# Main_Board.net
KiCad netlist of a schematic drawn in Altium Designer
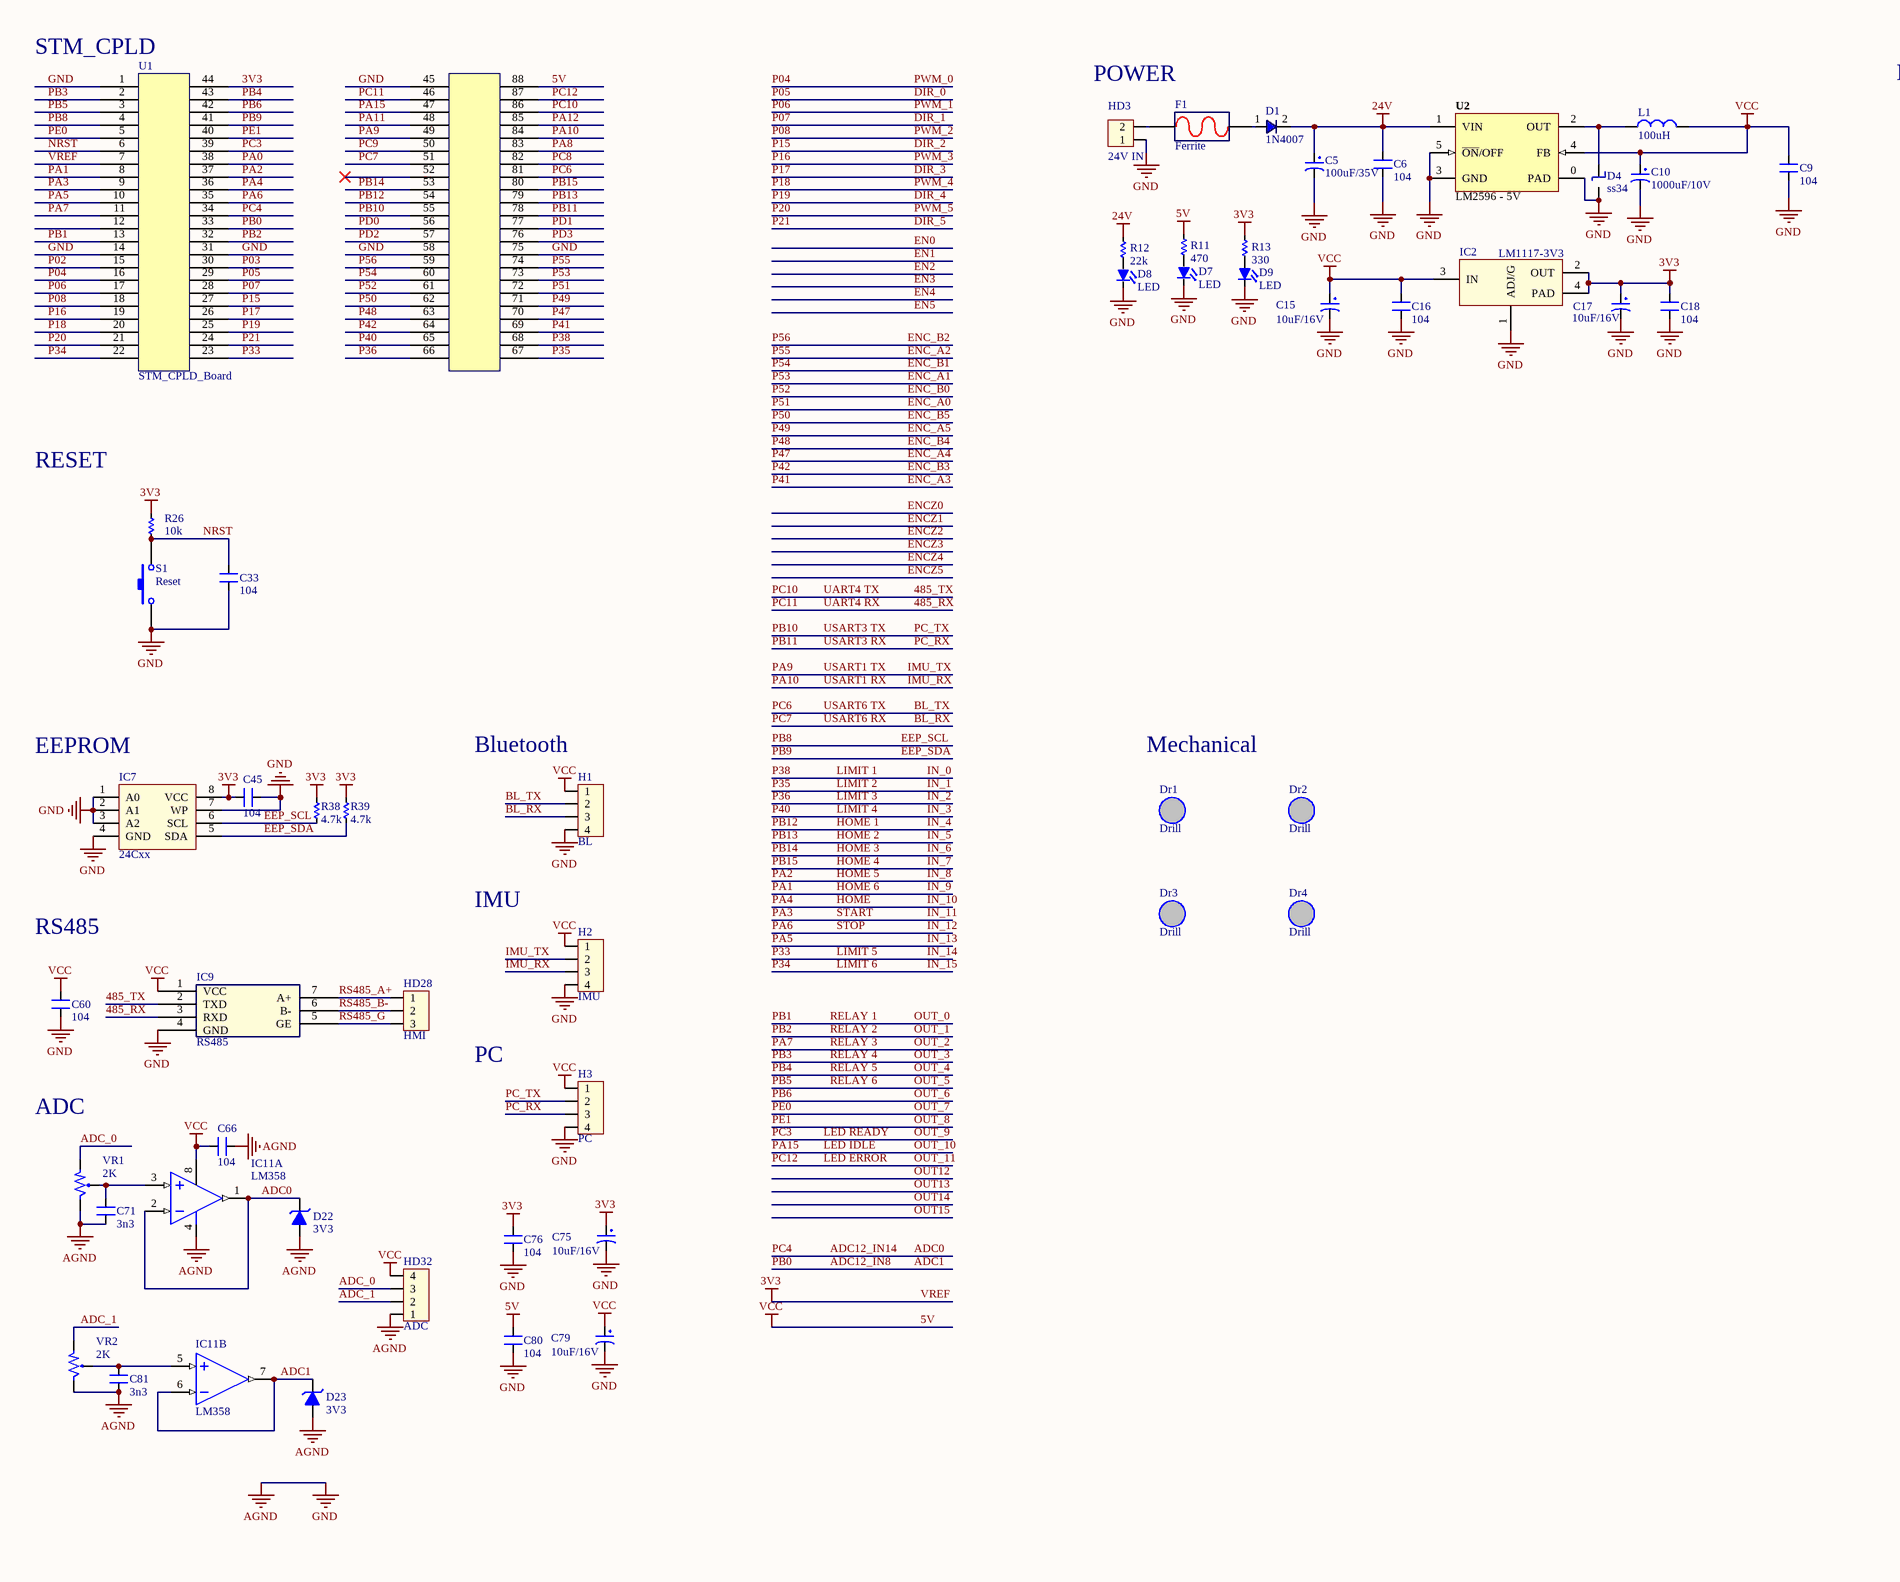
[diagram p0: Main_Board.SchDoc, top left]
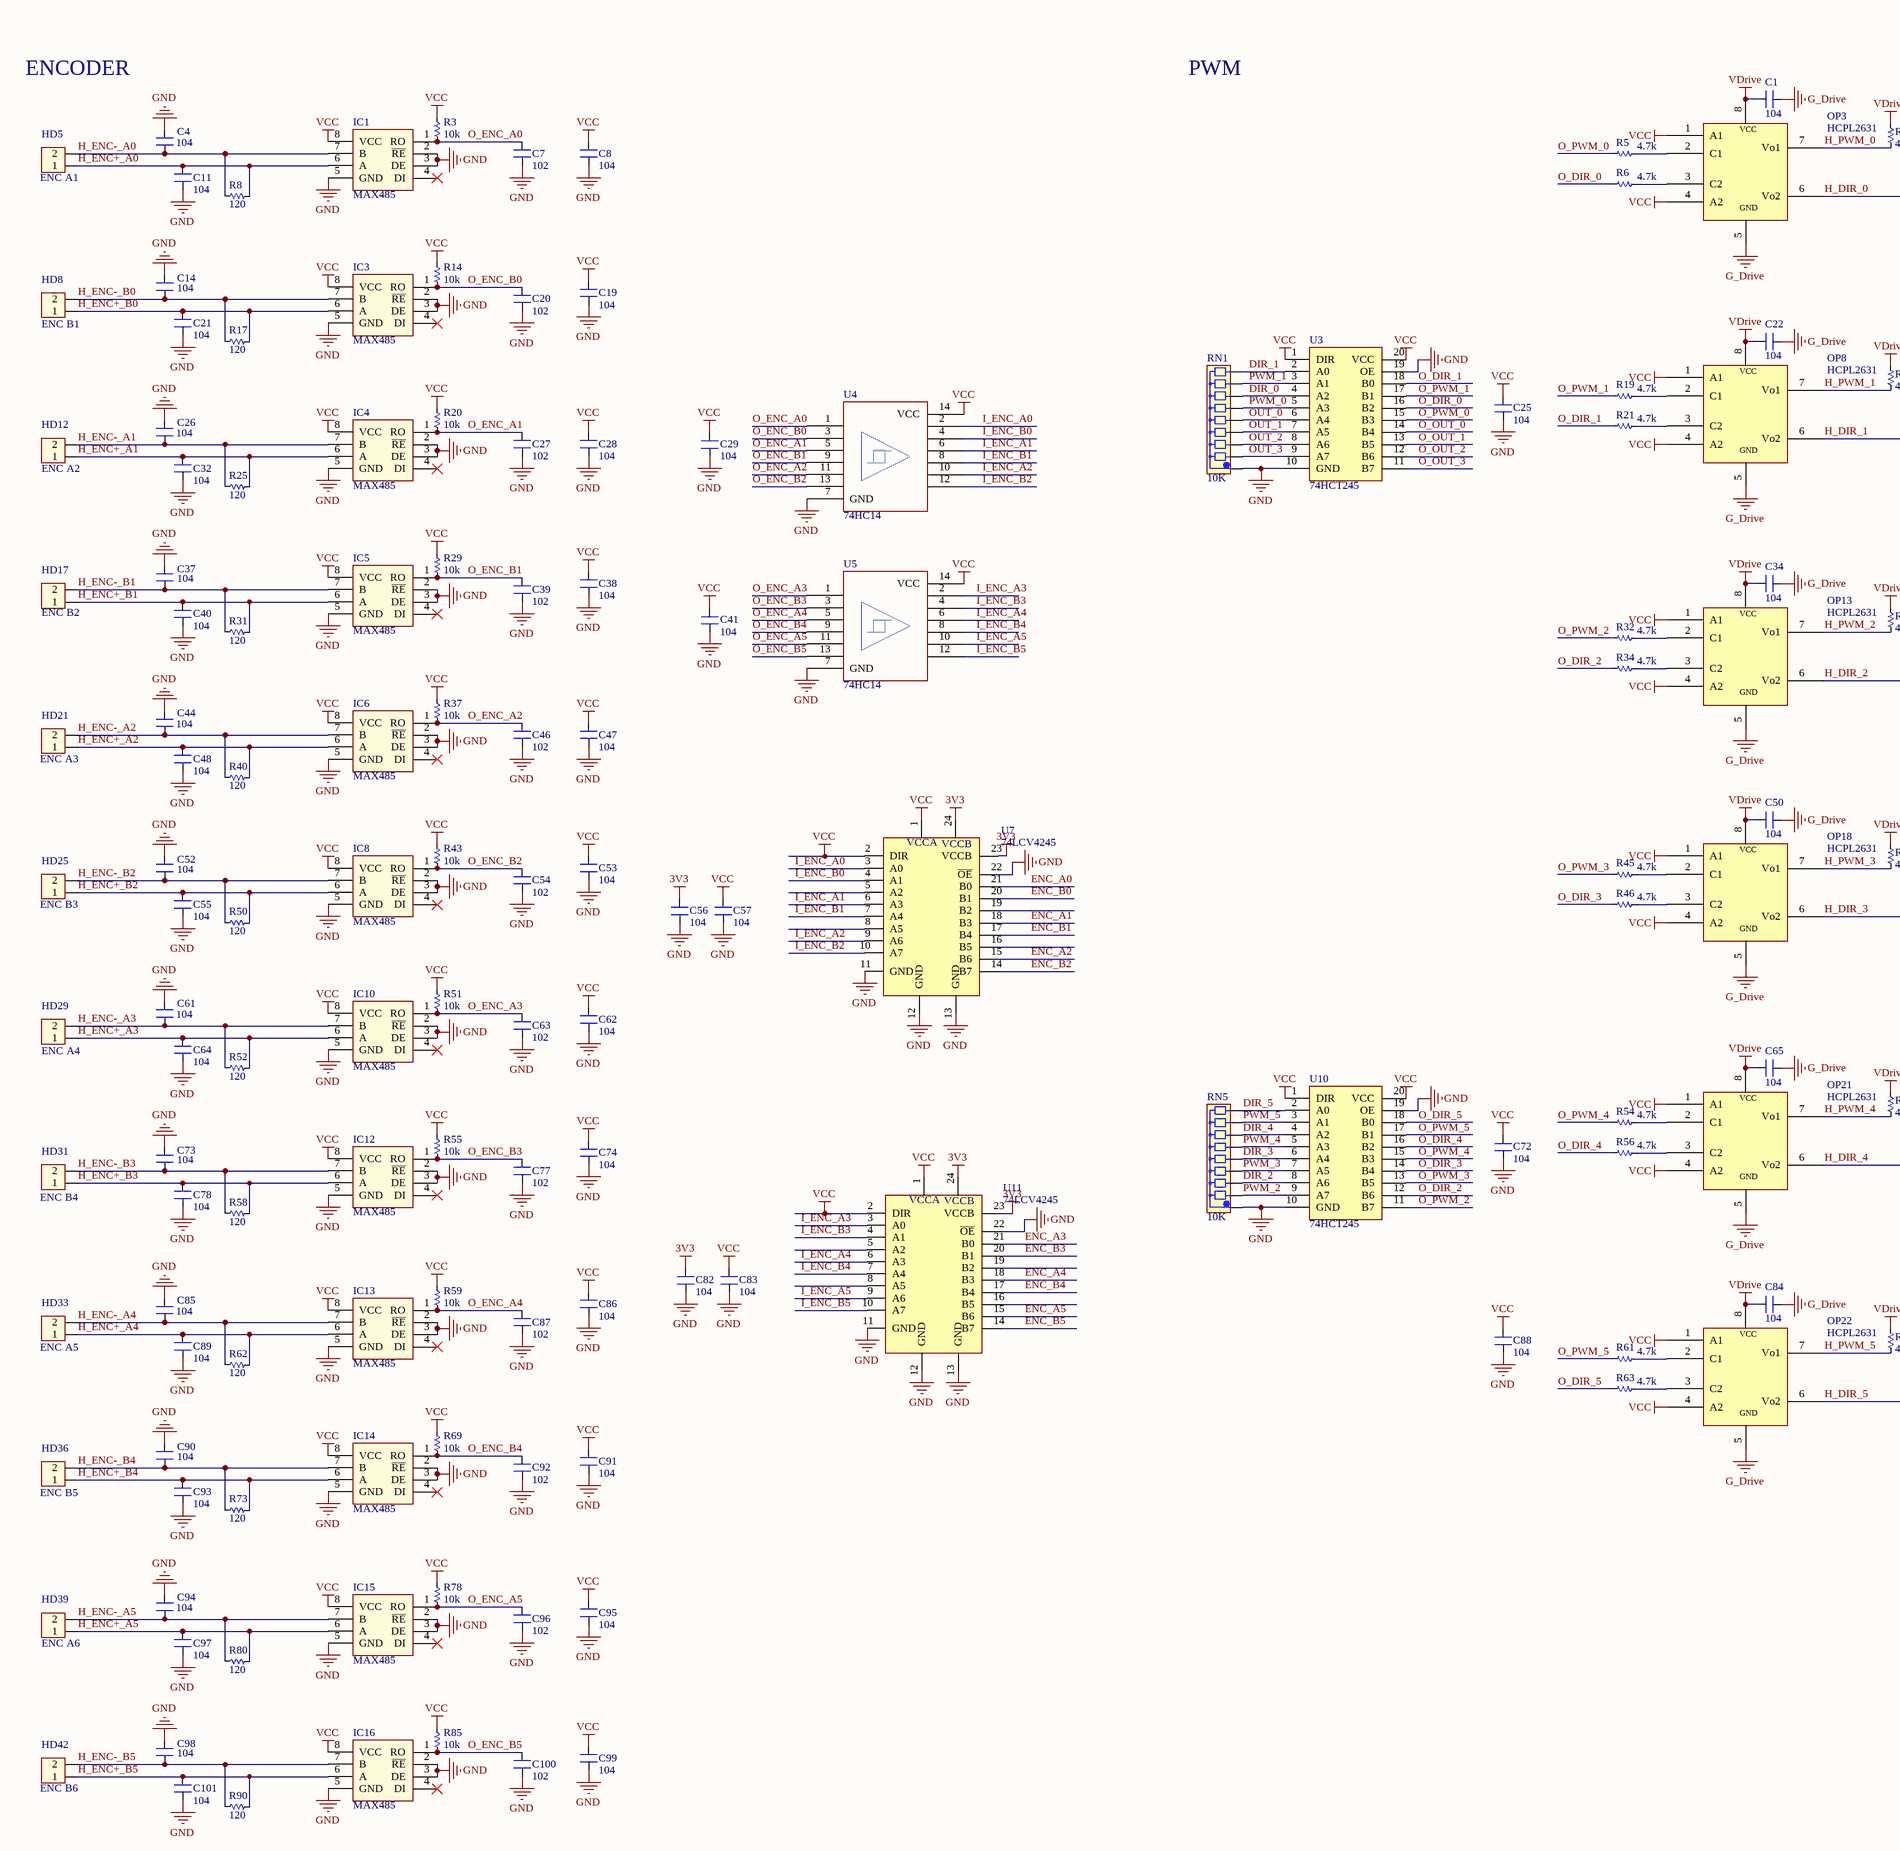
[diagram p1: Main_Board.SchDoc, top middle]
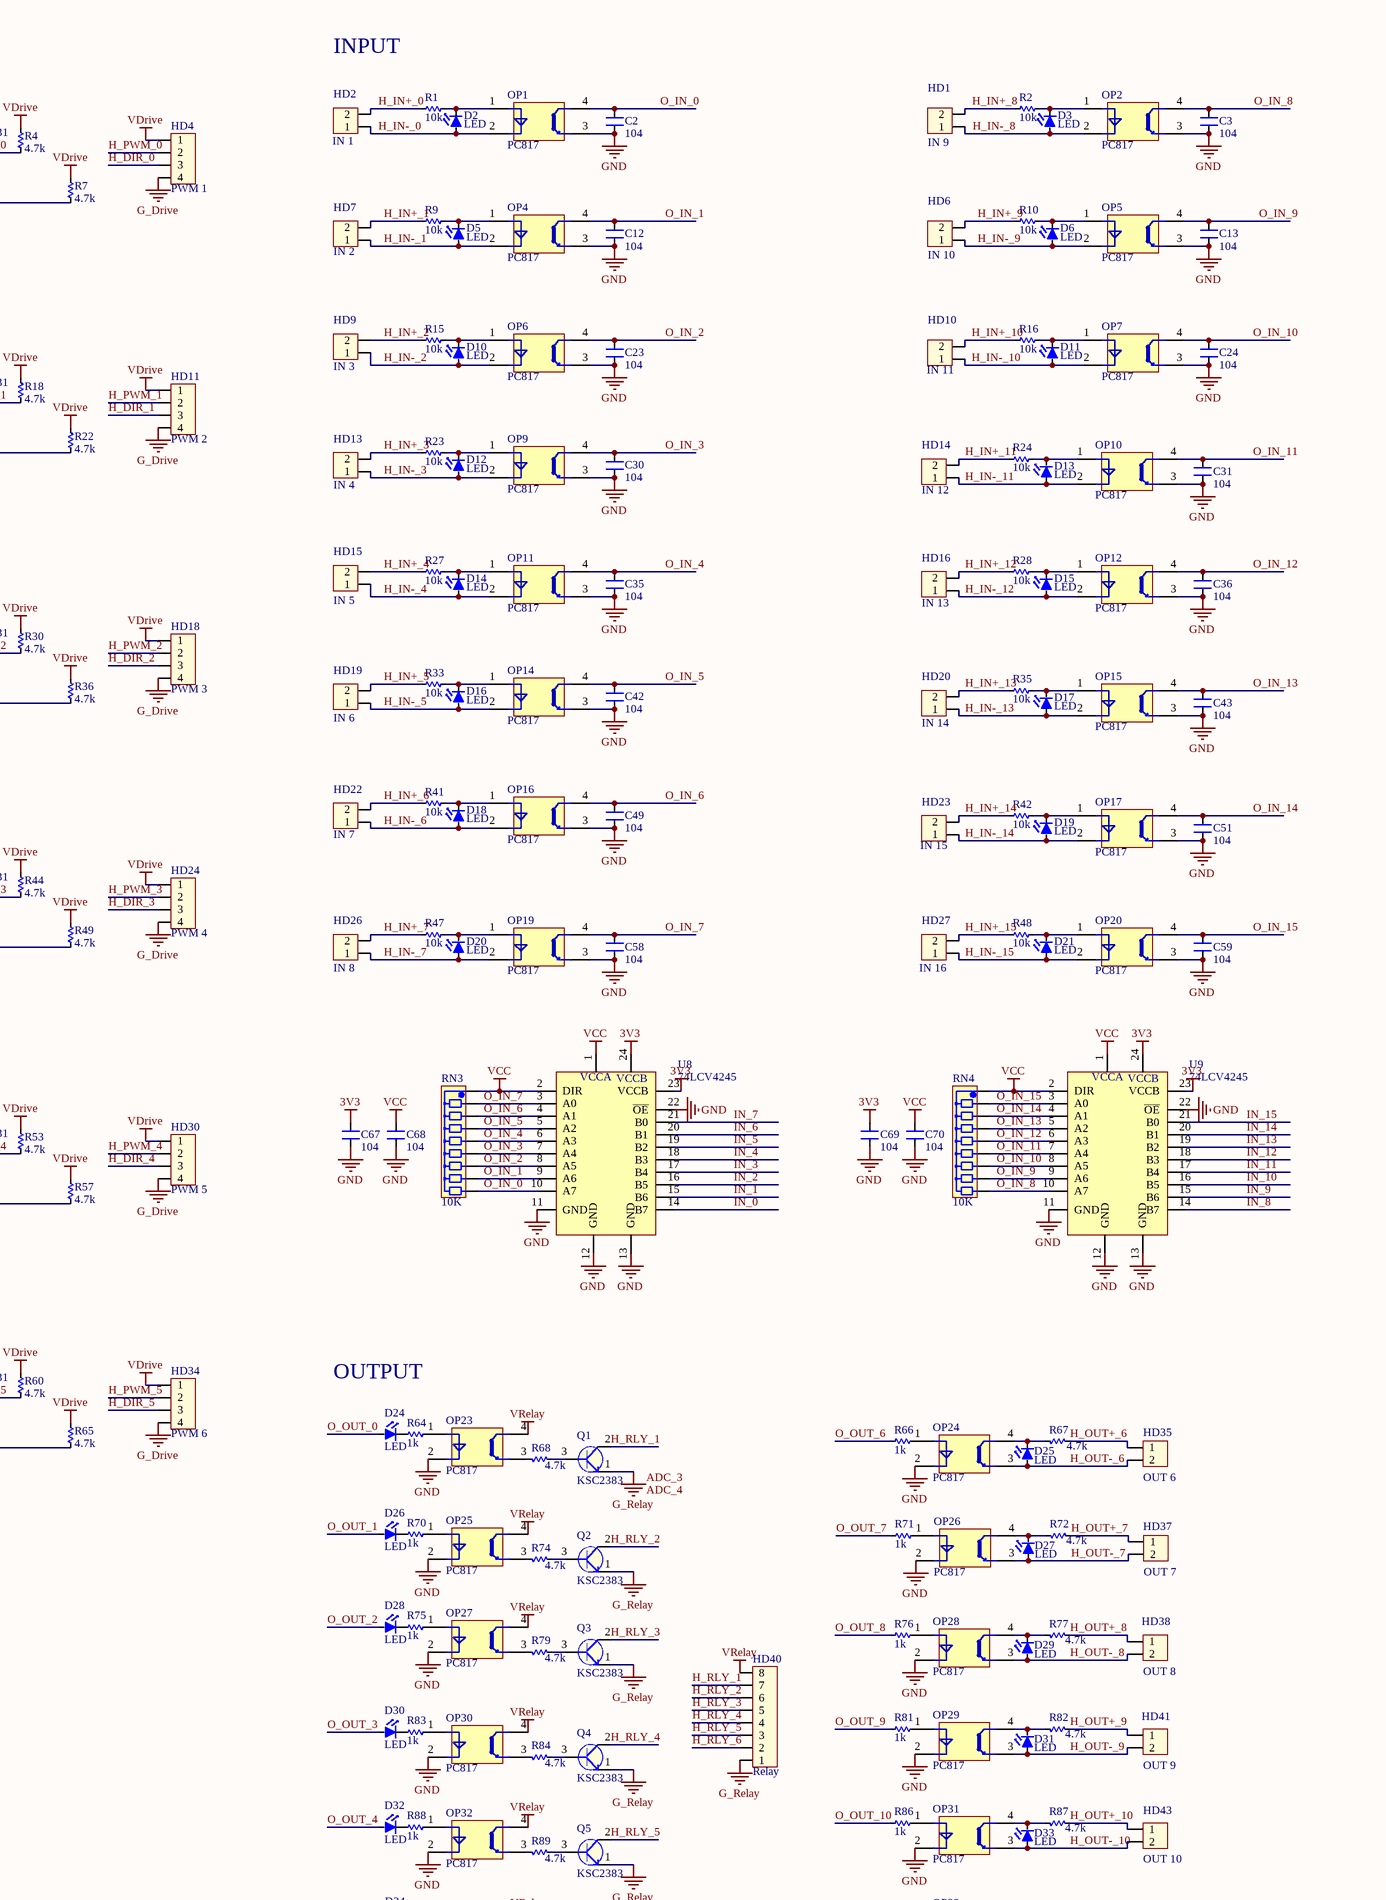
[diagram p2: Main_Board.SchDoc, top right]
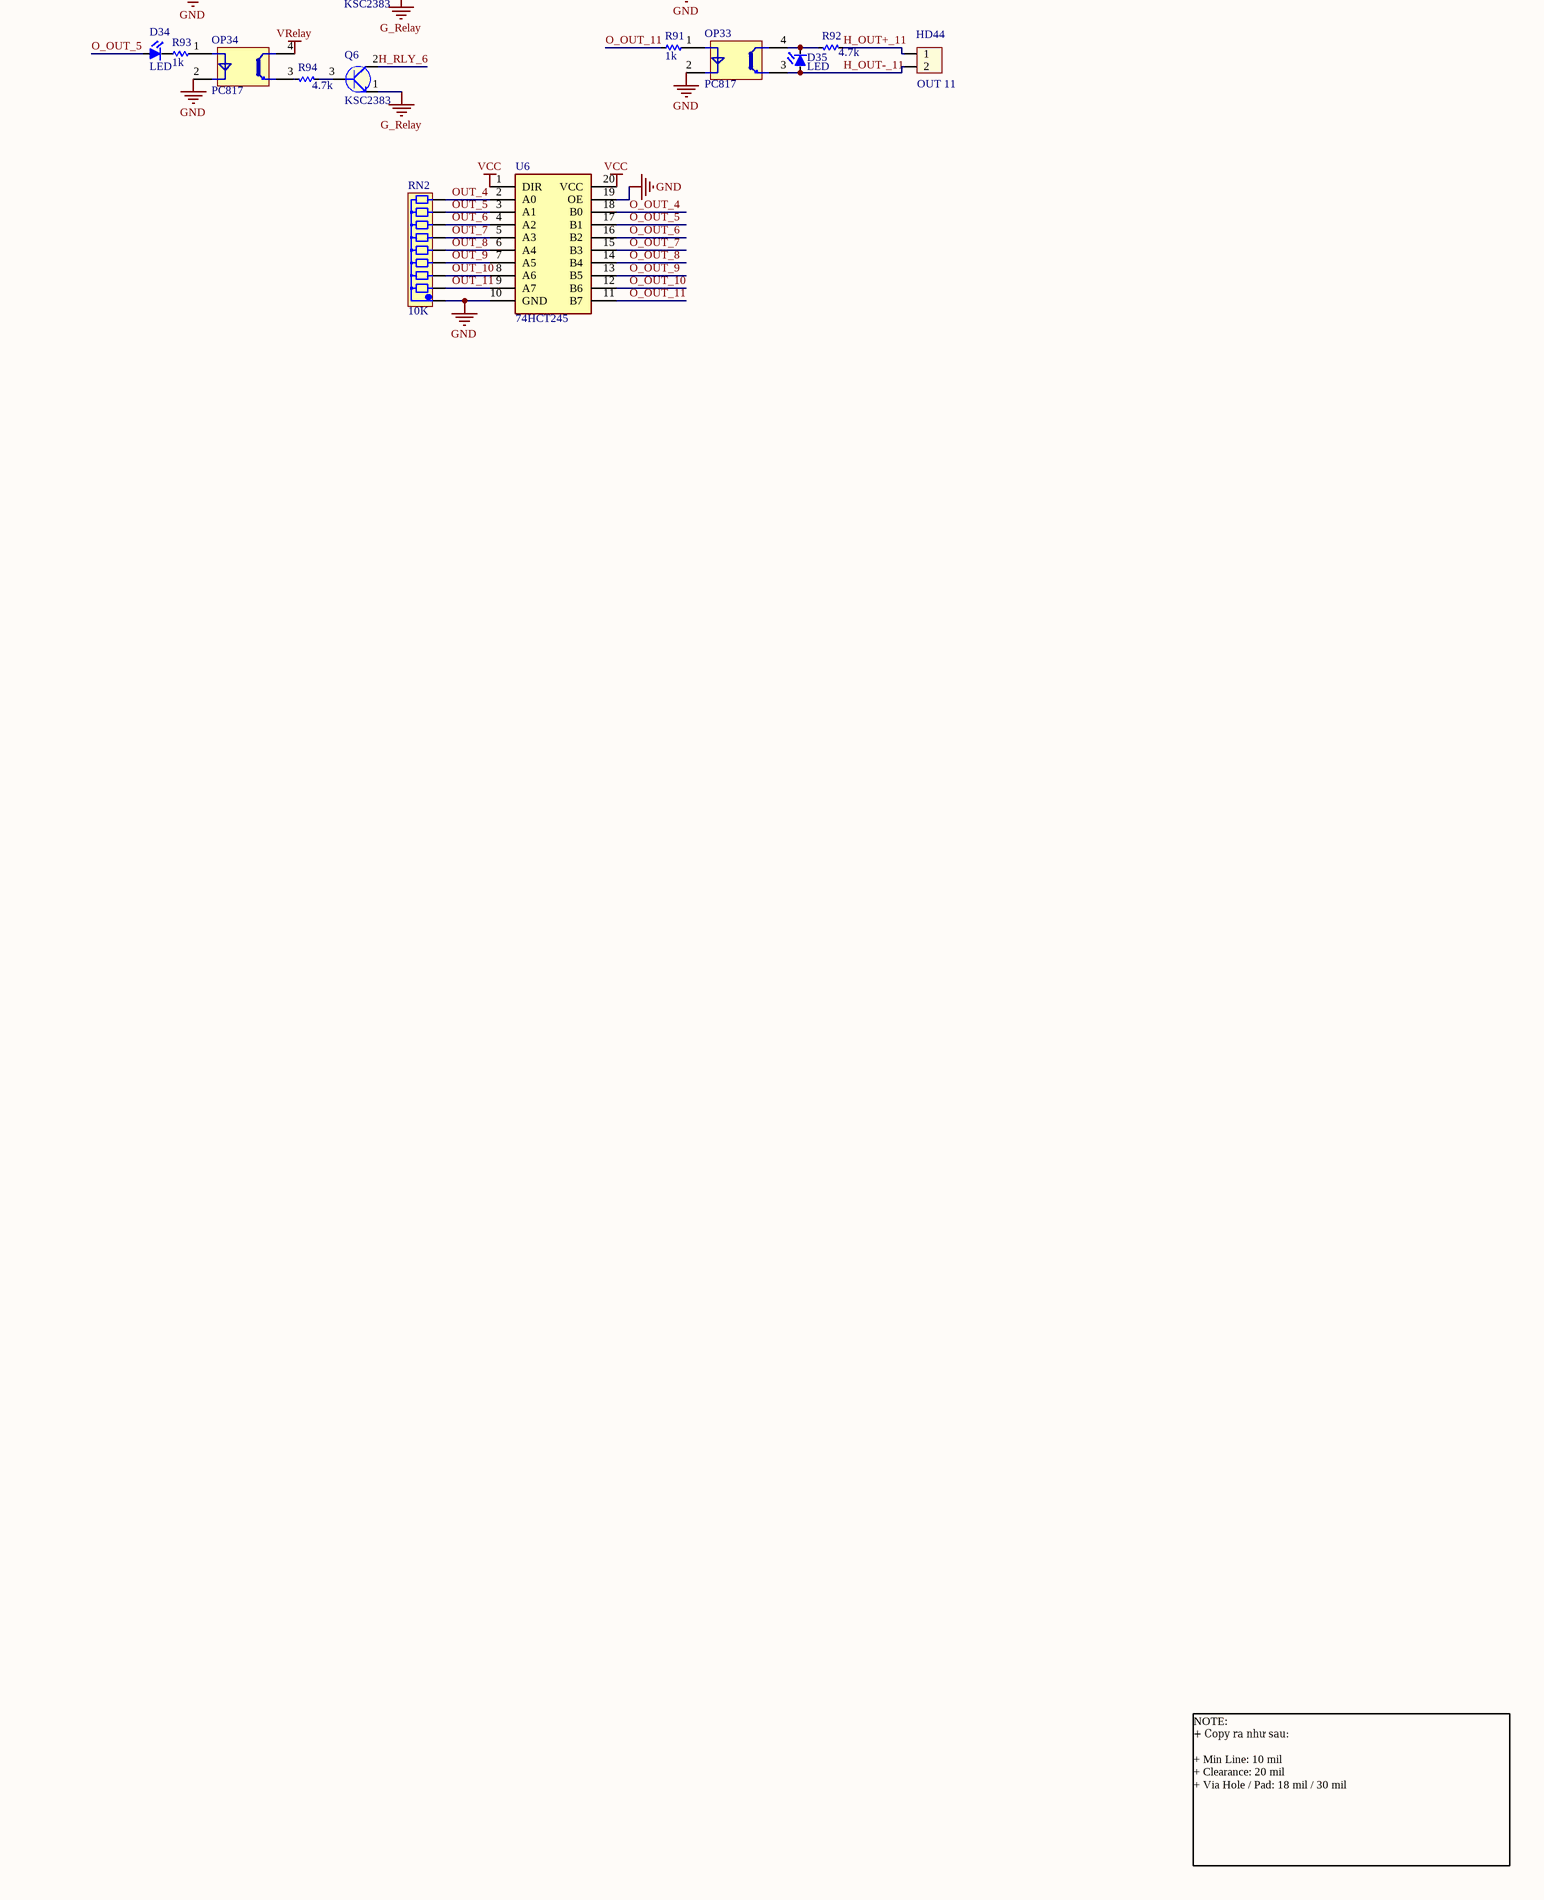
[diagram p3: Main_Board.SchDoc, bottom right]

(export (version "E")
  (design (tool "Eeschema 10.0.6"))
  (components
    (comp (ref "C1")
      (value "104")
      (footprint "CAP-SM-0805")
      (description "Ceramic Capacitor SMD")
      (libsource (lib "Main_Board") (part "CAP_SM_0805"))
    )
    (comp (ref "C2")
      (value "104")
      (footprint "CAP-SM-0805")
      (description "Ceramic Capacitor SMD")
      (libsource (lib "Main_Board") (part "CAP_SM_0805"))
    )
    (comp (ref "C3")
      (value "104")
      (footprint "CAP-SM-0805")
      (description "Ceramic Capacitor SMD")
      (libsource (lib "Main_Board") (part "CAP_SM_0805"))
    )
    (comp (ref "C4")
      (value "104")
      (footprint "CAP-SM-0805")
      (description "Ceramic Capacitor SMD")
      (libsource (lib "Main_Board") (part "CAP_SM_0805"))
    )
    (comp (ref "C5")
      (value "100uF/35V")
      (footprint "Cap_Alu_D8")
      (description "SMD Aluminum Electrolytic Capacitor")
      (libsource (lib "Main_Board") (part "Cap_SM_Alu"))
    )
    (comp (ref "C6")
      (value "104")
      (footprint "CAP-SM-0805")
      (description "Ceramic Capacitor SMD")
      (libsource (lib "Main_Board") (part "CAP_SM_0805"))
    )
    (comp (ref "C7")
      (value "102")
      (footprint "CAP-SM-0805")
      (description "Ceramic Capacitor SMD")
      (libsource (lib "Main_Board") (part "CAP_SM_0805"))
    )
    (comp (ref "C8")
      (value "104")
      (footprint "CAP-SM-0805")
      (description "Ceramic Capacitor SMD")
      (libsource (lib "Main_Board") (part "CAP_SM_0805"))
    )
    (comp (ref "C9")
      (value "104")
      (footprint "CAP-SM-0805")
      (description "Ceramic Capacitor SMD")
      (libsource (lib "Main_Board") (part "CAP_SM_0805"))
    )
    (comp (ref "C10")
      (value "1000uF/10V")
      (footprint "Cap_Alu_G")
      (description "SMD Aluminum Electrolytic Capacitor")
      (libsource (lib "Main_Board") (part "Cap_SM_Alu"))
    )
    (comp (ref "C11")
      (value "104")
      (footprint "CAP-SM-0805")
      (description "Ceramic Capacitor SMD")
      (libsource (lib "Main_Board") (part "CAP_SM_0805"))
    )
    (comp (ref "C12")
      (value "104")
      (footprint "CAP-SM-0805")
      (description "Ceramic Capacitor SMD")
      (libsource (lib "Main_Board") (part "CAP_SM_0805"))
    )
    (comp (ref "C13")
      (value "104")
      (footprint "CAP-SM-0805")
      (description "Ceramic Capacitor SMD")
      (libsource (lib "Main_Board") (part "CAP_SM_0805"))
    )
    (comp (ref "C14")
      (value "104")
      (footprint "CAP-SM-0805")
      (description "Ceramic Capacitor SMD")
      (libsource (lib "Main_Board") (part "CAP_SM_0805"))
    )
    (comp (ref "C15")
      (value "10uF/16V")
      (footprint "CAP_ALU_B")
      (description "C 47uF/50V , 220uF/16V")
      (libsource (lib "Main_Board") (part "CP2"))
    )
    (comp (ref "C16")
      (value "104")
      (footprint "CAP-SM-0805")
      (description "Ceramic Capacitor SMD")
      (libsource (lib "Main_Board") (part "CAP_SM_0805"))
    )
    (comp (ref "C17")
      (value "10uF/16V")
      (footprint "CAP_ALU_B")
      (description "C 47uF/50V , 220uF/16V")
      (libsource (lib "Main_Board") (part "CP2"))
    )
    (comp (ref "C18")
      (value "104")
      (footprint "CAP-SM-0805")
      (description "Ceramic Capacitor SMD")
      (libsource (lib "Main_Board") (part "CAP_SM_0805"))
    )
    (comp (ref "C19")
      (value "104")
      (footprint "CAP-SM-0805")
      (description "Ceramic Capacitor SMD")
      (libsource (lib "Main_Board") (part "CAP_SM_0805"))
    )
    (comp (ref "C20")
      (value "102")
      (footprint "CAP-SM-0805")
      (description "Ceramic Capacitor SMD")
      (libsource (lib "Main_Board") (part "CAP_SM_0805"))
    )
    (comp (ref "C21")
      (value "104")
      (footprint "CAP-SM-0805")
      (description "Ceramic Capacitor SMD")
      (libsource (lib "Main_Board") (part "CAP_SM_0805"))
    )
    (comp (ref "C22")
      (value "104")
      (footprint "CAP-SM-0805")
      (description "Ceramic Capacitor SMD")
      (libsource (lib "Main_Board") (part "CAP_SM_0805"))
    )
    (comp (ref "C23")
      (value "104")
      (footprint "CAP-SM-0805")
      (description "Ceramic Capacitor SMD")
      (libsource (lib "Main_Board") (part "CAP_SM_0805"))
    )
    (comp (ref "C24")
      (value "104")
      (footprint "CAP-SM-0805")
      (description "Ceramic Capacitor SMD")
      (libsource (lib "Main_Board") (part "CAP_SM_0805"))
    )
    (comp (ref "C25")
      (value "104")
      (footprint "CAP-SM-0805")
      (description "Ceramic Capacitor SMD")
      (libsource (lib "Main_Board") (part "CAP_SM_0805"))
    )
    (comp (ref "C26")
      (value "104")
      (footprint "CAP-SM-0805")
      (description "Ceramic Capacitor SMD")
      (libsource (lib "Main_Board") (part "CAP_SM_0805"))
    )
    (comp (ref "C27")
      (value "102")
      (footprint "CAP-SM-0805")
      (description "Ceramic Capacitor SMD")
      (libsource (lib "Main_Board") (part "CAP_SM_0805"))
    )
    (comp (ref "C28")
      (value "104")
      (footprint "CAP-SM-0805")
      (description "Ceramic Capacitor SMD")
      (libsource (lib "Main_Board") (part "CAP_SM_0805"))
    )
    (comp (ref "C29")
      (value "104")
      (footprint "CAP-SM-0805")
      (description "Ceramic Capacitor SMD")
      (libsource (lib "Main_Board") (part "CAP_SM_0805"))
    )
    (comp (ref "C30")
      (value "104")
      (footprint "CAP-SM-0805")
      (description "Ceramic Capacitor SMD")
      (libsource (lib "Main_Board") (part "CAP_SM_0805"))
    )
    (comp (ref "C31")
      (value "104")
      (footprint "CAP-SM-0805")
      (description "Ceramic Capacitor SMD")
      (libsource (lib "Main_Board") (part "CAP_SM_0805"))
    )
    (comp (ref "C32")
      (value "104")
      (footprint "CAP-SM-0805")
      (description "Ceramic Capacitor SMD")
      (libsource (lib "Main_Board") (part "CAP_SM_0805"))
    )
    (comp (ref "C33")
      (value "104")
      (footprint "CAP-SM-0805")
      (description "Ceramic Capacitor SMD")
      (libsource (lib "Main_Board") (part "CAP_SM_0805"))
    )
    (comp (ref "C34")
      (value "104")
      (footprint "CAP-SM-0805")
      (description "Ceramic Capacitor SMD")
      (libsource (lib "Main_Board") (part "CAP_SM_0805"))
    )
    (comp (ref "C35")
      (value "104")
      (footprint "CAP-SM-0805")
      (description "Ceramic Capacitor SMD")
      (libsource (lib "Main_Board") (part "CAP_SM_0805"))
    )
    (comp (ref "C36")
      (value "104")
      (footprint "CAP-SM-0805")
      (description "Ceramic Capacitor SMD")
      (libsource (lib "Main_Board") (part "CAP_SM_0805"))
    )
    (comp (ref "C37")
      (value "104")
      (footprint "CAP-SM-0805")
      (description "Ceramic Capacitor SMD")
      (libsource (lib "Main_Board") (part "CAP_SM_0805"))
    )
    (comp (ref "C38")
      (value "104")
      (footprint "CAP-SM-0805")
      (description "Ceramic Capacitor SMD")
      (libsource (lib "Main_Board") (part "CAP_SM_0805"))
    )
    (comp (ref "C39")
      (value "102")
      (footprint "CAP-SM-0805")
      (description "Ceramic Capacitor SMD")
      (libsource (lib "Main_Board") (part "CAP_SM_0805"))
    )
    (comp (ref "C40")
      (value "104")
      (footprint "CAP-SM-0805")
      (description "Ceramic Capacitor SMD")
      (libsource (lib "Main_Board") (part "CAP_SM_0805"))
    )
    (comp (ref "C41")
      (value "104")
      (footprint "CAP-SM-0805")
      (description "Ceramic Capacitor SMD")
      (libsource (lib "Main_Board") (part "CAP_SM_0805"))
    )
    (comp (ref "C42")
      (value "104")
      (footprint "CAP-SM-0805")
      (description "Ceramic Capacitor SMD")
      (libsource (lib "Main_Board") (part "CAP_SM_0805"))
    )
    (comp (ref "C43")
      (value "104")
      (footprint "CAP-SM-0805")
      (description "Ceramic Capacitor SMD")
      (libsource (lib "Main_Board") (part "CAP_SM_0805"))
    )
    (comp (ref "C44")
      (value "104")
      (footprint "CAP-SM-0805")
      (description "Ceramic Capacitor SMD")
      (libsource (lib "Main_Board") (part "CAP_SM_0805"))
    )
    (comp (ref "C45")
      (value "104")
      (footprint "CAP-SM-0805")
      (description "Ceramic Capacitor SMD")
      (libsource (lib "Main_Board") (part "CAP_SM_0805"))
    )
    (comp (ref "C46")
      (value "102")
      (footprint "CAP-SM-0805")
      (description "Ceramic Capacitor SMD")
      (libsource (lib "Main_Board") (part "CAP_SM_0805"))
    )
    (comp (ref "C47")
      (value "104")
      (footprint "CAP-SM-0805")
      (description "Ceramic Capacitor SMD")
      (libsource (lib "Main_Board") (part "CAP_SM_0805"))
    )
    (comp (ref "C48")
      (value "104")
      (footprint "CAP-SM-0805")
      (description "Ceramic Capacitor SMD")
      (libsource (lib "Main_Board") (part "CAP_SM_0805"))
    )
    (comp (ref "C49")
      (value "104")
      (footprint "CAP-SM-0805")
      (description "Ceramic Capacitor SMD")
      (libsource (lib "Main_Board") (part "CAP_SM_0805"))
    )
    (comp (ref "C50")
      (value "104")
      (footprint "CAP-SM-0805")
      (description "Ceramic Capacitor SMD")
      (libsource (lib "Main_Board") (part "CAP_SM_0805"))
    )
    (comp (ref "C51")
      (value "104")
      (footprint "CAP-SM-0805")
      (description "Ceramic Capacitor SMD")
      (libsource (lib "Main_Board") (part "CAP_SM_0805"))
    )
    (comp (ref "C52")
      (value "104")
      (footprint "CAP-SM-0805")
      (description "Ceramic Capacitor SMD")
      (libsource (lib "Main_Board") (part "CAP_SM_0805"))
    )
    (comp (ref "C53")
      (value "104")
      (footprint "CAP-SM-0805")
      (description "Ceramic Capacitor SMD")
      (libsource (lib "Main_Board") (part "CAP_SM_0805"))
    )
    (comp (ref "C54")
      (value "102")
      (footprint "CAP-SM-0805")
      (description "Ceramic Capacitor SMD")
      (libsource (lib "Main_Board") (part "CAP_SM_0805"))
    )
    (comp (ref "C55")
      (value "104")
      (footprint "CAP-SM-0805")
      (description "Ceramic Capacitor SMD")
      (libsource (lib "Main_Board") (part "CAP_SM_0805"))
    )
    (comp (ref "C56")
      (value "104")
      (footprint "CAP-SM-0805")
      (description "Ceramic Capacitor SMD")
      (libsource (lib "Main_Board") (part "CAP_SM_0805"))
    )
    (comp (ref "C57")
      (value "104")
      (footprint "CAP-SM-0805")
      (description "Ceramic Capacitor SMD")
      (libsource (lib "Main_Board") (part "CAP_SM_0805"))
    )
    (comp (ref "C58")
      (value "104")
      (footprint "CAP-SM-0805")
      (description "Ceramic Capacitor SMD")
      (libsource (lib "Main_Board") (part "CAP_SM_0805"))
    )
    (comp (ref "C59")
      (value "104")
      (footprint "CAP-SM-0805")
      (description "Ceramic Capacitor SMD")
      (libsource (lib "Main_Board") (part "CAP_SM_0805"))
    )
    (comp (ref "C60")
      (value "104")
      (footprint "CAP-SM-0805")
      (description "Ceramic Capacitor SMD")
      (libsource (lib "Main_Board") (part "CAP_SM_0805"))
    )
    (comp (ref "C61")
      (value "104")
      (footprint "CAP-SM-0805")
      (description "Ceramic Capacitor SMD")
      (libsource (lib "Main_Board") (part "CAP_SM_0805"))
    )
    (comp (ref "C62")
      (value "104")
      (footprint "CAP-SM-0805")
      (description "Ceramic Capacitor SMD")
      (libsource (lib "Main_Board") (part "CAP_SM_0805"))
    )
    (comp (ref "C63")
      (value "102")
      (footprint "CAP-SM-0805")
      (description "Ceramic Capacitor SMD")
      (libsource (lib "Main_Board") (part "CAP_SM_0805"))
    )
    (comp (ref "C64")
      (value "104")
      (footprint "CAP-SM-0805")
      (description "Ceramic Capacitor SMD")
      (libsource (lib "Main_Board") (part "CAP_SM_0805"))
    )
    (comp (ref "C65")
      (value "104")
      (footprint "CAP-SM-0805")
      (description "Ceramic Capacitor SMD")
      (libsource (lib "Main_Board") (part "CAP_SM_0805"))
    )
    (comp (ref "C66")
      (value "104")
      (footprint "CAP-SM-0805")
      (fields (field (name "DESIGNED BY") "VanDungEvn"))
      (libsource (lib "Main_Board") (part "CN"))
    )
    (comp (ref "C67")
      (value "104")
      (footprint "CAP-SM-0805")
      (description "Ceramic Capacitor SMD")
      (libsource (lib "Main_Board") (part "CAP_SM_0805"))
    )
    (comp (ref "C68")
      (value "104")
      (footprint "CAP-SM-0805")
      (description "Ceramic Capacitor SMD")
      (libsource (lib "Main_Board") (part "CAP_SM_0805"))
    )
    (comp (ref "C69")
      (value "104")
      (footprint "CAP-SM-0805")
      (description "Ceramic Capacitor SMD")
      (libsource (lib "Main_Board") (part "CAP_SM_0805"))
    )
    (comp (ref "C70")
      (value "104")
      (footprint "CAP-SM-0805")
      (description "Ceramic Capacitor SMD")
      (libsource (lib "Main_Board") (part "CAP_SM_0805"))
    )
    (comp (ref "C71")
      (value "3n3")
      (footprint "CAP-SM-0805")
      (fields (field (name "DESIGNED BY") "VanDungEvn"))
      (libsource (lib "Main_Board") (part "CN"))
    )
    (comp (ref "C72")
      (value "104")
      (footprint "CAP-SM-0805")
      (description "Ceramic Capacitor SMD")
      (libsource (lib "Main_Board") (part "CAP_SM_0805"))
    )
    (comp (ref "C73")
      (value "104")
      (footprint "CAP-SM-0805")
      (description "Ceramic Capacitor SMD")
      (libsource (lib "Main_Board") (part "CAP_SM_0805"))
    )
    (comp (ref "C74")
      (value "104")
      (footprint "CAP-SM-0805")
      (description "Ceramic Capacitor SMD")
      (libsource (lib "Main_Board") (part "CAP_SM_0805"))
    )
    (comp (ref "C75")
      (value "10uF/16V")
      (footprint "CAP_ALU_B")
      (description "C 47uF/50V , 220uF/16V")
      (libsource (lib "Main_Board") (part "CP2"))
    )
    (comp (ref "C76")
      (value "104")
      (footprint "CAP-SM-0805")
      (description "Ceramic Capacitor SMD")
      (libsource (lib "Main_Board") (part "CAP_SM_0805"))
    )
    (comp (ref "C77")
      (value "102")
      (footprint "CAP-SM-0805")
      (description "Ceramic Capacitor SMD")
      (libsource (lib "Main_Board") (part "CAP_SM_0805"))
    )
    (comp (ref "C78")
      (value "104")
      (footprint "CAP-SM-0805")
      (description "Ceramic Capacitor SMD")
      (libsource (lib "Main_Board") (part "CAP_SM_0805"))
    )
    (comp (ref "C79")
      (value "10uF/16V")
      (footprint "CAP_ALU_B")
      (description "C 47uF/50V , 220uF/16V")
      (libsource (lib "Main_Board") (part "CP2"))
    )
    (comp (ref "C80")
      (value "104")
      (footprint "CAP-SM-0805")
      (description "Ceramic Capacitor SMD")
      (libsource (lib "Main_Board") (part "CAP_SM_0805"))
    )
    (comp (ref "C81")
      (value "3n3")
      (footprint "CAP-SM-0805")
      (description "Ceramic Capacitor SMD")
      (fields (field (name "DESIGNED BY") "VanDungEvn"))
      (libsource (lib "Main_Board") (part "CN"))
    )
    (comp (ref "C82")
      (value "104")
      (footprint "CAP-SM-0805")
      (description "Ceramic Capacitor SMD")
      (libsource (lib "Main_Board") (part "CAP_SM_0805"))
    )
    (comp (ref "C83")
      (value "104")
      (footprint "CAP-SM-0805")
      (description "Ceramic Capacitor SMD")
      (libsource (lib "Main_Board") (part "CAP_SM_0805"))
    )
    (comp (ref "C84")
      (value "104")
      (footprint "CAP-SM-0805")
      (description "Ceramic Capacitor SMD")
      (libsource (lib "Main_Board") (part "CAP_SM_0805"))
    )
    (comp (ref "C85")
      (value "104")
      (footprint "CAP-SM-0805")
      (description "Ceramic Capacitor SMD")
      (libsource (lib "Main_Board") (part "CAP_SM_0805"))
    )
    (comp (ref "C86")
      (value "104")
      (footprint "CAP-SM-0805")
      (description "Ceramic Capacitor SMD")
      (libsource (lib "Main_Board") (part "CAP_SM_0805"))
    )
    (comp (ref "C87")
      (value "102")
      (footprint "CAP-SM-0805")
      (description "Ceramic Capacitor SMD")
      (libsource (lib "Main_Board") (part "CAP_SM_0805"))
    )
    (comp (ref "C88")
      (value "104")
      (footprint "CAP-SM-0805")
      (description "Ceramic Capacitor SMD")
      (libsource (lib "Main_Board") (part "CAP_SM_0805"))
    )
    (comp (ref "C89")
      (value "104")
      (footprint "CAP-SM-0805")
      (description "Ceramic Capacitor SMD")
      (libsource (lib "Main_Board") (part "CAP_SM_0805"))
    )
    (comp (ref "C90")
      (value "104")
      (footprint "CAP-SM-0805")
      (description "Ceramic Capacitor SMD")
      (libsource (lib "Main_Board") (part "CAP_SM_0805"))
    )
    (comp (ref "C91")
      (value "104")
      (footprint "CAP-SM-0805")
      (description "Ceramic Capacitor SMD")
      (libsource (lib "Main_Board") (part "CAP_SM_0805"))
    )
    (comp (ref "C92")
      (value "102")
      (footprint "CAP-SM-0805")
      (description "Ceramic Capacitor SMD")
      (libsource (lib "Main_Board") (part "CAP_SM_0805"))
    )
    (comp (ref "C93")
      (value "104")
      (footprint "CAP-SM-0805")
      (description "Ceramic Capacitor SMD")
      (libsource (lib "Main_Board") (part "CAP_SM_0805"))
    )
    (comp (ref "C94")
      (value "104")
      (footprint "CAP-SM-0805")
      (description "Ceramic Capacitor SMD")
      (libsource (lib "Main_Board") (part "CAP_SM_0805"))
    )
    (comp (ref "C95")
      (value "104")
      (footprint "CAP-SM-0805")
      (description "Ceramic Capacitor SMD")
      (libsource (lib "Main_Board") (part "CAP_SM_0805"))
    )
    (comp (ref "C96")
      (value "102")
      (footprint "CAP-SM-0805")
      (description "Ceramic Capacitor SMD")
      (libsource (lib "Main_Board") (part "CAP_SM_0805"))
    )
    (comp (ref "C97")
      (value "104")
      (footprint "CAP-SM-0805")
      (description "Ceramic Capacitor SMD")
      (libsource (lib "Main_Board") (part "CAP_SM_0805"))
    )
    (comp (ref "C98")
      (value "104")
      (footprint "CAP-SM-0805")
      (description "Ceramic Capacitor SMD")
      (libsource (lib "Main_Board") (part "CAP_SM_0805"))
    )
    (comp (ref "C99")
      (value "104")
      (footprint "CAP-SM-0805")
      (description "Ceramic Capacitor SMD")
      (libsource (lib "Main_Board") (part "CAP_SM_0805"))
    )
    (comp (ref "C100")
      (value "102")
      (footprint "CAP-SM-0805")
      (description "Ceramic Capacitor SMD")
      (libsource (lib "Main_Board") (part "CAP_SM_0805"))
    )
    (comp (ref "C101")
      (value "104")
      (footprint "CAP-SM-0805")
      (description "Ceramic Capacitor SMD")
      (libsource (lib "Main_Board") (part "CAP_SM_0805"))
    )
    (comp (ref "D1")
      (value "1N4007")
      (footprint "DO-214AB")
      (description "General Rectifier")
      (libsource (lib "Main_Board") (part "Diode"))
    )
    (comp (ref "D2")
      (value "LED")
      (footprint "LED_0805_Blue")
      (description "LED SMD")
      (libsource (lib "Main_Board") (part "LED_SMD"))
    )
    (comp (ref "D3")
      (value "LED")
      (footprint "LED_0805_Blue")
      (description "LED SMD")
      (libsource (lib "Main_Board") (part "LED_SMD"))
    )
    (comp (ref "D4")
      (value "ss34")
      (footprint "DO-214AB")
      (description "Surface Mount Schottky Barrier Rectifier")
      (libsource (lib "Main_Board") (part "ss34"))
    )
    (comp (ref "D5")
      (value "LED")
      (footprint "LED_0805_Blue")
      (description "LED SMD")
      (libsource (lib "Main_Board") (part "LED_SMD"))
    )
    (comp (ref "D6")
      (value "LED")
      (footprint "LED_0805_Blue")
      (description "LED SMD")
      (libsource (lib "Main_Board") (part "LED_SMD"))
    )
    (comp (ref "D7")
      (value "LED")
      (footprint "LED_0805_Blue")
      (description "LED SMD")
      (libsource (lib "Main_Board") (part "LED_SMD"))
    )
    (comp (ref "D8")
      (value "LED")
      (footprint "LED_0805_Blue")
      (description "LED SMD")
      (libsource (lib "Main_Board") (part "LED_SMD"))
    )
    (comp (ref "D9")
      (value "LED")
      (footprint "LED_0805_Blue")
      (description "LED SMD")
      (libsource (lib "Main_Board") (part "LED_SMD"))
    )
    (comp (ref "D10")
      (value "LED")
      (footprint "LED_0805_Blue")
      (description "LED SMD")
      (libsource (lib "Main_Board") (part "LED_SMD"))
    )
    (comp (ref "D11")
      (value "LED")
      (footprint "LED_0805_Blue")
      (description "LED SMD")
      (libsource (lib "Main_Board") (part "LED_SMD"))
    )
    (comp (ref "D12")
      (value "LED")
      (footprint "LED_0805_Blue")
      (description "LED SMD")
      (libsource (lib "Main_Board") (part "LED_SMD"))
    )
    (comp (ref "D13")
      (value "LED")
      (footprint "LED_0805_Blue")
      (description "LED SMD")
      (libsource (lib "Main_Board") (part "LED_SMD"))
    )
    (comp (ref "D14")
      (value "LED")
      (footprint "LED_0805_Blue")
      (description "LED SMD")
      (libsource (lib "Main_Board") (part "LED_SMD"))
    )
    (comp (ref "D15")
      (value "LED")
      (footprint "LED_0805_Blue")
      (description "LED SMD")
      (libsource (lib "Main_Board") (part "LED_SMD"))
    )
    (comp (ref "D16")
      (value "LED")
      (footprint "LED_0805_Blue")
      (description "LED SMD")
      (libsource (lib "Main_Board") (part "LED_SMD"))
    )
    (comp (ref "D17")
      (value "LED")
      (footprint "LED_0805_Blue")
      (description "LED SMD")
      (libsource (lib "Main_Board") (part "LED_SMD"))
    )
    (comp (ref "D18")
      (value "LED")
      (footprint "LED_0805_Blue")
      (description "LED SMD")
      (libsource (lib "Main_Board") (part "LED_SMD"))
    )
    (comp (ref "D19")
      (value "LED")
      (footprint "LED_0805_Blue")
      (description "LED SMD")
      (libsource (lib "Main_Board") (part "LED_SMD"))
    )
    (comp (ref "D20")
      (value "LED")
      (footprint "LED_0805_Blue")
      (description "LED SMD")
      (libsource (lib "Main_Board") (part "LED_SMD"))
    )
    (comp (ref "D21")
      (value "LED")
      (footprint "LED_0805_Blue")
      (description "LED SMD")
      (libsource (lib "Main_Board") (part "LED_SMD"))
    )
    (comp (ref "D22")
      (value "3V3")
      (footprint "Diode zener")
      (description "Silicon Planar Zener Diodes")
      (libsource (lib "Main_Board") (part "D Zener"))
    )
    (comp (ref "D23")
      (value "3V3")
      (footprint "Diode zener")
      (description "Silicon Planar Zener Diodes")
      (libsource (lib "Main_Board") (part "D Zener"))
    )
    (comp (ref "D24")
      (value "LED")
      (footprint "LED_0805_Blue")
      (description "LED SMD")
      (libsource (lib "Main_Board") (part "LED_SMD"))
    )
    (comp (ref "D25")
      (value "LED")
      (footprint "LED_0805_Blue")
      (description "LED SMD")
      (libsource (lib "Main_Board") (part "LED_SMD"))
    )
    (comp (ref "D26")
      (value "LED")
      (footprint "LED_0805_Blue")
      (description "LED SMD")
      (libsource (lib "Main_Board") (part "LED_SMD"))
    )
    (comp (ref "D27")
      (value "LED")
      (footprint "LED_0805_Blue")
      (description "LED SMD")
      (libsource (lib "Main_Board") (part "LED_SMD"))
    )
    (comp (ref "D28")
      (value "LED")
      (footprint "LED_0805_Blue")
      (description "LED SMD")
      (libsource (lib "Main_Board") (part "LED_SMD"))
    )
    (comp (ref "D29")
      (value "LED")
      (footprint "LED_0805_Blue")
      (description "LED SMD")
      (libsource (lib "Main_Board") (part "LED_SMD"))
    )
    (comp (ref "D30")
      (value "LED")
      (footprint "LED_0805_Blue")
      (description "LED SMD")
      (libsource (lib "Main_Board") (part "LED_SMD"))
    )
    (comp (ref "D31")
      (value "LED")
      (footprint "LED_0805_Blue")
      (description "LED SMD")
      (libsource (lib "Main_Board") (part "LED_SMD"))
    )
    (comp (ref "D32")
      (value "LED")
      (footprint "LED_0805_Blue")
      (description "LED SMD")
      (libsource (lib "Main_Board") (part "LED_SMD"))
    )
    (comp (ref "D33")
      (value "LED")
      (footprint "LED_0805_Blue")
      (description "LED SMD")
      (libsource (lib "Main_Board") (part "LED_SMD"))
    )
    (comp (ref "D34")
      (value "LED")
      (footprint "LED_0805_Blue")
      (description "LED SMD")
      (libsource (lib "Main_Board") (part "LED_SMD"))
    )
    (comp (ref "D35")
      (value "LED")
      (footprint "LED_0805_Blue")
      (description "LED SMD")
      (libsource (lib "Main_Board") (part "LED_SMD"))
    )
    (comp (ref "Dr1")
      (value "Drill")
      (footprint "Drill 3mm")
      (description "Drill 3mm")
      (libsource (lib "Main_Board") (part "Drill 3mm"))
    )
    (comp (ref "Dr2")
      (value "Drill")
      (footprint "Drill 3mm")
      (description "Drill 3mm")
      (libsource (lib "Main_Board") (part "Drill 3mm"))
    )
    (comp (ref "Dr3")
      (value "Drill")
      (footprint "Drill 3mm")
      (description "Drill 3mm")
      (libsource (lib "Main_Board") (part "Drill 3mm"))
    )
    (comp (ref "Dr4")
      (value "Drill")
      (footprint "Drill 3mm")
      (description "Drill 3mm")
      (libsource (lib "Main_Board") (part "Drill 3mm"))
    )
    (comp (ref "F1")
      (value "Ferrite")
      (footprint "Ferrite")
      (description "Ferrite bead")
      (libsource (lib "Main_Board") (part "Ferrite bead"))
    )
    (comp (ref "H1")
      (value "BL")
      (footprint "Header White 4")
      (description "Header white 4")
      (libsource (lib "Main_Board") (part "Header white 4"))
    )
    (comp (ref "H2")
      (value "IMU")
      (footprint "Header White 4")
      (description "Header white 4")
      (libsource (lib "Main_Board") (part "Header white 4"))
    )
    (comp (ref "H3")
      (value "PC")
      (footprint "Header White 4")
      (description "Header white 4")
      (libsource (lib "Main_Board") (part "Header white 4"))
    )
    (comp (ref "HD1")
      (value "IN 9")
      (footprint "Domino 2")
      (description "Domino 2 200mil")
      (libsource (lib "") (part "Domino 2_1"))
    )
    (comp (ref "HD2")
      (value "IN 1")
      (footprint "Domino 2")
      (description "Domino 2 200mil")
      (libsource (lib "") (part "Domino 2_1"))
    )
    (comp (ref "HD3")
      (value "24V IN")
      (footprint "Domino 2")
      (description "Domino 2 200mil")
      (libsource (lib "") (part "Domino 2_1"))
    )
    (comp (ref "HD4")
      (value "PWM 1")
      (footprint "Domino 4")
      (description "Domino 4 200mil")
      (libsource (lib "Main_Board") (part "Domino 4"))
    )
    (comp (ref "HD5")
      (value "ENC A1")
      (footprint "Domino 2")
      (description "Domino 2 200mil")
      (libsource (lib "") (part "Domino 2_1"))
    )
    (comp (ref "HD6")
      (value "IN 10")
      (footprint "Domino 2")
      (description "Domino 2 200mil")
      (libsource (lib "") (part "Domino 2_1"))
    )
    (comp (ref "HD7")
      (value "IN 2")
      (footprint "Domino 2")
      (description "Domino 2 200mil")
      (libsource (lib "") (part "Domino 2_1"))
    )
    (comp (ref "HD8")
      (value "ENC B1")
      (footprint "Domino 2")
      (description "Domino 2 200mil")
      (libsource (lib "") (part "Domino 2_1"))
    )
    (comp (ref "HD9")
      (value "IN 3")
      (footprint "Domino 2")
      (description "Domino 2 200mil")
      (libsource (lib "") (part "Domino 2_1"))
    )
    (comp (ref "HD10")
      (value "IN 11")
      (footprint "Domino 2")
      (description "Domino 2 200mil")
      (libsource (lib "") (part "Domino 2_1"))
    )
    (comp (ref "HD11")
      (value "PWM 2")
      (footprint "Domino 4")
      (description "Domino 4 200mil")
      (libsource (lib "Main_Board") (part "Domino 4"))
    )
    (comp (ref "HD12")
      (value "ENC A2")
      (footprint "Domino 2")
      (description "Domino 2 200mil")
      (libsource (lib "") (part "Domino 2_1"))
    )
    (comp (ref "HD13")
      (value "IN 4")
      (footprint "Domino 2")
      (description "Domino 2 200mil")
      (libsource (lib "") (part "Domino 2_1"))
    )
    (comp (ref "HD14")
      (value "IN 12")
      (footprint "Domino 2")
      (description "Domino 2 200mil")
      (libsource (lib "") (part "Domino 2_1"))
    )
    (comp (ref "HD15")
      (value "IN 5")
      (footprint "Domino 2")
      (description "Domino 2 200mil")
      (libsource (lib "") (part "Domino 2_1"))
    )
    (comp (ref "HD16")
      (value "IN 13")
      (footprint "Domino 2")
      (description "Domino 2 200mil")
      (libsource (lib "") (part "Domino 2_1"))
    )
    (comp (ref "HD17")
      (value "ENC B2")
      (footprint "Domino 2")
      (description "Domino 2 200mil")
      (libsource (lib "") (part "Domino 2_1"))
    )
    (comp (ref "HD18")
      (value "PWM 3")
      (footprint "Domino 4")
      (description "Domino 4 200mil")
      (libsource (lib "Main_Board") (part "Domino 4"))
    )
    (comp (ref "HD19")
      (value "IN 6")
      (footprint "Domino 2")
      (description "Domino 2 200mil")
      (libsource (lib "") (part "Domino 2_1"))
    )
    (comp (ref "HD20")
      (value "IN 14")
      (footprint "Domino 2")
      (description "Domino 2 200mil")
      (libsource (lib "") (part "Domino 2_1"))
    )
    (comp (ref "HD21")
      (value "ENC A3")
      (footprint "Domino 2")
      (description "Domino 2 200mil")
      (libsource (lib "") (part "Domino 2_1"))
    )
    (comp (ref "HD22")
      (value "IN 7")
      (footprint "Domino 2")
      (description "Domino 2 200mil")
      (libsource (lib "") (part "Domino 2_1"))
    )
    (comp (ref "HD23")
      (value "IN 15")
      (footprint "Domino 2")
      (description "Domino 2 200mil")
      (libsource (lib "") (part "Domino 2_1"))
    )
    (comp (ref "HD24")
      (value "PWM 4")
      (footprint "Domino 4")
      (description "Domino 4 200mil")
      (libsource (lib "Main_Board") (part "Domino 4"))
    )
    (comp (ref "HD25")
      (value "ENC B3")
      (footprint "Domino 2")
      (description "Domino 2 200mil")
      (libsource (lib "") (part "Domino 2_1"))
    )
    (comp (ref "HD26")
      (value "IN 8")
      (footprint "Domino 2")
      (description "Domino 2 200mil")
      (libsource (lib "") (part "Domino 2_1"))
    )
    (comp (ref "HD27")
      (value "IN 16")
      (footprint "Domino 2")
      (description "Domino 2 200mil")
      (libsource (lib "") (part "Domino 2_1"))
    )
    (comp (ref "HD28")
      (value "HMI")
      (footprint "Domino 3")
      (description "Domino 3 200mil")
      (libsource (lib "Main_Board") (part "Domino 3"))
    )
    (comp (ref "HD29")
      (value "ENC A4")
      (footprint "Domino 2")
      (description "Domino 2 200mil")
      (libsource (lib "") (part "Domino 2_1"))
    )
    (comp (ref "HD30")
      (value "PWM 5")
      (footprint "Domino 4")
      (description "Domino 4 200mil")
      (libsource (lib "Main_Board") (part "Domino 4"))
    )
    (comp (ref "HD31")
      (value "ENC B4")
      (footprint "Domino 2")
      (description "Domino 2 200mil")
      (libsource (lib "") (part "Domino 2_1"))
    )
    (comp (ref "HD32")
      (value "ADC")
      (footprint "Domino 4")
      (description "Domino 4 200mil")
      (libsource (lib "") (part "Domino 4_1"))
    )
    (comp (ref "HD33")
      (value "ENC A5")
      (footprint "Domino 2")
      (description "Domino 2 200mil")
      (libsource (lib "") (part "Domino 2_1"))
    )
    (comp (ref "HD34")
      (value "PWM 6")
      (footprint "Domino 4")
      (description "Domino 4 200mil")
      (libsource (lib "Main_Board") (part "Domino 4"))
    )
    (comp (ref "HD35")
      (value "OUT 6")
      (footprint "Domino 2")
      (description "Domino 2 200mil")
      (libsource (lib "Main_Board") (part "Domino 2"))
    )
    (comp (ref "HD36")
      (value "ENC B5")
      (footprint "Domino 2")
      (description "Domino 2 200mil")
      (libsource (lib "") (part "Domino 2_1"))
    )
    (comp (ref "HD37")
      (value "OUT 7")
      (footprint "Domino 2")
      (description "Domino 2 200mil")
      (libsource (lib "Main_Board") (part "Domino 2"))
    )
    (comp (ref "HD38")
      (value "OUT 8")
      (footprint "Domino 2")
      (description "Domino 2 200mil")
      (libsource (lib "Main_Board") (part "Domino 2"))
    )
    (comp (ref "HD39")
      (value "ENC A6")
      (footprint "Domino 2")
      (description "Domino 2 200mil")
      (libsource (lib "") (part "Domino 2_1"))
    )
    (comp (ref "HD40")
      (value "Relay")
      (footprint "Domino 8")
      (description "Domino 8 200mil")
      (libsource (lib "Main_Board") (part "Domino 8"))
    )
    (comp (ref "HD41")
      (value "OUT 9")
      (footprint "Domino 2")
      (description "Domino 2 200mil")
      (libsource (lib "Main_Board") (part "Domino 2"))
    )
    (comp (ref "HD42")
      (value "ENC B6")
      (footprint "Domino 2")
      (description "Domino 2 200mil")
      (libsource (lib "") (part "Domino 2_1"))
    )
    (comp (ref "HD43")
      (value "OUT 10")
      (footprint "Domino 2")
      (description "Domino 2 200mil")
      (libsource (lib "Main_Board") (part "Domino 2"))
    )
    (comp (ref "HD44")
      (value "OUT 11")
      (footprint "Domino 2")
      (description "Domino 2 200mil")
      (libsource (lib "Main_Board") (part "Domino 2"))
    )
    (comp (ref "IC1")
      (value "MAX485")
      (footprint "SOIC8")
      (description "RS232 - RS485 (Same sn75176)")
      (libsource (lib "Main_Board") (part "MAX485"))
    )
    (comp (ref "IC2")
      (value "LM1117-3V3")
      (footprint "SOT223-4N")
      (description "Available in 1.8V, 2.5V, 2.85V, 3.3V, 5V, and  Adjustable Versions")
      (libsource (lib "Main_Board") (part "LM1117"))
    )
    (comp (ref "IC3")
      (value "MAX485")
      (footprint "SOIC8")
      (description "RS232 - RS485 (Same sn75176)")
      (libsource (lib "Main_Board") (part "MAX485"))
    )
    (comp (ref "IC4")
      (value "MAX485")
      (footprint "SOIC8")
      (description "RS232 - RS485 (Same sn75176)")
      (libsource (lib "Main_Board") (part "MAX485"))
    )
    (comp (ref "IC5")
      (value "MAX485")
      (footprint "SOIC8")
      (description "RS232 - RS485 (Same sn75176)")
      (libsource (lib "Main_Board") (part "MAX485"))
    )
    (comp (ref "IC6")
      (value "MAX485")
      (footprint "SOIC8")
      (description "RS232 - RS485 (Same sn75176)")
      (libsource (lib "Main_Board") (part "MAX485"))
    )
    (comp (ref "IC7")
      (value "24Cxx")
      (footprint "SOIC8")
      (description "Standard 2-Wire Bus Interface Serial EEPROM")
      (fields (field (name "COPYRIGHT BY") "VanDungEvn"))
      (libsource (lib "Main_Board") (part "24Cxx"))
    )
    (comp (ref "IC8")
      (value "MAX485")
      (footprint "SOIC8")
      (description "RS232 - RS485 (Same sn75176)")
      (libsource (lib "Main_Board") (part "MAX485"))
    )
    (comp (ref "IC9")
      (value "RS485")
      (footprint "RS485_Module")
      (description "Module RS485")
      (libsource (lib "Main_Board") (part "RS485_Module"))
    )
    (comp (ref "IC10")
      (value "MAX485")
      (footprint "SOIC8")
      (description "RS232 - RS485 (Same sn75176)")
      (libsource (lib "Main_Board") (part "MAX485"))
    )
    (comp (ref "IC11")
      (value "LM358")
      (footprint "SO8-200mil")
      (description "Low-Power Dual Operational Amplifier")
      (libsource (lib "Main_Board") (part "LM358"))
    )
    (comp (ref "IC12")
      (value "MAX485")
      (footprint "SOIC8")
      (description "RS232 - RS485 (Same sn75176)")
      (libsource (lib "Main_Board") (part "MAX485"))
    )
    (comp (ref "IC13")
      (value "MAX485")
      (footprint "SOIC8")
      (description "RS232 - RS485 (Same sn75176)")
      (libsource (lib "Main_Board") (part "MAX485"))
    )
    (comp (ref "IC14")
      (value "MAX485")
      (footprint "SOIC8")
      (description "RS232 - RS485 (Same sn75176)")
      (libsource (lib "Main_Board") (part "MAX485"))
    )
    (comp (ref "IC15")
      (value "MAX485")
      (footprint "SOIC8")
      (description "RS232 - RS485 (Same sn75176)")
      (libsource (lib "Main_Board") (part "MAX485"))
    )
    (comp (ref "IC16")
      (value "MAX485")
      (footprint "SOIC8")
      (description "RS232 - RS485 (Same sn75176)")
      (libsource (lib "Main_Board") (part "MAX485"))
    )
    (comp (ref "L1")
      (value "100uH")
      (footprint "INDUCTOR_SMD")
      (description "Inductor")
      (libsource (lib "Main_Board") (part "L1"))
    )
    (comp (ref "OP1")
      (value "PC817")
      (footprint "SOP4 2.54")
      (description "OPTO")
      (libsource (lib "Main_Board") (part "PC817"))
    )
    (comp (ref "OP2")
      (value "PC817")
      (footprint "SOP4 2.54")
      (description "OPTO")
      (libsource (lib "Main_Board") (part "PC817"))
    )
    (comp (ref "OP3")
      (value "HCPL2631")
      (footprint "6N137SMD")
      (description "High CMR, High Speed TTL Compatible Optocouplers")
      (libsource (lib "Main_Board") (part "HCPL2631"))
    )
    (comp (ref "OP4")
      (value "PC817")
      (footprint "SOP4 2.54")
      (description "OPTO")
      (libsource (lib "Main_Board") (part "PC817"))
    )
    (comp (ref "OP5")
      (value "PC817")
      (footprint "SOP4 2.54")
      (description "OPTO")
      (libsource (lib "Main_Board") (part "PC817"))
    )
    (comp (ref "OP6")
      (value "PC817")
      (footprint "SOP4 2.54")
      (description "OPTO")
      (libsource (lib "Main_Board") (part "PC817"))
    )
    (comp (ref "OP7")
      (value "PC817")
      (footprint "SOP4 2.54")
      (description "OPTO")
      (libsource (lib "Main_Board") (part "PC817"))
    )
    (comp (ref "OP8")
      (value "HCPL2631")
      (footprint "6N137SMD")
      (description "High CMR, High Speed TTL Compatible Optocouplers")
      (libsource (lib "Main_Board") (part "HCPL2631"))
    )
    (comp (ref "OP9")
      (value "PC817")
      (footprint "SOP4 2.54")
      (description "OPTO")
      (libsource (lib "Main_Board") (part "PC817"))
    )
    (comp (ref "OP10")
      (value "PC817")
      (footprint "SOP4 2.54")
      (description "OPTO")
      (libsource (lib "Main_Board") (part "PC817"))
    )
    (comp (ref "OP11")
      (value "PC817")
      (footprint "SOP4 2.54")
      (description "OPTO")
      (libsource (lib "Main_Board") (part "PC817"))
    )
    (comp (ref "OP12")
      (value "PC817")
      (footprint "SOP4 2.54")
      (description "OPTO")
      (libsource (lib "Main_Board") (part "PC817"))
    )
    (comp (ref "OP13")
      (value "HCPL2631")
      (footprint "6N137SMD")
      (description "High CMR, High Speed TTL Compatible Optocouplers")
      (libsource (lib "Main_Board") (part "HCPL2631"))
    )
    (comp (ref "OP14")
      (value "PC817")
      (footprint "SOP4 2.54")
      (description "OPTO")
      (libsource (lib "Main_Board") (part "PC817"))
    )
    (comp (ref "OP15")
      (value "PC817")
      (footprint "SOP4 2.54")
      (description "OPTO")
      (libsource (lib "Main_Board") (part "PC817"))
    )
    (comp (ref "OP16")
      (value "PC817")
      (footprint "SOP4 2.54")
      (description "OPTO")
      (libsource (lib "Main_Board") (part "PC817"))
    )
    (comp (ref "OP17")
      (value "PC817")
      (footprint "SOP4 2.54")
      (description "OPTO")
      (libsource (lib "Main_Board") (part "PC817"))
    )
    (comp (ref "OP18")
      (value "HCPL2631")
      (footprint "6N137SMD")
      (description "High CMR, High Speed TTL Compatible Optocouplers")
      (libsource (lib "Main_Board") (part "HCPL2631"))
    )
    (comp (ref "OP19")
      (value "PC817")
      (footprint "SOP4 2.54")
      (description "OPTO")
      (libsource (lib "Main_Board") (part "PC817"))
    )
    (comp (ref "OP20")
      (value "PC817")
      (footprint "SOP4 2.54")
      (description "OPTO")
      (libsource (lib "Main_Board") (part "PC817"))
    )
    (comp (ref "OP21")
      (value "HCPL2631")
      (footprint "6N137SMD")
      (description "High CMR, High Speed TTL Compatible Optocouplers")
      (libsource (lib "Main_Board") (part "HCPL2631"))
    )
    (comp (ref "OP22")
      (value "HCPL2631")
      (footprint "6N137SMD")
      (description "High CMR, High Speed TTL Compatible Optocouplers")
      (libsource (lib "Main_Board") (part "HCPL2631"))
    )
    (comp (ref "OP23")
      (value "PC817")
      (footprint "SOP4 2.54")
      (description "OPTO")
      (libsource (lib "Main_Board") (part "PC817"))
    )
    (comp (ref "OP24")
      (value "PC817")
      (footprint "SOP4 2.54")
      (description "OPTO")
      (libsource (lib "Main_Board") (part "PC817"))
    )
    (comp (ref "OP25")
      (value "PC817")
      (footprint "SOP4 2.54")
      (description "OPTO")
      (libsource (lib "Main_Board") (part "PC817"))
    )
    (comp (ref "OP26")
      (value "PC817")
      (footprint "SOP4 2.54")
      (description "OPTO")
      (libsource (lib "Main_Board") (part "PC817"))
    )
    (comp (ref "OP27")
      (value "PC817")
      (footprint "SOP4 2.54")
      (description "OPTO")
      (libsource (lib "Main_Board") (part "PC817"))
    )
    (comp (ref "OP28")
      (value "PC817")
      (footprint "SOP4 2.54")
      (description "OPTO")
      (libsource (lib "Main_Board") (part "PC817"))
    )
    (comp (ref "OP29")
      (value "PC817")
      (footprint "SOP4 2.54")
      (description "OPTO")
      (libsource (lib "Main_Board") (part "PC817"))
    )
    (comp (ref "OP30")
      (value "PC817")
      (footprint "SOP4 2.54")
      (description "OPTO")
      (libsource (lib "Main_Board") (part "PC817"))
    )
    (comp (ref "OP31")
      (value "PC817")
      (footprint "SOP4 2.54")
      (description "OPTO")
      (libsource (lib "Main_Board") (part "PC817"))
    )
    (comp (ref "OP32")
      (value "PC817")
      (footprint "SOP4 2.54")
      (description "OPTO")
      (libsource (lib "Main_Board") (part "PC817"))
    )
    (comp (ref "OP33")
      (value "PC817")
      (footprint "SOP4 2.54")
      (description "OPTO")
      (libsource (lib "Main_Board") (part "PC817"))
    )
    (comp (ref "OP34")
      (value "PC817")
      (footprint "SOP4 2.54")
      (description "OPTO")
      (libsource (lib "Main_Board") (part "PC817"))
    )
    (comp (ref "Q1")
      (value "KSC2383")
      (footprint "To-92a")
      (description "Bipolar Small Signal NPN Epitaxial Transistor")
      (libsource (lib "Main_Board") (part "KSC2383"))
    )
    (comp (ref "Q2")
      (value "KSC2383")
      (footprint "To-92a")
      (description "Bipolar Small Signal NPN Epitaxial Transistor")
      (libsource (lib "Main_Board") (part "KSC2383"))
    )
    (comp (ref "Q3")
      (value "KSC2383")
      (footprint "To-92a")
      (description "Bipolar Small Signal NPN Epitaxial Transistor")
      (libsource (lib "Main_Board") (part "KSC2383"))
    )
    (comp (ref "Q4")
      (value "KSC2383")
      (footprint "To-92a")
      (description "Bipolar Small Signal NPN Epitaxial Transistor")
      (libsource (lib "Main_Board") (part "KSC2383"))
    )
    (comp (ref "Q5")
      (value "KSC2383")
      (footprint "To-92a")
      (description "Bipolar Small Signal NPN Epitaxial Transistor")
      (libsource (lib "Main_Board") (part "KSC2383"))
    )
    (comp (ref "Q6")
      (value "KSC2383")
      (footprint "To-92a")
      (description "Bipolar Small Signal NPN Epitaxial Transistor")
      (libsource (lib "Main_Board") (part "KSC2383"))
    )
    (comp (ref "R1")
      (value "10k")
      (footprint "RES-SM-0805")
      (description "Resistor")
      (fields
        (field (name "MANUFACTURER") "Generic Components")
        (field (name "PUBLISHER") "Altium Hobart Technology Centre")
      )
      (libsource (lib "Main_Board") (part "Res-SMD"))
    )
    (comp (ref "R2")
      (value "10k")
      (footprint "RES-SM-0805")
      (description "Resistor")
      (fields
        (field (name "MANUFACTURER") "Generic Components")
        (field (name "PUBLISHER") "Altium Hobart Technology Centre")
      )
      (libsource (lib "Main_Board") (part "Res-SMD"))
    )
    (comp (ref "R3")
      (value "10k")
      (footprint "RES-SM-0805")
      (description "Resistor")
      (fields
        (field (name "MANUFACTURER") "Generic Components")
        (field (name "PUBLISHER") "Altium Hobart Technology Centre")
      )
      (libsource (lib "Main_Board") (part "Res-SMD"))
    )
    (comp (ref "R4")
      (value "4.7k")
      (footprint "RES-SM-0805")
      (description "Resistor")
      (fields
        (field (name "MANUFACTURER") "Generic Components")
        (field (name "PUBLISHER") "Altium Hobart Technology Centre")
      )
      (libsource (lib "Main_Board") (part "Res-SMD"))
    )
    (comp (ref "R5")
      (value "4.7k")
      (footprint "RES-SM-0805")
      (description "Resistor")
      (fields
        (field (name "MANUFACTURER") "Generic Components")
        (field (name "PUBLISHER") "Altium Hobart Technology Centre")
      )
      (libsource (lib "Main_Board") (part "Res-SMD"))
    )
    (comp (ref "R6")
      (value "4.7k")
      (footprint "RES-SM-0805")
      (description "Resistor")
      (fields
        (field (name "MANUFACTURER") "Generic Components")
        (field (name "PUBLISHER") "Altium Hobart Technology Centre")
      )
      (libsource (lib "Main_Board") (part "Res-SMD"))
    )
    (comp (ref "R7")
      (value "4.7k")
      (footprint "RES-SM-0805")
      (description "Resistor")
      (fields
        (field (name "MANUFACTURER") "Generic Components")
        (field (name "PUBLISHER") "Altium Hobart Technology Centre")
      )
      (libsource (lib "Main_Board") (part "Res-SMD"))
    )
    (comp (ref "R8")
      (value "120")
      (footprint "RES-SM-0805")
      (description "Resistor")
      (fields
        (field (name "MANUFACTURER") "Generic Components")
        (field (name "PUBLISHER") "Altium Hobart Technology Centre")
      )
      (libsource (lib "Main_Board") (part "Res-SMD"))
    )
    (comp (ref "R9")
      (value "10k")
      (footprint "RES-SM-0805")
      (description "Resistor")
      (fields
        (field (name "MANUFACTURER") "Generic Components")
        (field (name "PUBLISHER") "Altium Hobart Technology Centre")
      )
      (libsource (lib "Main_Board") (part "Res-SMD"))
    )
    (comp (ref "R10")
      (value "10k")
      (footprint "RES-SM-0805")
      (description "Resistor")
      (fields
        (field (name "MANUFACTURER") "Generic Components")
        (field (name "PUBLISHER") "Altium Hobart Technology Centre")
      )
      (libsource (lib "Main_Board") (part "Res-SMD"))
    )
    (comp (ref "R11")
      (value "470")
      (footprint "RES-SM-0805")
      (description "Resistor")
      (fields
        (field (name "MANUFACTURER") "Generic Components")
        (field (name "PUBLISHER") "Altium Hobart Technology Centre")
      )
      (libsource (lib "Main_Board") (part "Res-SMD"))
    )
    (comp (ref "R12")
      (value "22k")
      (footprint "RES-SM-0805")
      (description "Resistor")
      (fields
        (field (name "MANUFACTURER") "Generic Components")
        (field (name "PUBLISHER") "Altium Hobart Technology Centre")
      )
      (libsource (lib "Main_Board") (part "Res-SMD"))
    )
    (comp (ref "R13")
      (value "330")
      (footprint "RES-SM-0805")
      (description "Resistor")
      (fields
        (field (name "MANUFACTURER") "Generic Components")
        (field (name "PUBLISHER") "Altium Hobart Technology Centre")
      )
      (libsource (lib "Main_Board") (part "Res-SMD"))
    )
    (comp (ref "R14")
      (value "10k")
      (footprint "RES-SM-0805")
      (description "Resistor")
      (fields
        (field (name "MANUFACTURER") "Generic Components")
        (field (name "PUBLISHER") "Altium Hobart Technology Centre")
      )
      (libsource (lib "Main_Board") (part "Res-SMD"))
    )
    (comp (ref "R15")
      (value "10k")
      (footprint "RES-SM-0805")
      (description "Resistor")
      (fields
        (field (name "MANUFACTURER") "Generic Components")
        (field (name "PUBLISHER") "Altium Hobart Technology Centre")
      )
      (libsource (lib "Main_Board") (part "Res-SMD"))
    )
    (comp (ref "R16")
      (value "10k")
      (footprint "RES-SM-0805")
      (description "Resistor")
      (fields
        (field (name "MANUFACTURER") "Generic Components")
        (field (name "PUBLISHER") "Altium Hobart Technology Centre")
      )
      (libsource (lib "Main_Board") (part "Res-SMD"))
    )
    (comp (ref "R17")
      (value "120")
      (footprint "RES-SM-0805")
      (description "Resistor")
      (fields
        (field (name "MANUFACTURER") "Generic Components")
        (field (name "PUBLISHER") "Altium Hobart Technology Centre")
      )
      (libsource (lib "Main_Board") (part "Res-SMD"))
    )
    (comp (ref "R18")
      (value "4.7k")
      (footprint "RES-SM-0805")
      (description "Resistor")
      (fields
        (field (name "MANUFACTURER") "Generic Components")
        (field (name "PUBLISHER") "Altium Hobart Technology Centre")
      )
      (libsource (lib "Main_Board") (part "Res-SMD"))
    )
    (comp (ref "R19")
      (value "4.7k")
      (footprint "RES-SM-0805")
      (description "Resistor")
      (fields
        (field (name "MANUFACTURER") "Generic Components")
        (field (name "PUBLISHER") "Altium Hobart Technology Centre")
      )
      (libsource (lib "Main_Board") (part "Res-SMD"))
    )
    (comp (ref "R20")
      (value "10k")
      (footprint "RES-SM-0805")
      (description "Resistor")
      (fields
        (field (name "MANUFACTURER") "Generic Components")
        (field (name "PUBLISHER") "Altium Hobart Technology Centre")
      )
      (libsource (lib "Main_Board") (part "Res-SMD"))
    )
    (comp (ref "R21")
      (value "4.7k")
      (footprint "RES-SM-0805")
      (description "Resistor")
      (fields
        (field (name "MANUFACTURER") "Generic Components")
        (field (name "PUBLISHER") "Altium Hobart Technology Centre")
      )
      (libsource (lib "Main_Board") (part "Res-SMD"))
    )
    (comp (ref "R22")
      (value "4.7k")
      (footprint "RES-SM-0805")
      (description "Resistor")
      (fields
        (field (name "MANUFACTURER") "Generic Components")
        (field (name "PUBLISHER") "Altium Hobart Technology Centre")
      )
      (libsource (lib "Main_Board") (part "Res-SMD"))
    )
    (comp (ref "R23")
      (value "10k")
      (footprint "RES-SM-0805")
      (description "Resistor")
      (fields
        (field (name "MANUFACTURER") "Generic Components")
        (field (name "PUBLISHER") "Altium Hobart Technology Centre")
      )
      (libsource (lib "Main_Board") (part "Res-SMD"))
    )
    (comp (ref "R24")
      (value "10k")
      (footprint "RES-SM-0805")
      (description "Resistor")
      (fields
        (field (name "MANUFACTURER") "Generic Components")
        (field (name "PUBLISHER") "Altium Hobart Technology Centre")
      )
      (libsource (lib "Main_Board") (part "Res-SMD"))
    )
    (comp (ref "R25")
      (value "120")
      (footprint "RES-SM-0805")
      (description "Resistor")
      (fields
        (field (name "MANUFACTURER") "Generic Components")
        (field (name "PUBLISHER") "Altium Hobart Technology Centre")
      )
      (libsource (lib "Main_Board") (part "Res-SMD"))
    )
    (comp (ref "R26")
      (value "10k")
      (footprint "RES-SM-0805")
      (description "Resistor")
      (fields
        (field (name "MANUFACTURER") "Generic Components")
        (field (name "PUBLISHER") "Altium Hobart Technology Centre")
      )
      (libsource (lib "Main_Board") (part "Res-SMD"))
    )
    (comp (ref "R27")
      (value "10k")
      (footprint "RES-SM-0805")
      (description "Resistor")
      (fields
        (field (name "MANUFACTURER") "Generic Components")
        (field (name "PUBLISHER") "Altium Hobart Technology Centre")
      )
      (libsource (lib "Main_Board") (part "Res-SMD"))
    )
    (comp (ref "R28")
      (value "10k")
      (footprint "RES-SM-0805")
      (description "Resistor")
      (fields
        (field (name "MANUFACTURER") "Generic Components")
        (field (name "PUBLISHER") "Altium Hobart Technology Centre")
      )
      (libsource (lib "Main_Board") (part "Res-SMD"))
    )
    (comp (ref "R29")
      (value "10k")
      (footprint "RES-SM-0805")
      (description "Resistor")
      (fields
        (field (name "MANUFACTURER") "Generic Components")
        (field (name "PUBLISHER") "Altium Hobart Technology Centre")
      )
      (libsource (lib "Main_Board") (part "Res-SMD"))
    )
    (comp (ref "R30")
      (value "4.7k")
      (footprint "RES-SM-0805")
      (description "Resistor")
      (fields
        (field (name "MANUFACTURER") "Generic Components")
        (field (name "PUBLISHER") "Altium Hobart Technology Centre")
      )
      (libsource (lib "Main_Board") (part "Res-SMD"))
    )
    (comp (ref "R31")
      (value "120")
      (footprint "RES-SM-0805")
      (description "Resistor")
      (fields
        (field (name "MANUFACTURER") "Generic Components")
        (field (name "PUBLISHER") "Altium Hobart Technology Centre")
      )
      (libsource (lib "Main_Board") (part "Res-SMD"))
    )
    (comp (ref "R32")
      (value "4.7k")
      (footprint "RES-SM-0805")
      (description "Resistor")
      (fields
        (field (name "MANUFACTURER") "Generic Components")
        (field (name "PUBLISHER") "Altium Hobart Technology Centre")
      )
      (libsource (lib "Main_Board") (part "Res-SMD"))
    )
    (comp (ref "R33")
      (value "10k")
      (footprint "RES-SM-0805")
      (description "Resistor")
      (fields
        (field (name "MANUFACTURER") "Generic Components")
        (field (name "PUBLISHER") "Altium Hobart Technology Centre")
      )
      (libsource (lib "Main_Board") (part "Res-SMD"))
    )
    (comp (ref "R34")
      (value "4.7k")
      (footprint "RES-SM-0805")
      (description "Resistor")
      (fields
        (field (name "MANUFACTURER") "Generic Components")
        (field (name "PUBLISHER") "Altium Hobart Technology Centre")
      )
      (libsource (lib "Main_Board") (part "Res-SMD"))
    )
    (comp (ref "R35")
      (value "10k")
      (footprint "RES-SM-0805")
      (description "Resistor")
      (fields
        (field (name "MANUFACTURER") "Generic Components")
        (field (name "PUBLISHER") "Altium Hobart Technology Centre")
      )
      (libsource (lib "Main_Board") (part "Res-SMD"))
    )
    (comp (ref "R36")
      (value "4.7k")
      (footprint "RES-SM-0805")
      (description "Resistor")
      (fields
        (field (name "MANUFACTURER") "Generic Components")
        (field (name "PUBLISHER") "Altium Hobart Technology Centre")
      )
      (libsource (lib "Main_Board") (part "Res-SMD"))
    )
    (comp (ref "R37")
      (value "10k")
      (footprint "RES-SM-0805")
      (description "Resistor")
      (fields
        (field (name "MANUFACTURER") "Generic Components")
        (field (name "PUBLISHER") "Altium Hobart Technology Centre")
      )
      (libsource (lib "Main_Board") (part "Res-SMD"))
    )
    (comp (ref "R38")
      (value "4.7k")
      (footprint "RES-SM-0805")
      (description "Resistor")
      (fields
        (field (name "MANUFACTURER") "Generic Components")
        (field (name "PUBLISHER") "Altium Hobart Technology Centre")
      )
      (libsource (lib "Main_Board") (part "Res-SMD"))
    )
    (comp (ref "R39")
      (value "4.7k")
      (footprint "RES-SM-0805")
      (description "Resistor")
      (fields
        (field (name "MANUFACTURER") "Generic Components")
        (field (name "PUBLISHER") "Altium Hobart Technology Centre")
      )
      (libsource (lib "Main_Board") (part "Res-SMD"))
    )
    (comp (ref "R40")
      (value "120")
      (footprint "RES-SM-0805")
      (description "Resistor")
      (fields
        (field (name "MANUFACTURER") "Generic Components")
        (field (name "PUBLISHER") "Altium Hobart Technology Centre")
      )
      (libsource (lib "Main_Board") (part "Res-SMD"))
    )
    (comp (ref "R41")
      (value "10k")
      (footprint "RES-SM-0805")
      (description "Resistor")
      (fields
        (field (name "MANUFACTURER") "Generic Components")
        (field (name "PUBLISHER") "Altium Hobart Technology Centre")
      )
      (libsource (lib "Main_Board") (part "Res-SMD"))
    )
    (comp (ref "R42")
      (value "10k")
      (footprint "RES-SM-0805")
      (description "Resistor")
      (fields
        (field (name "MANUFACTURER") "Generic Components")
        (field (name "PUBLISHER") "Altium Hobart Technology Centre")
      )
      (libsource (lib "Main_Board") (part "Res-SMD"))
    )
    (comp (ref "R43")
      (value "10k")
      (footprint "RES-SM-0805")
      (description "Resistor")
      (fields
        (field (name "MANUFACTURER") "Generic Components")
        (field (name "PUBLISHER") "Altium Hobart Technology Centre")
      )
      (libsource (lib "Main_Board") (part "Res-SMD"))
    )
    (comp (ref "R44")
      (value "4.7k")
      (footprint "RES-SM-0805")
      (description "Resistor")
      (fields
        (field (name "MANUFACTURER") "Generic Components")
        (field (name "PUBLISHER") "Altium Hobart Technology Centre")
      )
      (libsource (lib "Main_Board") (part "Res-SMD"))
    )
    (comp (ref "R45")
      (value "4.7k")
      (footprint "RES-SM-0805")
      (description "Resistor")
      (fields
        (field (name "MANUFACTURER") "Generic Components")
        (field (name "PUBLISHER") "Altium Hobart Technology Centre")
      )
      (libsource (lib "Main_Board") (part "Res-SMD"))
    )
    (comp (ref "R46")
      (value "4.7k")
      (footprint "RES-SM-0805")
      (description "Resistor")
      (fields
        (field (name "MANUFACTURER") "Generic Components")
        (field (name "PUBLISHER") "Altium Hobart Technology Centre")
      )
      (libsource (lib "Main_Board") (part "Res-SMD"))
    )
    (comp (ref "R47")
      (value "10k")
      (footprint "RES-SM-0805")
      (description "Resistor")
      (fields
        (field (name "MANUFACTURER") "Generic Components")
        (field (name "PUBLISHER") "Altium Hobart Technology Centre")
      )
      (libsource (lib "Main_Board") (part "Res-SMD"))
    )
    (comp (ref "R48")
      (value "10k")
      (footprint "RES-SM-0805")
      (description "Resistor")
      (fields
        (field (name "MANUFACTURER") "Generic Components")
        (field (name "PUBLISHER") "Altium Hobart Technology Centre")
      )
      (libsource (lib "Main_Board") (part "Res-SMD"))
    )
    (comp (ref "R49")
      (value "4.7k")
      (footprint "RES-SM-0805")
      (description "Resistor")
      (fields
        (field (name "MANUFACTURER") "Generic Components")
        (field (name "PUBLISHER") "Altium Hobart Technology Centre")
      )
      (libsource (lib "Main_Board") (part "Res-SMD"))
    )
    (comp (ref "R50")
      (value "120")
      (footprint "RES-SM-0805")
      (description "Resistor")
      (fields
        (field (name "MANUFACTURER") "Generic Components")
        (field (name "PUBLISHER") "Altium Hobart Technology Centre")
      )
      (libsource (lib "Main_Board") (part "Res-SMD"))
    )
    (comp (ref "R51")
      (value "10k")
      (footprint "RES-SM-0805")
      (description "Resistor")
      (fields
        (field (name "MANUFACTURER") "Generic Components")
        (field (name "PUBLISHER") "Altium Hobart Technology Centre")
      )
      (libsource (lib "Main_Board") (part "Res-SMD"))
    )
    (comp (ref "R52")
      (value "120")
      (footprint "RES-SM-0805")
      (description "Resistor")
      (fields
        (field (name "MANUFACTURER") "Generic Components")
        (field (name "PUBLISHER") "Altium Hobart Technology Centre")
      )
      (libsource (lib "Main_Board") (part "Res-SMD"))
    )
    (comp (ref "R53")
      (value "4.7k")
      (footprint "RES-SM-0805")
      (description "Resistor")
      (fields
        (field (name "MANUFACTURER") "Generic Components")
        (field (name "PUBLISHER") "Altium Hobart Technology Centre")
      )
      (libsource (lib "Main_Board") (part "Res-SMD"))
    )
    (comp (ref "R54")
      (value "4.7k")
      (footprint "RES-SM-0805")
      (description "Resistor")
      (fields
        (field (name "MANUFACTURER") "Generic Components")
        (field (name "PUBLISHER") "Altium Hobart Technology Centre")
      )
      (libsource (lib "Main_Board") (part "Res-SMD"))
    )
    (comp (ref "R55")
      (value "10k")
      (footprint "RES-SM-0805")
      (description "Resistor")
      (fields
        (field (name "MANUFACTURER") "Generic Components")
        (field (name "PUBLISHER") "Altium Hobart Technology Centre")
      )
      (libsource (lib "Main_Board") (part "Res-SMD"))
    )
    (comp (ref "R56")
      (value "4.7k")
      (footprint "RES-SM-0805")
      (description "Resistor")
      (fields
        (field (name "MANUFACTURER") "Generic Components")
        (field (name "PUBLISHER") "Altium Hobart Technology Centre")
      )
      (libsource (lib "Main_Board") (part "Res-SMD"))
    )
    (comp (ref "R57")
      (value "4.7k")
      (footprint "RES-SM-0805")
      (description "Resistor")
      (fields
        (field (name "MANUFACTURER") "Generic Components")
        (field (name "PUBLISHER") "Altium Hobart Technology Centre")
      )
      (libsource (lib "Main_Board") (part "Res-SMD"))
    )
    (comp (ref "R58")
      (value "120")
      (footprint "RES-SM-0805")
      (description "Resistor")
      (fields
        (field (name "MANUFACTURER") "Generic Components")
        (field (name "PUBLISHER") "Altium Hobart Technology Centre")
      )
      (libsource (lib "Main_Board") (part "Res-SMD"))
    )
    (comp (ref "R59")
      (value "10k")
      (footprint "RES-SM-0805")
      (description "Resistor")
      (fields
        (field (name "MANUFACTURER") "Generic Components")
        (field (name "PUBLISHER") "Altium Hobart Technology Centre")
      )
      (libsource (lib "Main_Board") (part "Res-SMD"))
    )
    (comp (ref "R60")
      (value "4.7k")
      (footprint "RES-SM-0805")
      (description "Resistor")
      (fields
        (field (name "MANUFACTURER") "Generic Components")
        (field (name "PUBLISHER") "Altium Hobart Technology Centre")
      )
      (libsource (lib "Main_Board") (part "Res-SMD"))
    )
    (comp (ref "R61")
      (value "4.7k")
      (footprint "RES-SM-0805")
      (description "Resistor")
      (fields
        (field (name "MANUFACTURER") "Generic Components")
        (field (name "PUBLISHER") "Altium Hobart Technology Centre")
      )
      (libsource (lib "Main_Board") (part "Res-SMD"))
    )
    (comp (ref "R62")
      (value "120")
      (footprint "RES-SM-0805")
      (description "Resistor")
      (fields
        (field (name "MANUFACTURER") "Generic Components")
        (field (name "PUBLISHER") "Altium Hobart Technology Centre")
      )
      (libsource (lib "Main_Board") (part "Res-SMD"))
    )
    (comp (ref "R63")
      (value "4.7k")
      (footprint "RES-SM-0805")
      (description "Resistor")
      (fields
        (field (name "MANUFACTURER") "Generic Components")
        (field (name "PUBLISHER") "Altium Hobart Technology Centre")
      )
      (libsource (lib "Main_Board") (part "Res-SMD"))
    )
    (comp (ref "R64")
      (value "1k")
      (footprint "RES-SM-0805")
      (description "Resistor")
      (fields
        (field (name "MANUFACTURER") "Generic Components")
        (field (name "PUBLISHER") "Altium Hobart Technology Centre")
      )
      (libsource (lib "Main_Board") (part "Res-SMD"))
    )
    (comp (ref "R65")
      (value "4.7k")
      (footprint "RES-SM-0805")
      (description "Resistor")
      (fields
        (field (name "MANUFACTURER") "Generic Components")
        (field (name "PUBLISHER") "Altium Hobart Technology Centre")
      )
      (libsource (lib "Main_Board") (part "Res-SMD"))
    )
    (comp (ref "R66")
      (value "1k")
      (footprint "RES-SM-0805")
      (description "Resistor")
      (fields
        (field (name "MANUFACTURER") "Generic Components")
        (field (name "PUBLISHER") "Altium Hobart Technology Centre")
      )
      (libsource (lib "Main_Board") (part "Res-SMD"))
    )
    (comp (ref "R67")
      (value "4.7k")
      (footprint "RES-SM-0805")
      (description "Resistor")
      (fields
        (field (name "MANUFACTURER") "Generic Components")
        (field (name "PUBLISHER") "Altium Hobart Technology Centre")
      )
      (libsource (lib "Main_Board") (part "Res-SMD"))
    )
    (comp (ref "R68")
      (value "4.7k")
      (footprint "RES-SM-0805")
      (description "Resistor")
      (fields
        (field (name "MANUFACTURER") "Generic Components")
        (field (name "PUBLISHER") "Altium Hobart Technology Centre")
      )
      (libsource (lib "Main_Board") (part "Res-SMD"))
    )
    (comp (ref "R69")
      (value "10k")
      (footprint "RES-SM-0805")
      (description "Resistor")
      (fields
        (field (name "MANUFACTURER") "Generic Components")
        (field (name "PUBLISHER") "Altium Hobart Technology Centre")
      )
      (libsource (lib "Main_Board") (part "Res-SMD"))
    )
    (comp (ref "R70")
      (value "1k")
      (footprint "RES-SM-0805")
      (description "Resistor")
      (fields
        (field (name "MANUFACTURER") "Generic Components")
        (field (name "PUBLISHER") "Altium Hobart Technology Centre")
      )
      (libsource (lib "Main_Board") (part "Res-SMD"))
    )
    (comp (ref "R71")
      (value "1k")
      (footprint "RES-SM-0805")
      (description "Resistor")
      (fields
        (field (name "MANUFACTURER") "Generic Components")
        (field (name "PUBLISHER") "Altium Hobart Technology Centre")
      )
      (libsource (lib "Main_Board") (part "Res-SMD"))
    )
    (comp (ref "R72")
      (value "4.7k")
      (footprint "RES-SM-0805")
      (description "Resistor")
      (fields
        (field (name "MANUFACTURER") "Generic Components")
        (field (name "PUBLISHER") "Altium Hobart Technology Centre")
      )
      (libsource (lib "Main_Board") (part "Res-SMD"))
    )
    (comp (ref "R73")
      (value "120")
      (footprint "RES-SM-0805")
      (description "Resistor")
      (fields
        (field (name "MANUFACTURER") "Generic Components")
        (field (name "PUBLISHER") "Altium Hobart Technology Centre")
      )
      (libsource (lib "Main_Board") (part "Res-SMD"))
    )
    (comp (ref "R74")
      (value "4.7k")
      (footprint "RES-SM-0805")
      (description "Resistor")
      (fields
        (field (name "MANUFACTURER") "Generic Components")
        (field (name "PUBLISHER") "Altium Hobart Technology Centre")
      )
      (libsource (lib "Main_Board") (part "Res-SMD"))
    )
    (comp (ref "R75")
      (value "1k")
      (footprint "RES-SM-0805")
      (description "Resistor")
      (fields
        (field (name "MANUFACTURER") "Generic Components")
        (field (name "PUBLISHER") "Altium Hobart Technology Centre")
      )
      (libsource (lib "Main_Board") (part "Res-SMD"))
    )
    (comp (ref "R76")
      (value "1k")
      (footprint "RES-SM-0805")
      (description "Resistor")
      (fields
        (field (name "MANUFACTURER") "Generic Components")
        (field (name "PUBLISHER") "Altium Hobart Technology Centre")
      )
      (libsource (lib "Main_Board") (part "Res-SMD"))
    )
    (comp (ref "R77")
      (value "4.7k")
      (footprint "RES-SM-0805")
      (description "Resistor")
      (fields
        (field (name "MANUFACTURER") "Generic Components")
        (field (name "PUBLISHER") "Altium Hobart Technology Centre")
      )
      (libsource (lib "Main_Board") (part "Res-SMD"))
    )
    (comp (ref "R78")
      (value "10k")
      (footprint "RES-SM-0805")
      (description "Resistor")
      (fields
        (field (name "MANUFACTURER") "Generic Components")
        (field (name "PUBLISHER") "Altium Hobart Technology Centre")
      )
      (libsource (lib "Main_Board") (part "Res-SMD"))
    )
    (comp (ref "R79")
      (value "4.7k")
      (footprint "RES-SM-0805")
      (description "Resistor")
      (fields
        (field (name "MANUFACTURER") "Generic Components")
        (field (name "PUBLISHER") "Altium Hobart Technology Centre")
      )
      (libsource (lib "Main_Board") (part "Res-SMD"))
    )
    (comp (ref "R80")
      (value "120")
      (footprint "RES-SM-0805")
      (description "Resistor")
      (fields
        (field (name "MANUFACTURER") "Generic Components")
        (field (name "PUBLISHER") "Altium Hobart Technology Centre")
      )
      (libsource (lib "Main_Board") (part "Res-SMD"))
    )
    (comp (ref "R81")
      (value "1k")
      (footprint "RES-SM-0805")
      (description "Resistor")
      (fields
        (field (name "MANUFACTURER") "Generic Components")
        (field (name "PUBLISHER") "Altium Hobart Technology Centre")
      )
      (libsource (lib "Main_Board") (part "Res-SMD"))
    )
    (comp (ref "R82")
      (value "4.7k")
      (footprint "RES-SM-0805")
      (description "Resistor")
      (fields
        (field (name "MANUFACTURER") "Generic Components")
        (field (name "PUBLISHER") "Altium Hobart Technology Centre")
      )
      (libsource (lib "Main_Board") (part "Res-SMD"))
    )
    (comp (ref "R83")
      (value "1k")
      (footprint "RES-SM-0805")
      (description "Resistor")
      (fields
        (field (name "MANUFACTURER") "Generic Components")
        (field (name "PUBLISHER") "Altium Hobart Technology Centre")
      )
      (libsource (lib "Main_Board") (part "Res-SMD"))
    )
    (comp (ref "R84")
      (value "4.7k")
      (footprint "RES-SM-0805")
      (description "Resistor")
      (fields
        (field (name "MANUFACTURER") "Generic Components")
        (field (name "PUBLISHER") "Altium Hobart Technology Centre")
      )
      (libsource (lib "Main_Board") (part "Res-SMD"))
    )
    (comp (ref "R85")
      (value "10k")
      (footprint "RES-SM-0805")
      (description "Resistor")
      (fields
        (field (name "MANUFACTURER") "Generic Components")
        (field (name "PUBLISHER") "Altium Hobart Technology Centre")
      )
      (libsource (lib "Main_Board") (part "Res-SMD"))
    )
    (comp (ref "R86")
      (value "1k")
      (footprint "RES-SM-0805")
      (description "Resistor")
      (fields
        (field (name "MANUFACTURER") "Generic Components")
        (field (name "PUBLISHER") "Altium Hobart Technology Centre")
      )
      (libsource (lib "Main_Board") (part "Res-SMD"))
    )
    (comp (ref "R87")
      (value "4.7k")
      (footprint "RES-SM-0805")
      (description "Resistor")
      (fields
        (field (name "MANUFACTURER") "Generic Components")
        (field (name "PUBLISHER") "Altium Hobart Technology Centre")
      )
      (libsource (lib "Main_Board") (part "Res-SMD"))
    )
    (comp (ref "R88")
      (value "1k")
      (footprint "RES-SM-0805")
      (description "Resistor")
      (fields
        (field (name "MANUFACTURER") "Generic Components")
        (field (name "PUBLISHER") "Altium Hobart Technology Centre")
      )
      (libsource (lib "Main_Board") (part "Res-SMD"))
    )
    (comp (ref "R89")
      (value "4.7k")
      (footprint "RES-SM-0805")
      (description "Resistor")
      (fields
        (field (name "MANUFACTURER") "Generic Components")
        (field (name "PUBLISHER") "Altium Hobart Technology Centre")
      )
      (libsource (lib "Main_Board") (part "Res-SMD"))
    )
    (comp (ref "R90")
      (value "120")
      (footprint "RES-SM-0805")
      (description "Resistor")
      (fields
        (field (name "MANUFACTURER") "Generic Components")
        (field (name "PUBLISHER") "Altium Hobart Technology Centre")
      )
      (libsource (lib "Main_Board") (part "Res-SMD"))
    )
    (comp (ref "R91")
      (value "1k")
      (footprint "RES-SM-0805")
      (description "Resistor")
      (fields
        (field (name "MANUFACTURER") "Generic Components")
        (field (name "PUBLISHER") "Altium Hobart Technology Centre")
      )
      (libsource (lib "Main_Board") (part "Res-SMD"))
    )
    (comp (ref "R92")
      (value "4.7k")
      (footprint "RES-SM-0805")
      (description "Resistor")
      (fields
        (field (name "MANUFACTURER") "Generic Components")
        (field (name "PUBLISHER") "Altium Hobart Technology Centre")
      )
      (libsource (lib "Main_Board") (part "Res-SMD"))
    )
    (comp (ref "R93")
      (value "1k")
      (footprint "RES-SM-0805")
      (description "Resistor")
      (fields
        (field (name "MANUFACTURER") "Generic Components")
        (field (name "PUBLISHER") "Altium Hobart Technology Centre")
      )
      (libsource (lib "Main_Board") (part "Res-SMD"))
    )
    (comp (ref "R94")
      (value "4.7k")
      (footprint "RES-SM-0805")
      (description "Resistor")
      (fields
        (field (name "MANUFACTURER") "Generic Components")
        (field (name "PUBLISHER") "Altium Hobart Technology Centre")
      )
      (libsource (lib "Main_Board") (part "Res-SMD"))
    )
    (comp (ref "RN1")
      (value "10K")
      (footprint "RN8")
      (description "Resistor 8 (Thanh)")
      (libsource (lib "Main_Board") (part "RN8"))
    )
    (comp (ref "RN2")
      (value "10K")
      (footprint "RN8")
      (description "Resistor 8 (Thanh)")
      (libsource (lib "Main_Board") (part "RN8"))
    )
    (comp (ref "RN3")
      (value "10K")
      (footprint "RN8")
      (description "Resistor 8 (Thanh)")
      (libsource (lib "") (part "RN8_1"))
    )
    (comp (ref "RN4")
      (value "10K")
      (footprint "RN8")
      (description "Resistor 8 (Thanh)")
      (libsource (lib "") (part "RN8_1"))
    )
    (comp (ref "RN5")
      (value "10K")
      (footprint "RN8")
      (description "Resistor 8 (Thanh)")
      (libsource (lib "Main_Board") (part "RN8"))
    )
    (comp (ref "S1")
      (value "Reset")
      (footprint "SW2")
      (description "Switch button 2 pin")
      (libsource (lib "Main_Board") (part "SW - 2Pin"))
    )
    (comp (ref "U1")
      (value "STM_CPLD_Board")
      (footprint "STM_CPLD_Board")
      (description "STM32f4 and Max2 570 on one board")
      (libsource (lib "Main_Board") (part "STM_CPLD_Board"))
    )
    (comp (ref "U2")
      (value "LM2596 - 5V")
      (footprint "TO263")
      (description "SIMPLE SWITCHER® Power Converter 150-kHz - 3A Step-Down Voltage Regulator")
      (libsource (lib "Main_Board") (part "LM2596"))
    )
    (comp (ref "U3")
      (value "74HCT245")
      (footprint "soic20")
      (description "Octal bus tranceiver")
      (libsource (lib "Main_Board") (part "74HC245"))
    )
    (comp (ref "U4")
      (value "74HC14")
      (footprint "SOIC14")
      (description "Hex Inverters With SCHMITT-TRIGGER Inputs")
      (libsource (lib "Main_Board") (part "74HC14"))
    )
    (comp (ref "U5")
      (value "74HC14")
      (footprint "SOIC14")
      (description "Hex Inverters With SCHMITT-TRIGGER Inputs")
      (libsource (lib "Main_Board") (part "74HC14"))
    )
    (comp (ref "U6")
      (value "74HCT245")
      (footprint "soic20")
      (description "Octal bus tranceiver")
      (libsource (lib "Main_Board") (part "74HC245"))
    )
    (comp (ref "U7")
      (value "74LCV4245")
      (footprint "SOIC24 - wide")
      (description "Octal dual supply translating transceiver; 3-state")
      (libsource (lib "Main_Board") (part "74LCV4245"))
    )
    (comp (ref "U8")
      (value "74LCV4245")
      (footprint "SOIC24 - wide")
      (description "Octal dual supply translating transceiver; 3-state")
      (libsource (lib "Main_Board") (part "74LCV4245"))
    )
    (comp (ref "U9")
      (value "74LCV4245")
      (footprint "SOIC24 - wide")
      (description "Octal dual supply translating transceiver; 3-state")
      (libsource (lib "Main_Board") (part "74LCV4245"))
    )
    (comp (ref "U10")
      (value "74HCT245")
      (footprint "soic20")
      (description "Octal bus tranceiver")
      (libsource (lib "Main_Board") (part "74HC245"))
    )
    (comp (ref "U11")
      (value "74LCV4245")
      (footprint "SOIC24 - wide")
      (description "Octal dual supply translating transceiver; 3-state")
      (libsource (lib "Main_Board") (part "74LCV4245"))
    )
    (comp (ref "VR1")
      (value "2K")
      (footprint "VR1")
      (description "Var Resistor")
      (libsource (lib "Main_Board") (part "VR1"))
    )
    (comp (ref "VR2")
      (value "2K")
      (footprint "VR1")
      (description "Var Resistor")
      (libsource (lib "Main_Board") (part "VR1"))
    )
  )
  (nets
    (net (code "1") (name "/485_RX") (class "Default")
      (node (ref "IC9") (pin "3") (pinfunction "RXD_3") (pintype "passive"))
      (node (ref "U1") (pin "46") (pinfunction "46_46") (pintype "passive"))
    )
    (net (code "2") (name "/485_TX") (class "Default")
      (node (ref "IC9") (pin "2") (pinfunction "TXD_2") (pintype "passive"))
      (node (ref "U1") (pin "86") (pinfunction "86_86") (pintype "passive"))
    )
    (net (code "3") (name "/ADC0") (class "Default")
      (node (ref "D22") (pin "2") (pinfunction "K_2") (pintype "passive"))
      (node (ref "IC11") (pin "1") (pinfunction "OUT_1") (pintype "output"))
      (node (ref "IC11") (pin "2") (pinfunction "IN-_2") (pintype "input"))
      (node (ref "U1") (pin "34") (pinfunction "34_34") (pintype "passive"))
    )
    (net (code "4") (name "/ADC1") (class "Default")
      (node (ref "D23") (pin "2") (pinfunction "K_2") (pintype "passive"))
      (node (ref "IC11") (pin "6") (pinfunction "IN-_6") (pintype "input"))
      (node (ref "IC11") (pin "7") (pinfunction "OUT_7") (pintype "output"))
      (node (ref "U1") (pin "33") (pinfunction "33_33") (pintype "passive"))
    )
    (net (code "5") (name "/ADC_0") (class "Default")
      (node (ref "HD32") (pin "3") (pinfunction "3_3") (pintype "passive"))
      (node (ref "VR1") (pin "1") (pinfunction "1_1") (pintype "passive"))
    )
    (net (code "6") (name "/ADC_1") (class "Default")
      (node (ref "HD32") (pin "2") (pinfunction "2_2") (pintype "passive"))
      (node (ref "VR2") (pin "1") (pinfunction "1_1") (pintype "passive"))
    )
    (net (code "9") (name "/BL_RX") (class "Default")
      (node (ref "H1") (pin "3") (pinfunction "3_3") (pintype "passive"))
      (node (ref "U1") (pin "51") (pinfunction "51_51") (pintype "passive"))
    )
    (net (code "10") (name "/BL_TX") (class "Default")
      (node (ref "H1") (pin "2") (pinfunction "2_2") (pintype "passive"))
      (node (ref "U1") (pin "81") (pinfunction "81_81") (pintype "passive"))
    )
    (net (code "11") (name "/DIR_0") (class "Default")
      (node (ref "RN1") (pin "7") (pinfunction "7_7") (pintype "passive"))
      (node (ref "U1") (pin "29") (pinfunction "29_29") (pintype "passive"))
      (node (ref "U3") (pin "4") (pinfunction "A2_4") (pintype "passive"))
    )
    (net (code "12") (name "/DIR_1") (class "Default")
      (node (ref "RN1") (pin "9") (pinfunction "9_9") (pintype "passive"))
      (node (ref "U1") (pin "28") (pinfunction "28_28") (pintype "passive"))
      (node (ref "U3") (pin "2") (pinfunction "A0_2") (pintype "passive"))
    )
    (net (code "13") (name "/DIR_2") (class "Default")
      (node (ref "RN5") (pin "3") (pinfunction "3_3") (pintype "passive"))
      (node (ref "U1") (pin "27") (pinfunction "27_27") (pintype "passive"))
      (node (ref "U10") (pin "8") (pinfunction "A6_8") (pintype "passive"))
    )
    (net (code "14") (name "/DIR_3") (class "Default")
      (node (ref "RN5") (pin "5") (pinfunction "5_5") (pintype "passive"))
      (node (ref "U1") (pin "26") (pinfunction "26_26") (pintype "passive"))
      (node (ref "U10") (pin "6") (pinfunction "A4_6") (pintype "passive"))
    )
    (net (code "15") (name "/DIR_4") (class "Default")
      (node (ref "RN5") (pin "7") (pinfunction "7_7") (pintype "passive"))
      (node (ref "U1") (pin "25") (pinfunction "25_25") (pintype "passive"))
      (node (ref "U10") (pin "4") (pinfunction "A2_4") (pintype "passive"))
    )
    (net (code "16") (name "/DIR_5") (class "Default")
      (node (ref "RN5") (pin "9") (pinfunction "9_9") (pintype "passive"))
      (node (ref "U1") (pin "24") (pinfunction "24_24") (pintype "passive"))
      (node (ref "U10") (pin "2") (pinfunction "A0_2") (pintype "passive"))
    )
    (net (code "17") (name "/EEP_SCL") (class "Default")
      (node (ref "IC7") (pin "6") (pinfunction "SCL_6") (pintype "passive"))
      (node (ref "R38") (pin "1") (pinfunction "1_1") (pintype "passive"))
      (node (ref "U1") (pin "4") (pinfunction "4_4") (pintype "passive"))
    )
    (net (code "18") (name "/EEP_SDA") (class "Default")
      (node (ref "IC7") (pin "5") (pinfunction "SDA_5") (pintype "passive"))
      (node (ref "R39") (pin "2") (pinfunction "2_2") (pintype "passive"))
      (node (ref "U1") (pin "41") (pinfunction "41_41") (pintype "passive"))
    )
    (net (code "31") (name "/ENC_A0") (class "Default")
      (node (ref "U1") (pin "72") (pinfunction "72_72") (pintype "passive"))
      (node (ref "U7") (pin "21") (pinfunction "B0_21") (pintype "passive"))
    )
    (net (code "32") (name "/ENC_A1") (class "Default")
      (node (ref "U1") (pin "73") (pinfunction "73_73") (pintype "passive"))
      (node (ref "U7") (pin "18") (pinfunction "B3_18") (pintype "passive"))
    )
    (net (code "33") (name "/ENC_A2") (class "Default")
      (node (ref "U1") (pin "74") (pinfunction "74_74") (pintype "passive"))
      (node (ref "U7") (pin "15") (pinfunction "B6_15") (pintype "passive"))
    )
    (net (code "34") (name "/ENC_A3") (class "Default")
      (node (ref "U1") (pin "69") (pinfunction "69_69") (pintype "passive"))
      (node (ref "U11") (pin "21") (pinfunction "B0_21") (pintype "passive"))
    )
    (net (code "35") (name "/ENC_A4") (class "Default")
      (node (ref "U1") (pin "70") (pinfunction "70_70") (pintype "passive"))
      (node (ref "U11") (pin "18") (pinfunction "B3_18") (pintype "passive"))
    )
    (net (code "36") (name "/ENC_A5") (class "Default")
      (node (ref "U1") (pin "71") (pinfunction "71_71") (pintype "passive"))
      (node (ref "U11") (pin "15") (pinfunction "B6_15") (pintype "passive"))
    )
    (net (code "37") (name "/ENC_B0") (class "Default")
      (node (ref "U1") (pin "61") (pinfunction "61_61") (pintype "passive"))
      (node (ref "U7") (pin "20") (pinfunction "B1_20") (pintype "passive"))
    )
    (net (code "38") (name "/ENC_B1") (class "Default")
      (node (ref "U1") (pin "60") (pinfunction "60_60") (pintype "passive"))
      (node (ref "U7") (pin "17") (pinfunction "B4_17") (pintype "passive"))
    )
    (net (code "39") (name "/ENC_B2") (class "Default")
      (node (ref "U1") (pin "59") (pinfunction "59_59") (pintype "passive"))
      (node (ref "U7") (pin "14") (pinfunction "B7_14") (pintype "passive"))
    )
    (net (code "40") (name "/ENC_B3") (class "Default")
      (node (ref "U1") (pin "64") (pinfunction "64_64") (pintype "passive"))
      (node (ref "U11") (pin "20") (pinfunction "B1_20") (pintype "passive"))
    )
    (net (code "41") (name "/ENC_B4") (class "Default")
      (node (ref "U1") (pin "63") (pinfunction "63_63") (pintype "passive"))
      (node (ref "U11") (pin "17") (pinfunction "B4_17") (pintype "passive"))
    )
    (net (code "42") (name "/ENC_B5") (class "Default")
      (node (ref "U1") (pin "62") (pinfunction "62_62") (pintype "passive"))
      (node (ref "U11") (pin "14") (pinfunction "B7_14") (pintype "passive"))
    )
    (net (code "43") (name "/HOME") (class "Default")
      (node (ref "U1") (pin "36") (pinfunction "36_36") (pintype "passive"))
      (node (ref "U9") (pin "16") (pinfunction "B5_16") (pintype "passive"))
    )
    (net (code "44") (name "/HOME 1") (class "Default")
      (node (ref "U1") (pin "54") (pinfunction "54_54") (pintype "passive"))
      (node (ref "U8") (pin "18") (pinfunction "B3_18") (pintype "passive"))
    )
    (net (code "45") (name "/HOME 2") (class "Default")
      (node (ref "U1") (pin "79") (pinfunction "79_79") (pintype "passive"))
      (node (ref "U8") (pin "19") (pinfunction "B2_19") (pintype "passive"))
    )
    (net (code "46") (name "/HOME 3") (class "Default")
      (node (ref "U1") (pin "53") (pinfunction "53_53") (pintype "passive"))
      (node (ref "U8") (pin "20") (pinfunction "B1_20") (pintype "passive"))
    )
    (net (code "47") (name "/HOME 4") (class "Default")
      (node (ref "U1") (pin "80") (pinfunction "80_80") (pintype "passive"))
      (node (ref "U8") (pin "21") (pinfunction "B0_21") (pintype "passive"))
    )
    (net (code "48") (name "/HOME 5") (class "Default")
      (node (ref "U1") (pin "37") (pinfunction "37_37") (pintype "passive"))
      (node (ref "U9") (pin "14") (pinfunction "B7_14") (pintype "passive"))
    )
    (net (code "49") (name "/HOME 6") (class "Default")
      (node (ref "U1") (pin "8") (pinfunction "8_8") (pintype "passive"))
      (node (ref "U9") (pin "15") (pinfunction "B6_15") (pintype "passive"))
    )
    (net (code "50") (name "/H_DIR_0") (class "Default")
      (node (ref "HD4") (pin "3") (pinfunction "3_3") (pintype "passive"))
      (node (ref "OP3") (pin "6") (pinfunction "Vo2_6") (pintype "passive"))
      (node (ref "R7") (pin "2") (pinfunction "2_2") (pintype "passive"))
    )
    (net (code "51") (name "/H_DIR_1") (class "Default")
      (node (ref "HD11") (pin "3") (pinfunction "3_3") (pintype "passive"))
      (node (ref "OP8") (pin "6") (pinfunction "Vo2_6") (pintype "passive"))
      (node (ref "R22") (pin "2") (pinfunction "2_2") (pintype "passive"))
    )
    (net (code "52") (name "/H_DIR_2") (class "Default")
      (node (ref "HD18") (pin "3") (pinfunction "3_3") (pintype "passive"))
      (node (ref "OP13") (pin "6") (pinfunction "Vo2_6") (pintype "passive"))
      (node (ref "R36") (pin "2") (pinfunction "2_2") (pintype "passive"))
    )
    (net (code "53") (name "/H_DIR_3") (class "Default")
      (node (ref "HD24") (pin "3") (pinfunction "3_3") (pintype "passive"))
      (node (ref "OP18") (pin "6") (pinfunction "Vo2_6") (pintype "passive"))
      (node (ref "R49") (pin "2") (pinfunction "2_2") (pintype "passive"))
    )
    (net (code "54") (name "/H_DIR_4") (class "Default")
      (node (ref "HD30") (pin "3") (pinfunction "3_3") (pintype "passive"))
      (node (ref "OP21") (pin "6") (pinfunction "Vo2_6") (pintype "passive"))
      (node (ref "R57") (pin "2") (pinfunction "2_2") (pintype "passive"))
    )
    (net (code "55") (name "/H_DIR_5") (class "Default")
      (node (ref "HD34") (pin "3") (pinfunction "3_3") (pintype "passive"))
      (node (ref "OP22") (pin "6") (pinfunction "Vo2_6") (pintype "passive"))
      (node (ref "R65") (pin "2") (pinfunction "2_2") (pintype "passive"))
    )
    (net (code "56") (name "/H_ENC+_A0") (class "Default")
      (node (ref "C11") (pin "1") (pinfunction "1_1") (pintype "passive"))
      (node (ref "HD5") (pin "1") (pinfunction "1_1") (pintype "passive"))
      (node (ref "IC1") (pin "6") (pinfunction "A_6") (pintype "passive"))
      (node (ref "R8") (pin "1") (pinfunction "1_1") (pintype "passive"))
    )
    (net (code "57") (name "/H_ENC+_A1") (class "Default")
      (node (ref "C32") (pin "1") (pinfunction "1_1") (pintype "passive"))
      (node (ref "HD12") (pin "1") (pinfunction "1_1") (pintype "passive"))
      (node (ref "IC4") (pin "6") (pinfunction "A_6") (pintype "passive"))
      (node (ref "R25") (pin "1") (pinfunction "1_1") (pintype "passive"))
    )
    (net (code "58") (name "/H_ENC+_A2") (class "Default")
      (node (ref "C48") (pin "1") (pinfunction "1_1") (pintype "passive"))
      (node (ref "HD21") (pin "1") (pinfunction "1_1") (pintype "passive"))
      (node (ref "IC6") (pin "6") (pinfunction "A_6") (pintype "passive"))
      (node (ref "R40") (pin "1") (pinfunction "1_1") (pintype "passive"))
    )
    (net (code "59") (name "/H_ENC+_A3") (class "Default")
      (node (ref "C64") (pin "1") (pinfunction "1_1") (pintype "passive"))
      (node (ref "HD29") (pin "1") (pinfunction "1_1") (pintype "passive"))
      (node (ref "IC10") (pin "6") (pinfunction "A_6") (pintype "passive"))
      (node (ref "R52") (pin "1") (pinfunction "1_1") (pintype "passive"))
    )
    (net (code "60") (name "/H_ENC+_A4") (class "Default")
      (node (ref "C89") (pin "1") (pinfunction "1_1") (pintype "passive"))
      (node (ref "HD33") (pin "1") (pinfunction "1_1") (pintype "passive"))
      (node (ref "IC13") (pin "6") (pinfunction "A_6") (pintype "passive"))
      (node (ref "R62") (pin "1") (pinfunction "1_1") (pintype "passive"))
    )
    (net (code "61") (name "/H_ENC+_A5") (class "Default")
      (node (ref "C97") (pin "1") (pinfunction "1_1") (pintype "passive"))
      (node (ref "HD39") (pin "1") (pinfunction "1_1") (pintype "passive"))
      (node (ref "IC15") (pin "6") (pinfunction "A_6") (pintype "passive"))
      (node (ref "R80") (pin "1") (pinfunction "1_1") (pintype "passive"))
    )
    (net (code "62") (name "/H_ENC+_B0") (class "Default")
      (node (ref "C21") (pin "1") (pinfunction "1_1") (pintype "passive"))
      (node (ref "HD8") (pin "1") (pinfunction "1_1") (pintype "passive"))
      (node (ref "IC3") (pin "6") (pinfunction "A_6") (pintype "passive"))
      (node (ref "R17") (pin "1") (pinfunction "1_1") (pintype "passive"))
    )
    (net (code "63") (name "/H_ENC+_B1") (class "Default")
      (node (ref "C40") (pin "1") (pinfunction "1_1") (pintype "passive"))
      (node (ref "HD17") (pin "1") (pinfunction "1_1") (pintype "passive"))
      (node (ref "IC5") (pin "6") (pinfunction "A_6") (pintype "passive"))
      (node (ref "R31") (pin "1") (pinfunction "1_1") (pintype "passive"))
    )
    (net (code "64") (name "/H_ENC+_B2") (class "Default")
      (node (ref "C55") (pin "1") (pinfunction "1_1") (pintype "passive"))
      (node (ref "HD25") (pin "1") (pinfunction "1_1") (pintype "passive"))
      (node (ref "IC8") (pin "6") (pinfunction "A_6") (pintype "passive"))
      (node (ref "R50") (pin "1") (pinfunction "1_1") (pintype "passive"))
    )
    (net (code "65") (name "/H_ENC+_B3") (class "Default")
      (node (ref "C78") (pin "1") (pinfunction "1_1") (pintype "passive"))
      (node (ref "HD31") (pin "1") (pinfunction "1_1") (pintype "passive"))
      (node (ref "IC12") (pin "6") (pinfunction "A_6") (pintype "passive"))
      (node (ref "R58") (pin "1") (pinfunction "1_1") (pintype "passive"))
    )
    (net (code "66") (name "/H_ENC+_B4") (class "Default")
      (node (ref "C93") (pin "1") (pinfunction "1_1") (pintype "passive"))
      (node (ref "HD36") (pin "1") (pinfunction "1_1") (pintype "passive"))
      (node (ref "IC14") (pin "6") (pinfunction "A_6") (pintype "passive"))
      (node (ref "R73") (pin "1") (pinfunction "1_1") (pintype "passive"))
    )
    (net (code "67") (name "/H_ENC+_B5") (class "Default")
      (node (ref "C101") (pin "1") (pinfunction "1_1") (pintype "passive"))
      (node (ref "HD42") (pin "1") (pinfunction "1_1") (pintype "passive"))
      (node (ref "IC16") (pin "6") (pinfunction "A_6") (pintype "passive"))
      (node (ref "R90") (pin "1") (pinfunction "1_1") (pintype "passive"))
    )
    (net (code "68") (name "/H_ENC-_A0") (class "Default")
      (node (ref "C4") (pin "2") (pinfunction "2_2") (pintype "passive"))
      (node (ref "HD5") (pin "2") (pinfunction "2_2") (pintype "passive"))
      (node (ref "IC1") (pin "7") (pinfunction "B_7") (pintype "passive"))
      (node (ref "R8") (pin "2") (pinfunction "2_2") (pintype "passive"))
    )
    (net (code "69") (name "/H_ENC-_A1") (class "Default")
      (node (ref "C26") (pin "2") (pinfunction "2_2") (pintype "passive"))
      (node (ref "HD12") (pin "2") (pinfunction "2_2") (pintype "passive"))
      (node (ref "IC4") (pin "7") (pinfunction "B_7") (pintype "passive"))
      (node (ref "R25") (pin "2") (pinfunction "2_2") (pintype "passive"))
    )
    (net (code "70") (name "/H_ENC-_A2") (class "Default")
      (node (ref "C44") (pin "2") (pinfunction "2_2") (pintype "passive"))
      (node (ref "HD21") (pin "2") (pinfunction "2_2") (pintype "passive"))
      (node (ref "IC6") (pin "7") (pinfunction "B_7") (pintype "passive"))
      (node (ref "R40") (pin "2") (pinfunction "2_2") (pintype "passive"))
    )
    (net (code "71") (name "/H_ENC-_A3") (class "Default")
      (node (ref "C61") (pin "2") (pinfunction "2_2") (pintype "passive"))
      (node (ref "HD29") (pin "2") (pinfunction "2_2") (pintype "passive"))
      (node (ref "IC10") (pin "7") (pinfunction "B_7") (pintype "passive"))
      (node (ref "R52") (pin "2") (pinfunction "2_2") (pintype "passive"))
    )
    (net (code "72") (name "/H_ENC-_A4") (class "Default")
      (node (ref "C85") (pin "2") (pinfunction "2_2") (pintype "passive"))
      (node (ref "HD33") (pin "2") (pinfunction "2_2") (pintype "passive"))
      (node (ref "IC13") (pin "7") (pinfunction "B_7") (pintype "passive"))
      (node (ref "R62") (pin "2") (pinfunction "2_2") (pintype "passive"))
    )
    (net (code "73") (name "/H_ENC-_A5") (class "Default")
      (node (ref "C94") (pin "2") (pinfunction "2_2") (pintype "passive"))
      (node (ref "HD39") (pin "2") (pinfunction "2_2") (pintype "passive"))
      (node (ref "IC15") (pin "7") (pinfunction "B_7") (pintype "passive"))
      (node (ref "R80") (pin "2") (pinfunction "2_2") (pintype "passive"))
    )
    (net (code "74") (name "/H_ENC-_B0") (class "Default")
      (node (ref "C14") (pin "2") (pinfunction "2_2") (pintype "passive"))
      (node (ref "HD8") (pin "2") (pinfunction "2_2") (pintype "passive"))
      (node (ref "IC3") (pin "7") (pinfunction "B_7") (pintype "passive"))
      (node (ref "R17") (pin "2") (pinfunction "2_2") (pintype "passive"))
    )
    (net (code "75") (name "/H_ENC-_B1") (class "Default")
      (node (ref "C37") (pin "2") (pinfunction "2_2") (pintype "passive"))
      (node (ref "HD17") (pin "2") (pinfunction "2_2") (pintype "passive"))
      (node (ref "IC5") (pin "7") (pinfunction "B_7") (pintype "passive"))
      (node (ref "R31") (pin "2") (pinfunction "2_2") (pintype "passive"))
    )
    (net (code "76") (name "/H_ENC-_B2") (class "Default")
      (node (ref "C52") (pin "2") (pinfunction "2_2") (pintype "passive"))
      (node (ref "HD25") (pin "2") (pinfunction "2_2") (pintype "passive"))
      (node (ref "IC8") (pin "7") (pinfunction "B_7") (pintype "passive"))
      (node (ref "R50") (pin "2") (pinfunction "2_2") (pintype "passive"))
    )
    (net (code "77") (name "/H_ENC-_B3") (class "Default")
      (node (ref "C73") (pin "2") (pinfunction "2_2") (pintype "passive"))
      (node (ref "HD31") (pin "2") (pinfunction "2_2") (pintype "passive"))
      (node (ref "IC12") (pin "7") (pinfunction "B_7") (pintype "passive"))
      (node (ref "R58") (pin "2") (pinfunction "2_2") (pintype "passive"))
    )
    (net (code "78") (name "/H_ENC-_B4") (class "Default")
      (node (ref "C90") (pin "2") (pinfunction "2_2") (pintype "passive"))
      (node (ref "HD36") (pin "2") (pinfunction "2_2") (pintype "passive"))
      (node (ref "IC14") (pin "7") (pinfunction "B_7") (pintype "passive"))
      (node (ref "R73") (pin "2") (pinfunction "2_2") (pintype "passive"))
    )
    (net (code "79") (name "/H_ENC-_B5") (class "Default")
      (node (ref "C98") (pin "2") (pinfunction "2_2") (pintype "passive"))
      (node (ref "HD42") (pin "2") (pinfunction "2_2") (pintype "passive"))
      (node (ref "IC16") (pin "7") (pinfunction "B_7") (pintype "passive"))
      (node (ref "R90") (pin "2") (pinfunction "2_2") (pintype "passive"))
    )
    (net (code "80") (name "/H_IN+_0") (class "Default")
      (node (ref "HD2") (pin "2") (pinfunction "2_2") (pintype "passive"))
      (node (ref "R1") (pin "2") (pinfunction "2_2") (pintype "passive"))
    )
    (net (code "81") (name "/H_IN+_1") (class "Default")
      (node (ref "HD7") (pin "2") (pinfunction "2_2") (pintype "passive"))
      (node (ref "R9") (pin "2") (pinfunction "2_2") (pintype "passive"))
    )
    (net (code "82") (name "/H_IN+_2") (class "Default")
      (node (ref "HD9") (pin "2") (pinfunction "2_2") (pintype "passive"))
      (node (ref "R15") (pin "2") (pinfunction "2_2") (pintype "passive"))
    )
    (net (code "83") (name "/H_IN+_3") (class "Default")
      (node (ref "HD13") (pin "2") (pinfunction "2_2") (pintype "passive"))
      (node (ref "R23") (pin "2") (pinfunction "2_2") (pintype "passive"))
    )
    (net (code "84") (name "/H_IN+_4") (class "Default")
      (node (ref "HD15") (pin "2") (pinfunction "2_2") (pintype "passive"))
      (node (ref "R27") (pin "2") (pinfunction "2_2") (pintype "passive"))
    )
    (net (code "85") (name "/H_IN+_5") (class "Default")
      (node (ref "HD19") (pin "2") (pinfunction "2_2") (pintype "passive"))
      (node (ref "R33") (pin "2") (pinfunction "2_2") (pintype "passive"))
    )
    (net (code "86") (name "/H_IN+_6") (class "Default")
      (node (ref "HD22") (pin "2") (pinfunction "2_2") (pintype "passive"))
      (node (ref "R41") (pin "2") (pinfunction "2_2") (pintype "passive"))
    )
    (net (code "87") (name "/H_IN+_7") (class "Default")
      (node (ref "HD26") (pin "2") (pinfunction "2_2") (pintype "passive"))
      (node (ref "R47") (pin "2") (pinfunction "2_2") (pintype "passive"))
    )
    (net (code "88") (name "/H_IN+_8") (class "Default")
      (node (ref "HD1") (pin "2") (pinfunction "2_2") (pintype "passive"))
      (node (ref "R2") (pin "2") (pinfunction "2_2") (pintype "passive"))
    )
    (net (code "89") (name "/H_IN+_9") (class "Default")
      (node (ref "HD6") (pin "2") (pinfunction "2_2") (pintype "passive"))
      (node (ref "R10") (pin "2") (pinfunction "2_2") (pintype "passive"))
    )
    (net (code "90") (name "/H_IN+_10") (class "Default")
      (node (ref "HD10") (pin "2") (pinfunction "2_2") (pintype "passive"))
      (node (ref "R16") (pin "2") (pinfunction "2_2") (pintype "passive"))
    )
    (net (code "91") (name "/H_IN+_11") (class "Default")
      (node (ref "HD14") (pin "2") (pinfunction "2_2") (pintype "passive"))
      (node (ref "R24") (pin "2") (pinfunction "2_2") (pintype "passive"))
    )
    (net (code "92") (name "/H_IN+_12") (class "Default")
      (node (ref "HD16") (pin "2") (pinfunction "2_2") (pintype "passive"))
      (node (ref "R28") (pin "2") (pinfunction "2_2") (pintype "passive"))
    )
    (net (code "93") (name "/H_IN+_13") (class "Default")
      (node (ref "HD20") (pin "2") (pinfunction "2_2") (pintype "passive"))
      (node (ref "R35") (pin "2") (pinfunction "2_2") (pintype "passive"))
    )
    (net (code "94") (name "/H_IN+_14") (class "Default")
      (node (ref "HD23") (pin "2") (pinfunction "2_2") (pintype "passive"))
      (node (ref "R42") (pin "2") (pinfunction "2_2") (pintype "passive"))
    )
    (net (code "95") (name "/H_IN+_15") (class "Default")
      (node (ref "HD27") (pin "2") (pinfunction "2_2") (pintype "passive"))
      (node (ref "R48") (pin "2") (pinfunction "2_2") (pintype "passive"))
    )
    (net (code "96") (name "/H_IN-_0") (class "Default")
      (node (ref "D2") (pin "1") (pinfunction "A_1") (pintype "passive"))
      (node (ref "HD2") (pin "1") (pinfunction "1_1") (pintype "passive"))
      (node (ref "OP1") (pin "2") (pinfunction "C_2") (pintype "passive"))
    )
    (net (code "97") (name "/H_IN-_1") (class "Default")
      (node (ref "D5") (pin "1") (pinfunction "A_1") (pintype "passive"))
      (node (ref "HD7") (pin "1") (pinfunction "1_1") (pintype "passive"))
      (node (ref "OP4") (pin "2") (pinfunction "C_2") (pintype "passive"))
    )
    (net (code "98") (name "/H_IN-_2") (class "Default")
      (node (ref "D10") (pin "1") (pinfunction "A_1") (pintype "passive"))
      (node (ref "HD9") (pin "1") (pinfunction "1_1") (pintype "passive"))
      (node (ref "OP6") (pin "2") (pinfunction "C_2") (pintype "passive"))
    )
    (net (code "99") (name "/H_IN-_3") (class "Default")
      (node (ref "D12") (pin "1") (pinfunction "A_1") (pintype "passive"))
      (node (ref "HD13") (pin "1") (pinfunction "1_1") (pintype "passive"))
      (node (ref "OP9") (pin "2") (pinfunction "C_2") (pintype "passive"))
    )
    (net (code "100") (name "/H_IN-_4") (class "Default")
      (node (ref "D14") (pin "1") (pinfunction "A_1") (pintype "passive"))
      (node (ref "HD15") (pin "1") (pinfunction "1_1") (pintype "passive"))
      (node (ref "OP11") (pin "2") (pinfunction "C_2") (pintype "passive"))
    )
    (net (code "101") (name "/H_IN-_5") (class "Default")
      (node (ref "D16") (pin "1") (pinfunction "A_1") (pintype "passive"))
      (node (ref "HD19") (pin "1") (pinfunction "1_1") (pintype "passive"))
      (node (ref "OP14") (pin "2") (pinfunction "C_2") (pintype "passive"))
    )
    (net (code "102") (name "/H_IN-_6") (class "Default")
      (node (ref "D18") (pin "1") (pinfunction "A_1") (pintype "passive"))
      (node (ref "HD22") (pin "1") (pinfunction "1_1") (pintype "passive"))
      (node (ref "OP16") (pin "2") (pinfunction "C_2") (pintype "passive"))
    )
    (net (code "103") (name "/H_IN-_7") (class "Default")
      (node (ref "D20") (pin "1") (pinfunction "A_1") (pintype "passive"))
      (node (ref "HD26") (pin "1") (pinfunction "1_1") (pintype "passive"))
      (node (ref "OP19") (pin "2") (pinfunction "C_2") (pintype "passive"))
    )
    (net (code "104") (name "/H_IN-_8") (class "Default")
      (node (ref "D3") (pin "1") (pinfunction "A_1") (pintype "passive"))
      (node (ref "HD1") (pin "1") (pinfunction "1_1") (pintype "passive"))
      (node (ref "OP2") (pin "2") (pinfunction "C_2") (pintype "passive"))
    )
    (net (code "105") (name "/H_IN-_9") (class "Default")
      (node (ref "D6") (pin "1") (pinfunction "A_1") (pintype "passive"))
      (node (ref "HD6") (pin "1") (pinfunction "1_1") (pintype "passive"))
      (node (ref "OP5") (pin "2") (pinfunction "C_2") (pintype "passive"))
    )
    (net (code "106") (name "/H_IN-_10") (class "Default")
      (node (ref "D11") (pin "1") (pinfunction "A_1") (pintype "passive"))
      (node (ref "HD10") (pin "1") (pinfunction "1_1") (pintype "passive"))
      (node (ref "OP7") (pin "2") (pinfunction "C_2") (pintype "passive"))
    )
    (net (code "107") (name "/H_IN-_11") (class "Default")
      (node (ref "D13") (pin "1") (pinfunction "A_1") (pintype "passive"))
      (node (ref "HD14") (pin "1") (pinfunction "1_1") (pintype "passive"))
      (node (ref "OP10") (pin "2") (pinfunction "C_2") (pintype "passive"))
    )
    (net (code "108") (name "/H_IN-_12") (class "Default")
      (node (ref "D15") (pin "1") (pinfunction "A_1") (pintype "passive"))
      (node (ref "HD16") (pin "1") (pinfunction "1_1") (pintype "passive"))
      (node (ref "OP12") (pin "2") (pinfunction "C_2") (pintype "passive"))
    )
    (net (code "109") (name "/H_IN-_13") (class "Default")
      (node (ref "D17") (pin "1") (pinfunction "A_1") (pintype "passive"))
      (node (ref "HD20") (pin "1") (pinfunction "1_1") (pintype "passive"))
      (node (ref "OP15") (pin "2") (pinfunction "C_2") (pintype "passive"))
    )
    (net (code "110") (name "/H_IN-_14") (class "Default")
      (node (ref "D19") (pin "1") (pinfunction "A_1") (pintype "passive"))
      (node (ref "HD23") (pin "1") (pinfunction "1_1") (pintype "passive"))
      (node (ref "OP17") (pin "2") (pinfunction "C_2") (pintype "passive"))
    )
    (net (code "111") (name "/H_IN-_15") (class "Default")
      (node (ref "D21") (pin "1") (pinfunction "A_1") (pintype "passive"))
      (node (ref "HD27") (pin "1") (pinfunction "1_1") (pintype "passive"))
      (node (ref "OP20") (pin "2") (pinfunction "C_2") (pintype "passive"))
    )
    (net (code "112") (name "/H_OUT+_6") (class "Default")
      (node (ref "HD35") (pin "1") (pinfunction "1_1") (pintype "passive"))
      (node (ref "R67") (pin "2") (pinfunction "2_2") (pintype "passive"))
    )
    (net (code "113") (name "/H_OUT+_7") (class "Default")
      (node (ref "HD37") (pin "1") (pinfunction "1_1") (pintype "passive"))
      (node (ref "R72") (pin "2") (pinfunction "2_2") (pintype "passive"))
    )
    (net (code "114") (name "/H_OUT+_8") (class "Default")
      (node (ref "HD38") (pin "1") (pinfunction "1_1") (pintype "passive"))
      (node (ref "R77") (pin "2") (pinfunction "2_2") (pintype "passive"))
    )
    (net (code "115") (name "/H_OUT+_9") (class "Default")
      (node (ref "HD41") (pin "1") (pinfunction "1_1") (pintype "passive"))
      (node (ref "R82") (pin "2") (pinfunction "2_2") (pintype "passive"))
    )
    (net (code "116") (name "/H_OUT+_10") (class "Default")
      (node (ref "HD43") (pin "1") (pinfunction "1_1") (pintype "passive"))
      (node (ref "R87") (pin "2") (pinfunction "2_2") (pintype "passive"))
    )
    (net (code "117") (name "/H_OUT+_11") (class "Default")
      (node (ref "HD44") (pin "1") (pinfunction "1_1") (pintype "passive"))
      (node (ref "R92") (pin "2") (pinfunction "2_2") (pintype "passive"))
    )
    (net (code "118") (name "/H_OUT-_6") (class "Default")
      (node (ref "D25") (pin "1") (pinfunction "A_1") (pintype "passive"))
      (node (ref "HD35") (pin "2") (pinfunction "2_2") (pintype "passive"))
      (node (ref "OP24") (pin "3") (pinfunction "C_3") (pintype "passive"))
    )
    (net (code "119") (name "/H_OUT-_7") (class "Default")
      (node (ref "D27") (pin "1") (pinfunction "A_1") (pintype "passive"))
      (node (ref "HD37") (pin "2") (pinfunction "2_2") (pintype "passive"))
      (node (ref "OP26") (pin "3") (pinfunction "C_3") (pintype "passive"))
    )
    (net (code "120") (name "/H_OUT-_8") (class "Default")
      (node (ref "D29") (pin "1") (pinfunction "A_1") (pintype "passive"))
      (node (ref "HD38") (pin "2") (pinfunction "2_2") (pintype "passive"))
      (node (ref "OP28") (pin "3") (pinfunction "C_3") (pintype "passive"))
    )
    (net (code "121") (name "/H_OUT-_9") (class "Default")
      (node (ref "D31") (pin "1") (pinfunction "A_1") (pintype "passive"))
      (node (ref "HD41") (pin "2") (pinfunction "2_2") (pintype "passive"))
      (node (ref "OP29") (pin "3") (pinfunction "C_3") (pintype "passive"))
    )
    (net (code "122") (name "/H_OUT-_10") (class "Default")
      (node (ref "D33") (pin "1") (pinfunction "A_1") (pintype "passive"))
      (node (ref "HD43") (pin "2") (pinfunction "2_2") (pintype "passive"))
      (node (ref "OP31") (pin "3") (pinfunction "C_3") (pintype "passive"))
    )
    (net (code "123") (name "/H_OUT-_11") (class "Default")
      (node (ref "D35") (pin "1") (pinfunction "A_1") (pintype "passive"))
      (node (ref "HD44") (pin "2") (pinfunction "2_2") (pintype "passive"))
      (node (ref "OP33") (pin "3") (pinfunction "C_3") (pintype "passive"))
    )
    (net (code "124") (name "/H_PWM_0") (class "Default")
      (node (ref "HD4") (pin "2") (pinfunction "2_2") (pintype "passive"))
      (node (ref "OP3") (pin "7") (pinfunction "Vo1_7") (pintype "passive"))
      (node (ref "R4") (pin "2") (pinfunction "2_2") (pintype "passive"))
    )
    (net (code "125") (name "/H_PWM_1") (class "Default")
      (node (ref "HD11") (pin "2") (pinfunction "2_2") (pintype "passive"))
      (node (ref "OP8") (pin "7") (pinfunction "Vo1_7") (pintype "passive"))
      (node (ref "R18") (pin "2") (pinfunction "2_2") (pintype "passive"))
    )
    (net (code "126") (name "/H_PWM_2") (class "Default")
      (node (ref "HD18") (pin "2") (pinfunction "2_2") (pintype "passive"))
      (node (ref "OP13") (pin "7") (pinfunction "Vo1_7") (pintype "passive"))
      (node (ref "R30") (pin "2") (pinfunction "2_2") (pintype "passive"))
    )
    (net (code "127") (name "/H_PWM_3") (class "Default")
      (node (ref "HD24") (pin "2") (pinfunction "2_2") (pintype "passive"))
      (node (ref "OP18") (pin "7") (pinfunction "Vo1_7") (pintype "passive"))
      (node (ref "R44") (pin "2") (pinfunction "2_2") (pintype "passive"))
    )
    (net (code "128") (name "/H_PWM_4") (class "Default")
      (node (ref "HD30") (pin "2") (pinfunction "2_2") (pintype "passive"))
      (node (ref "OP21") (pin "7") (pinfunction "Vo1_7") (pintype "passive"))
      (node (ref "R53") (pin "2") (pinfunction "2_2") (pintype "passive"))
    )
    (net (code "129") (name "/H_PWM_5") (class "Default")
      (node (ref "HD34") (pin "2") (pinfunction "2_2") (pintype "passive"))
      (node (ref "OP22") (pin "7") (pinfunction "Vo1_7") (pintype "passive"))
      (node (ref "R60") (pin "2") (pinfunction "2_2") (pintype "passive"))
    )
    (net (code "130") (name "/H_RLY_1") (class "Default")
      (node (ref "HD40") (pin "7") (pinfunction "7_7") (pintype "passive"))
      (node (ref "Q1") (pin "2") (pinfunction "E_2") (pintype "passive"))
    )
    (net (code "131") (name "/H_RLY_2") (class "Default")
      (node (ref "HD40") (pin "6") (pinfunction "6_6") (pintype "passive"))
      (node (ref "Q2") (pin "2") (pinfunction "E_2") (pintype "passive"))
    )
    (net (code "132") (name "/H_RLY_3") (class "Default")
      (node (ref "HD40") (pin "5") (pinfunction "5_5") (pintype "passive"))
      (node (ref "Q3") (pin "2") (pinfunction "E_2") (pintype "passive"))
    )
    (net (code "133") (name "/H_RLY_4") (class "Default")
      (node (ref "HD40") (pin "4") (pinfunction "4_4") (pintype "passive"))
      (node (ref "Q4") (pin "2") (pinfunction "E_2") (pintype "passive"))
    )
    (net (code "134") (name "/H_RLY_5") (class "Default")
      (node (ref "HD40") (pin "3") (pinfunction "3_3") (pintype "passive"))
      (node (ref "Q5") (pin "2") (pinfunction "E_2") (pintype "passive"))
    )
    (net (code "135") (name "/H_RLY_6") (class "Default")
      (node (ref "HD40") (pin "2") (pinfunction "2_2") (pintype "passive"))
      (node (ref "Q6") (pin "2") (pinfunction "E_2") (pintype "passive"))
    )
    (net (code "136") (name "/IMU_RX") (class "Default")
      (node (ref "H2") (pin "3") (pinfunction "3_3") (pintype "passive"))
      (node (ref "U1") (pin "84") (pinfunction "84_84") (pintype "passive"))
    )
    (net (code "137") (name "/IMU_TX") (class "Default")
      (node (ref "H2") (pin "2") (pinfunction "2_2") (pintype "passive"))
      (node (ref "U1") (pin "49") (pinfunction "49_49") (pintype "passive"))
    )
    (net (code "138") (name "/IN_0") (class "Default")
      (node (ref "U1") (pin "68") (pinfunction "68_68") (pintype "passive"))
      (node (ref "U8") (pin "14") (pinfunction "B7_14") (pintype "passive"))
    )
    (net (code "139") (name "/IN_1") (class "Default")
      (node (ref "U1") (pin "67") (pinfunction "67_67") (pintype "passive"))
      (node (ref "U8") (pin "15") (pinfunction "B6_15") (pintype "passive"))
    )
    (net (code "140") (name "/IN_2") (class "Default")
      (node (ref "U1") (pin "66") (pinfunction "66_66") (pintype "passive"))
      (node (ref "U8") (pin "16") (pinfunction "B5_16") (pintype "passive"))
    )
    (net (code "141") (name "/IN_3") (class "Default")
      (node (ref "U1") (pin "65") (pinfunction "65_65") (pintype "passive"))
      (node (ref "U8") (pin "17") (pinfunction "B4_17") (pintype "passive"))
    )
    (net (code "142") (name "/IN_11") (class "Default")
      (node (ref "U1") (pin "9") (pinfunction "9_9") (pintype "passive"))
      (node (ref "U9") (pin "17") (pinfunction "B4_17") (pintype "passive"))
    )
    (net (code "143") (name "/IN_12") (class "Default")
      (node (ref "U1") (pin "35") (pinfunction "35_35") (pintype "passive"))
      (node (ref "U9") (pin "18") (pinfunction "B3_18") (pintype "passive"))
    )
    (net (code "144") (name "/IN_13") (class "Default")
      (node (ref "U1") (pin "10") (pinfunction "10_10") (pintype "passive"))
      (node (ref "U9") (pin "19") (pinfunction "B2_19") (pintype "passive"))
    )
    (net (code "145") (name "/IN_14") (class "Default")
      (node (ref "U1") (pin "23") (pinfunction "23_23") (pintype "passive"))
      (node (ref "U9") (pin "20") (pinfunction "B1_20") (pintype "passive"))
    )
    (net (code "146") (name "/IN_15") (class "Default")
      (node (ref "U1") (pin "22") (pinfunction "22_22") (pintype "passive"))
      (node (ref "U9") (pin "21") (pinfunction "B0_21") (pintype "passive"))
    )
    (net (code "147") (name "/I_ENC_A0") (class "Default")
      (node (ref "U4") (pin "2") (pintype "passive"))
      (node (ref "U7") (pin "3") (pinfunction "A0_3") (pintype "passive"))
    )
    (net (code "148") (name "/I_ENC_A1") (class "Default")
      (node (ref "U4") (pin "6") (pintype "passive"))
      (node (ref "U7") (pin "6") (pinfunction "A3_6") (pintype "passive"))
    )
    (net (code "149") (name "/I_ENC_A2") (class "Default")
      (node (ref "U4") (pin "10") (pinfunction "9_10") (pintype "passive"))
      (node (ref "U7") (pin "9") (pinfunction "A6_9") (pintype "passive"))
    )
    (net (code "150") (name "/I_ENC_A3") (class "Default")
      (node (ref "U11") (pin "3") (pinfunction "A0_3") (pintype "passive"))
      (node (ref "U5") (pin "2") (pintype "passive"))
    )
    (net (code "151") (name "/I_ENC_A4") (class "Default")
      (node (ref "U11") (pin "6") (pinfunction "A3_6") (pintype "passive"))
      (node (ref "U5") (pin "6") (pintype "passive"))
    )
    (net (code "152") (name "/I_ENC_A5") (class "Default")
      (node (ref "U11") (pin "9") (pinfunction "A6_9") (pintype "passive"))
      (node (ref "U5") (pin "10") (pinfunction "9_10") (pintype "passive"))
    )
    (net (code "153") (name "/I_ENC_B0") (class "Default")
      (node (ref "U4") (pin "4") (pintype "passive"))
      (node (ref "U7") (pin "4") (pinfunction "A1_4") (pintype "passive"))
    )
    (net (code "154") (name "/I_ENC_B1") (class "Default")
      (node (ref "U4") (pin "8") (pinfunction "7_8") (pintype "passive"))
      (node (ref "U7") (pin "7") (pinfunction "A4_7") (pintype "passive"))
    )
    (net (code "155") (name "/I_ENC_B2") (class "Default")
      (node (ref "U4") (pin "12") (pinfunction "11_12") (pintype "passive"))
      (node (ref "U7") (pin "10") (pinfunction "A7_10") (pintype "passive"))
    )
    (net (code "156") (name "/I_ENC_B3") (class "Default")
      (node (ref "U11") (pin "4") (pinfunction "A1_4") (pintype "passive"))
      (node (ref "U5") (pin "4") (pintype "passive"))
    )
    (net (code "157") (name "/I_ENC_B4") (class "Default")
      (node (ref "U11") (pin "7") (pinfunction "A4_7") (pintype "passive"))
      (node (ref "U5") (pin "8") (pinfunction "7_8") (pintype "passive"))
    )
    (net (code "158") (name "/I_ENC_B5") (class "Default")
      (node (ref "U11") (pin "10") (pinfunction "A7_10") (pintype "passive"))
      (node (ref "U5") (pin "12") (pinfunction "11_12") (pintype "passive"))
    )
    (net (code "159") (name "/LED ERROR") (class "Default")
      (node (ref "RN2") (pin "2") (pinfunction "2_2") (pintype "passive"))
      (node (ref "U1") (pin "87") (pinfunction "87_87") (pintype "passive"))
      (node (ref "U6") (pin "9") (pinfunction "A7_9") (pintype "passive"))
    )
    (net (code "160") (name "/LED IDLE") (class "Default")
      (node (ref "RN2") (pin "3") (pinfunction "3_3") (pintype "passive"))
      (node (ref "U1") (pin "47") (pinfunction "47_47") (pintype "passive"))
      (node (ref "U6") (pin "8") (pinfunction "A6_8") (pintype "passive"))
    )
    (net (code "161") (name "/LED READY") (class "Default")
      (node (ref "RN2") (pin "4") (pinfunction "4_4") (pintype "passive"))
      (node (ref "U1") (pin "39") (pinfunction "39_39") (pintype "passive"))
      (node (ref "U6") (pin "7") (pinfunction "A5_7") (pintype "passive"))
    )
    (net (code "162") (name "/NRST") (class "Default")
      (node (ref "C33") (pin "1") (pinfunction "1_1") (pintype "passive"))
      (node (ref "R26") (pin "2") (pinfunction "2_2") (pintype "passive"))
      (node (ref "S1") (pin "2") (pinfunction "2_2") (pintype "passive"))
      (node (ref "U1") (pin "6") (pinfunction "6_6") (pintype "passive"))
    )
    (net (code "167") (name "/OUT_0") (class "Default")
      (node (ref "RN1") (pin "5") (pinfunction "5_5") (pintype "passive"))
      (node (ref "U1") (pin "13") (pinfunction "13_13") (pintype "passive"))
      (node (ref "U3") (pin "6") (pinfunction "A4_6") (pintype "passive"))
    )
    (net (code "168") (name "/OUT_1") (class "Default")
      (node (ref "RN1") (pin "4") (pinfunction "4_4") (pintype "passive"))
      (node (ref "U1") (pin "32") (pinfunction "32_32") (pintype "passive"))
      (node (ref "U3") (pin "7") (pinfunction "A5_7") (pintype "passive"))
    )
    (net (code "169") (name "/OUT_2") (class "Default")
      (node (ref "RN1") (pin "3") (pinfunction "3_3") (pintype "passive"))
      (node (ref "U1") (pin "11") (pinfunction "11_11") (pintype "passive"))
      (node (ref "U3") (pin "8") (pinfunction "A6_8") (pintype "passive"))
    )
    (net (code "170") (name "/OUT_3") (class "Default")
      (node (ref "RN1") (pin "2") (pinfunction "2_2") (pintype "passive"))
      (node (ref "U1") (pin "2") (pinfunction "2_2") (pintype "passive"))
      (node (ref "U3") (pin "9") (pinfunction "A7_9") (pintype "passive"))
    )
    (net (code "171") (name "/OUT_4") (class "Default")
      (node (ref "RN2") (pin "9") (pinfunction "9_9") (pintype "passive"))
      (node (ref "U1") (pin "43") (pinfunction "43_43") (pintype "passive"))
      (node (ref "U6") (pin "2") (pinfunction "A0_2") (pintype "passive"))
    )
    (net (code "172") (name "/OUT_5") (class "Default")
      (node (ref "RN2") (pin "8") (pinfunction "8_8") (pintype "passive"))
      (node (ref "U1") (pin "3") (pinfunction "3_3") (pintype "passive"))
      (node (ref "U6") (pin "3") (pinfunction "A1_3") (pintype "passive"))
    )
    (net (code "173") (name "/OUT_6") (class "Default")
      (node (ref "RN2") (pin "7") (pinfunction "7_7") (pintype "passive"))
      (node (ref "U1") (pin "42") (pinfunction "42_42") (pintype "passive"))
      (node (ref "U6") (pin "4") (pinfunction "A2_4") (pintype "passive"))
    )
    (net (code "174") (name "/OUT_7") (class "Default")
      (node (ref "RN2") (pin "6") (pinfunction "6_6") (pintype "passive"))
      (node (ref "U1") (pin "5") (pinfunction "5_5") (pintype "passive"))
      (node (ref "U6") (pin "5") (pinfunction "A3_5") (pintype "passive"))
    )
    (net (code "175") (name "/OUT_8") (class "Default")
      (node (ref "RN2") (pin "5") (pinfunction "5_5") (pintype "passive"))
      (node (ref "U1") (pin "40") (pinfunction "40_40") (pintype "passive"))
      (node (ref "U6") (pin "6") (pinfunction "A4_6") (pintype "passive"))
    )
    (net (code "176") (name "/O_DIR_0") (class "Default")
      (node (ref "R6") (pin "1") (pinfunction "1_1") (pintype "passive"))
      (node (ref "U3") (pin "16") (pinfunction "B2_16") (pintype "passive"))
    )
    (net (code "177") (name "/O_DIR_1") (class "Default")
      (node (ref "R21") (pin "1") (pinfunction "1_1") (pintype "passive"))
      (node (ref "U3") (pin "18") (pinfunction "B0_18") (pintype "passive"))
    )
    (net (code "178") (name "/O_DIR_2") (class "Default")
      (node (ref "R34") (pin "1") (pinfunction "1_1") (pintype "passive"))
      (node (ref "U10") (pin "12") (pinfunction "B6_12") (pintype "passive"))
    )
    (net (code "179") (name "/O_DIR_3") (class "Default")
      (node (ref "R46") (pin "1") (pinfunction "1_1") (pintype "passive"))
      (node (ref "U10") (pin "14") (pinfunction "B4_14") (pintype "passive"))
    )
    (net (code "180") (name "/O_DIR_4") (class "Default")
      (node (ref "R56") (pin "1") (pinfunction "1_1") (pintype "passive"))
      (node (ref "U10") (pin "16") (pinfunction "B2_16") (pintype "passive"))
    )
    (net (code "181") (name "/O_DIR_5") (class "Default")
      (node (ref "R63") (pin "1") (pinfunction "1_1") (pintype "passive"))
      (node (ref "U10") (pin "18") (pinfunction "B0_18") (pintype "passive"))
    )
    (net (code "182") (name "/O_ENC_A0") (class "Default")
      (node (ref "C7") (pin "1") (pinfunction "1_1") (pintype "passive"))
      (node (ref "IC1") (pin "1") (pinfunction "RO_1") (pintype "passive"))
      (node (ref "R3") (pin "2") (pinfunction "2_2") (pintype "passive"))
      (node (ref "U4") (pin "1") (pintype "passive"))
    )
    (net (code "183") (name "/O_ENC_A1") (class "Default")
      (node (ref "C27") (pin "1") (pinfunction "1_1") (pintype "passive"))
      (node (ref "IC4") (pin "1") (pinfunction "RO_1") (pintype "passive"))
      (node (ref "R20") (pin "2") (pinfunction "2_2") (pintype "passive"))
      (node (ref "U4") (pin "5") (pintype "passive"))
    )
    (net (code "184") (name "/O_ENC_A2") (class "Default")
      (node (ref "C46") (pin "1") (pinfunction "1_1") (pintype "passive"))
      (node (ref "IC6") (pin "1") (pinfunction "RO_1") (pintype "passive"))
      (node (ref "R37") (pin "2") (pinfunction "2_2") (pintype "passive"))
      (node (ref "U4") (pin "11") (pinfunction "10_11") (pintype "passive"))
    )
    (net (code "185") (name "/O_ENC_A3") (class "Default")
      (node (ref "C63") (pin "1") (pinfunction "1_1") (pintype "passive"))
      (node (ref "IC10") (pin "1") (pinfunction "RO_1") (pintype "passive"))
      (node (ref "R51") (pin "2") (pinfunction "2_2") (pintype "passive"))
      (node (ref "U5") (pin "1") (pintype "passive"))
    )
    (net (code "186") (name "/O_ENC_A4") (class "Default")
      (node (ref "C87") (pin "1") (pinfunction "1_1") (pintype "passive"))
      (node (ref "IC13") (pin "1") (pinfunction "RO_1") (pintype "passive"))
      (node (ref "R59") (pin "2") (pinfunction "2_2") (pintype "passive"))
      (node (ref "U5") (pin "5") (pintype "passive"))
    )
    (net (code "187") (name "/O_ENC_A5") (class "Default")
      (node (ref "C96") (pin "1") (pinfunction "1_1") (pintype "passive"))
      (node (ref "IC15") (pin "1") (pinfunction "RO_1") (pintype "passive"))
      (node (ref "R78") (pin "2") (pinfunction "2_2") (pintype "passive"))
      (node (ref "U5") (pin "11") (pinfunction "10_11") (pintype "passive"))
    )
    (net (code "188") (name "/O_ENC_B0") (class "Default")
      (node (ref "C20") (pin "1") (pinfunction "1_1") (pintype "passive"))
      (node (ref "IC3") (pin "1") (pinfunction "RO_1") (pintype "passive"))
      (node (ref "R14") (pin "2") (pinfunction "2_2") (pintype "passive"))
      (node (ref "U4") (pin "3") (pintype "passive"))
    )
    (net (code "189") (name "/O_ENC_B1") (class "Default")
      (node (ref "C39") (pin "1") (pinfunction "1_1") (pintype "passive"))
      (node (ref "IC5") (pin "1") (pinfunction "RO_1") (pintype "passive"))
      (node (ref "R29") (pin "2") (pinfunction "2_2") (pintype "passive"))
      (node (ref "U4") (pin "9") (pinfunction "8_9") (pintype "passive"))
    )
    (net (code "190") (name "/O_ENC_B2") (class "Default")
      (node (ref "C54") (pin "1") (pinfunction "1_1") (pintype "passive"))
      (node (ref "IC8") (pin "1") (pinfunction "RO_1") (pintype "passive"))
      (node (ref "R43") (pin "2") (pinfunction "2_2") (pintype "passive"))
      (node (ref "U4") (pin "13") (pinfunction "12_13") (pintype "passive"))
    )
    (net (code "191") (name "/O_ENC_B3") (class "Default")
      (node (ref "C77") (pin "1") (pinfunction "1_1") (pintype "passive"))
      (node (ref "IC12") (pin "1") (pinfunction "RO_1") (pintype "passive"))
      (node (ref "R55") (pin "2") (pinfunction "2_2") (pintype "passive"))
      (node (ref "U5") (pin "3") (pintype "passive"))
    )
    (net (code "192") (name "/O_ENC_B4") (class "Default")
      (node (ref "C92") (pin "1") (pinfunction "1_1") (pintype "passive"))
      (node (ref "IC14") (pin "1") (pinfunction "RO_1") (pintype "passive"))
      (node (ref "R69") (pin "2") (pinfunction "2_2") (pintype "passive"))
      (node (ref "U5") (pin "9") (pinfunction "8_9") (pintype "passive"))
    )
    (net (code "193") (name "/O_ENC_B5") (class "Default")
      (node (ref "C100") (pin "1") (pinfunction "1_1") (pintype "passive"))
      (node (ref "IC16") (pin "1") (pinfunction "RO_1") (pintype "passive"))
      (node (ref "R85") (pin "2") (pinfunction "2_2") (pintype "passive"))
      (node (ref "U5") (pin "13") (pinfunction "12_13") (pintype "passive"))
    )
    (net (code "194") (name "/O_IN_0") (class "Default")
      (node (ref "C2") (pin "2") (pinfunction "2_2") (pintype "passive"))
      (node (ref "OP1") (pin "4") (pinfunction "E_4") (pintype "passive"))
      (node (ref "RN3") (pin "9") (pinfunction "9_9") (pintype "passive"))
      (node (ref "U8") (pin "10") (pinfunction "A7_10") (pintype "passive"))
    )
    (net (code "195") (name "/O_IN_1") (class "Default")
      (node (ref "C12") (pin "2") (pinfunction "2_2") (pintype "passive"))
      (node (ref "OP4") (pin "4") (pinfunction "E_4") (pintype "passive"))
      (node (ref "RN3") (pin "8") (pinfunction "8_8") (pintype "passive"))
      (node (ref "U8") (pin "9") (pinfunction "A6_9") (pintype "passive"))
    )
    (net (code "196") (name "/O_IN_2") (class "Default")
      (node (ref "C23") (pin "2") (pinfunction "2_2") (pintype "passive"))
      (node (ref "OP6") (pin "4") (pinfunction "E_4") (pintype "passive"))
      (node (ref "RN3") (pin "7") (pinfunction "7_7") (pintype "passive"))
      (node (ref "U8") (pin "8") (pinfunction "A5_8") (pintype "passive"))
    )
    (net (code "197") (name "/O_IN_3") (class "Default")
      (node (ref "C30") (pin "2") (pinfunction "2_2") (pintype "passive"))
      (node (ref "OP9") (pin "4") (pinfunction "E_4") (pintype "passive"))
      (node (ref "RN3") (pin "6") (pinfunction "6_6") (pintype "passive"))
      (node (ref "U8") (pin "7") (pinfunction "A4_7") (pintype "passive"))
    )
    (net (code "198") (name "/O_IN_4") (class "Default")
      (node (ref "C35") (pin "2") (pinfunction "2_2") (pintype "passive"))
      (node (ref "OP11") (pin "4") (pinfunction "E_4") (pintype "passive"))
      (node (ref "RN3") (pin "5") (pinfunction "5_5") (pintype "passive"))
      (node (ref "U8") (pin "6") (pinfunction "A3_6") (pintype "passive"))
    )
    (net (code "199") (name "/O_IN_5") (class "Default")
      (node (ref "C42") (pin "2") (pinfunction "2_2") (pintype "passive"))
      (node (ref "OP14") (pin "4") (pinfunction "E_4") (pintype "passive"))
      (node (ref "RN3") (pin "4") (pinfunction "4_4") (pintype "passive"))
      (node (ref "U8") (pin "5") (pinfunction "A2_5") (pintype "passive"))
    )
    (net (code "200") (name "/O_IN_6") (class "Default")
      (node (ref "C49") (pin "2") (pinfunction "2_2") (pintype "passive"))
      (node (ref "OP16") (pin "4") (pinfunction "E_4") (pintype "passive"))
      (node (ref "RN3") (pin "3") (pinfunction "3_3") (pintype "passive"))
      (node (ref "U8") (pin "4") (pinfunction "A1_4") (pintype "passive"))
    )
    (net (code "201") (name "/O_IN_7") (class "Default")
      (node (ref "C58") (pin "2") (pinfunction "2_2") (pintype "passive"))
      (node (ref "OP19") (pin "4") (pinfunction "E_4") (pintype "passive"))
      (node (ref "RN3") (pin "2") (pinfunction "2_2") (pintype "passive"))
      (node (ref "U8") (pin "3") (pinfunction "A0_3") (pintype "passive"))
    )
    (net (code "202") (name "/O_IN_8") (class "Default")
      (node (ref "C3") (pin "2") (pinfunction "2_2") (pintype "passive"))
      (node (ref "OP2") (pin "4") (pinfunction "E_4") (pintype "passive"))
      (node (ref "RN4") (pin "9") (pinfunction "9_9") (pintype "passive"))
      (node (ref "U9") (pin "10") (pinfunction "A7_10") (pintype "passive"))
    )
    (net (code "203") (name "/O_IN_9") (class "Default")
      (node (ref "C13") (pin "2") (pinfunction "2_2") (pintype "passive"))
      (node (ref "OP5") (pin "4") (pinfunction "E_4") (pintype "passive"))
      (node (ref "RN4") (pin "8") (pinfunction "8_8") (pintype "passive"))
      (node (ref "U9") (pin "9") (pinfunction "A6_9") (pintype "passive"))
    )
    (net (code "204") (name "/O_IN_10") (class "Default")
      (node (ref "C24") (pin "2") (pinfunction "2_2") (pintype "passive"))
      (node (ref "OP7") (pin "4") (pinfunction "E_4") (pintype "passive"))
      (node (ref "RN4") (pin "7") (pinfunction "7_7") (pintype "passive"))
      (node (ref "U9") (pin "8") (pinfunction "A5_8") (pintype "passive"))
    )
    (net (code "205") (name "/O_IN_11") (class "Default")
      (node (ref "C31") (pin "2") (pinfunction "2_2") (pintype "passive"))
      (node (ref "OP10") (pin "4") (pinfunction "E_4") (pintype "passive"))
      (node (ref "RN4") (pin "6") (pinfunction "6_6") (pintype "passive"))
      (node (ref "U9") (pin "7") (pinfunction "A4_7") (pintype "passive"))
    )
    (net (code "206") (name "/O_IN_12") (class "Default")
      (node (ref "C36") (pin "2") (pinfunction "2_2") (pintype "passive"))
      (node (ref "OP12") (pin "4") (pinfunction "E_4") (pintype "passive"))
      (node (ref "RN4") (pin "5") (pinfunction "5_5") (pintype "passive"))
      (node (ref "U9") (pin "6") (pinfunction "A3_6") (pintype "passive"))
    )
    (net (code "207") (name "/O_IN_13") (class "Default")
      (node (ref "C43") (pin "2") (pinfunction "2_2") (pintype "passive"))
      (node (ref "OP15") (pin "4") (pinfunction "E_4") (pintype "passive"))
      (node (ref "RN4") (pin "4") (pinfunction "4_4") (pintype "passive"))
      (node (ref "U9") (pin "5") (pinfunction "A2_5") (pintype "passive"))
    )
    (net (code "208") (name "/O_IN_14") (class "Default")
      (node (ref "C51") (pin "2") (pinfunction "2_2") (pintype "passive"))
      (node (ref "OP17") (pin "4") (pinfunction "E_4") (pintype "passive"))
      (node (ref "RN4") (pin "3") (pinfunction "3_3") (pintype "passive"))
      (node (ref "U9") (pin "4") (pinfunction "A1_4") (pintype "passive"))
    )
    (net (code "209") (name "/O_IN_15") (class "Default")
      (node (ref "C59") (pin "2") (pinfunction "2_2") (pintype "passive"))
      (node (ref "OP20") (pin "4") (pinfunction "E_4") (pintype "passive"))
      (node (ref "RN4") (pin "2") (pinfunction "2_2") (pintype "passive"))
      (node (ref "U9") (pin "3") (pinfunction "A0_3") (pintype "passive"))
    )
    (net (code "210") (name "/O_OUT_0") (class "Default")
      (node (ref "D24") (pin "1") (pinfunction "A_1") (pintype "passive"))
      (node (ref "U3") (pin "14") (pinfunction "B4_14") (pintype "passive"))
    )
    (net (code "211") (name "/O_OUT_1") (class "Default")
      (node (ref "D26") (pin "1") (pinfunction "A_1") (pintype "passive"))
      (node (ref "U3") (pin "13") (pinfunction "B5_13") (pintype "passive"))
    )
    (net (code "212") (name "/O_OUT_2") (class "Default")
      (node (ref "D28") (pin "1") (pinfunction "A_1") (pintype "passive"))
      (node (ref "U3") (pin "12") (pinfunction "B6_12") (pintype "passive"))
    )
    (net (code "213") (name "/O_OUT_3") (class "Default")
      (node (ref "D30") (pin "1") (pinfunction "A_1") (pintype "passive"))
      (node (ref "U3") (pin "11") (pinfunction "B7_11") (pintype "passive"))
    )
    (net (code "214") (name "/O_OUT_4") (class "Default")
      (node (ref "D32") (pin "1") (pinfunction "A_1") (pintype "passive"))
      (node (ref "U6") (pin "18") (pinfunction "B0_18") (pintype "passive"))
    )
    (net (code "215") (name "/O_OUT_5") (class "Default")
      (node (ref "D34") (pin "1") (pinfunction "A_1") (pintype "passive"))
      (node (ref "U6") (pin "17") (pinfunction "B1_17") (pintype "passive"))
    )
    (net (code "216") (name "/O_OUT_6") (class "Default")
      (node (ref "R66") (pin "2") (pinfunction "2_2") (pintype "passive"))
      (node (ref "U6") (pin "16") (pinfunction "B2_16") (pintype "passive"))
    )
    (net (code "217") (name "/O_OUT_7") (class "Default")
      (node (ref "R71") (pin "2") (pinfunction "2_2") (pintype "passive"))
      (node (ref "U6") (pin "15") (pinfunction "B3_15") (pintype "passive"))
    )
    (net (code "218") (name "/O_OUT_8") (class "Default")
      (node (ref "R76") (pin "2") (pinfunction "2_2") (pintype "passive"))
      (node (ref "U6") (pin "14") (pinfunction "B4_14") (pintype "passive"))
    )
    (net (code "219") (name "/O_OUT_9") (class "Default")
      (node (ref "R81") (pin "2") (pinfunction "2_2") (pintype "passive"))
      (node (ref "U6") (pin "13") (pinfunction "B5_13") (pintype "passive"))
    )
    (net (code "220") (name "/O_OUT_10") (class "Default")
      (node (ref "R86") (pin "2") (pinfunction "2_2") (pintype "passive"))
      (node (ref "U6") (pin "12") (pinfunction "B6_12") (pintype "passive"))
    )
    (net (code "221") (name "/O_OUT_11") (class "Default")
      (node (ref "R91") (pin "2") (pinfunction "2_2") (pintype "passive"))
      (node (ref "U6") (pin "11") (pinfunction "B7_11") (pintype "passive"))
    )
    (net (code "222") (name "/O_PWM_0") (class "Default")
      (node (ref "R5") (pin "1") (pinfunction "1_1") (pintype "passive"))
      (node (ref "U3") (pin "15") (pinfunction "B3_15") (pintype "passive"))
    )
    (net (code "223") (name "/O_PWM_1") (class "Default")
      (node (ref "R19") (pin "1") (pinfunction "1_1") (pintype "passive"))
      (node (ref "U3") (pin "17") (pinfunction "B1_17") (pintype "passive"))
    )
    (net (code "224") (name "/O_PWM_2") (class "Default")
      (node (ref "R32") (pin "1") (pinfunction "1_1") (pintype "passive"))
      (node (ref "U10") (pin "11") (pinfunction "B7_11") (pintype "passive"))
    )
    (net (code "225") (name "/O_PWM_3") (class "Default")
      (node (ref "R45") (pin "1") (pinfunction "1_1") (pintype "passive"))
      (node (ref "U10") (pin "13") (pinfunction "B5_13") (pintype "passive"))
    )
    (net (code "226") (name "/O_PWM_4") (class "Default")
      (node (ref "R54") (pin "1") (pinfunction "1_1") (pintype "passive"))
      (node (ref "U10") (pin "15") (pinfunction "B3_15") (pintype "passive"))
    )
    (net (code "227") (name "/O_PWM_5") (class "Default")
      (node (ref "R61") (pin "1") (pinfunction "1_1") (pintype "passive"))
      (node (ref "U10") (pin "17") (pinfunction "B1_17") (pintype "passive"))
    )
    (net (code "228") (name "/P02") (class "Default")
      (node (ref "U1") (pin "15") (pinfunction "15_15") (pintype "passive"))
    )
    (net (code "229") (name "/P03") (class "Default")
      (node (ref "U1") (pin "30") (pinfunction "30_30") (pintype "passive"))
    )
    (net (code "230") (name "/P04") (class "Default")
      (node (ref "RN1") (pin "6") (pinfunction "6_6") (pintype "passive"))
      (node (ref "U1") (pin "16") (pinfunction "16_16") (pintype "passive"))
      (node (ref "U3") (pin "5") (pinfunction "A3_5") (pintype "passive"))
    )
    (net (code "231") (name "/P06") (class "Default")
      (node (ref "RN1") (pin "8") (pinfunction "8_8") (pintype "passive"))
      (node (ref "U1") (pin "17") (pinfunction "17_17") (pintype "passive"))
      (node (ref "U3") (pin "3") (pinfunction "A1_3") (pintype "passive"))
    )
    (net (code "232") (name "/P08") (class "Default")
      (node (ref "RN5") (pin "2") (pinfunction "2_2") (pintype "passive"))
      (node (ref "U1") (pin "18") (pinfunction "18_18") (pintype "passive"))
      (node (ref "U10") (pin "9") (pinfunction "A7_9") (pintype "passive"))
    )
    (net (code "233") (name "/P16") (class "Default")
      (node (ref "RN5") (pin "4") (pinfunction "4_4") (pintype "passive"))
      (node (ref "U1") (pin "19") (pinfunction "19_19") (pintype "passive"))
      (node (ref "U10") (pin "7") (pinfunction "A5_7") (pintype "passive"))
    )
    (net (code "234") (name "/P18") (class "Default")
      (node (ref "RN5") (pin "6") (pinfunction "6_6") (pintype "passive"))
      (node (ref "U1") (pin "20") (pinfunction "20_20") (pintype "passive"))
      (node (ref "U10") (pin "5") (pinfunction "A3_5") (pintype "passive"))
    )
    (net (code "235") (name "/P20") (class "Default")
      (node (ref "RN5") (pin "8") (pinfunction "8_8") (pintype "passive"))
      (node (ref "U1") (pin "21") (pinfunction "21_21") (pintype "passive"))
      (node (ref "U10") (pin "3") (pinfunction "A1_3") (pintype "passive"))
    )
    (net (code "236") (name "/PA0") (class "Default")
      (node (ref "U1") (pin "38") (pinfunction "38_38") (pintype "passive"))
    )
    (net (code "237") (name "/PA8") (class "Default")
      (node (ref "U1") (pin "83") (pinfunction "83_83") (pintype "passive"))
    )
    (net (code "238") (name "/PA11") (class "Default")
      (node (ref "U1") (pin "48") (pinfunction "48_48") (pintype "passive"))
    )
    (net (code "239") (name "/PA12") (class "Default")
      (node (ref "U1") (pin "85") (pinfunction "85_85") (pintype "passive"))
    )
    (net (code "240") (name "/PB10") (class "Default")
      (node (ref "H3") (pin "2") (pinfunction "2_2") (pintype "passive"))
      (node (ref "U1") (pin "55") (pinfunction "55_55") (pintype "passive"))
    )
    (net (code "241") (name "/PB11") (class "Default")
      (node (ref "H3") (pin "3") (pinfunction "3_3") (pintype "passive"))
      (node (ref "U1") (pin "78") (pinfunction "78_78") (pintype "passive"))
    )
    (net (code "242") (name "/PC8") (class "Default")
      (node (ref "U1") (pin "82") (pinfunction "82_82") (pintype "passive"))
    )
    (net (code "243") (name "/PC9") (class "Default")
      (node (ref "U1") (pin "50") (pinfunction "50_50") (pintype "passive"))
    )
    (net (code "244") (name "/PD0") (class "Default")
      (node (ref "U1") (pin "56") (pinfunction "56_56") (pintype "passive"))
    )
    (net (code "245") (name "/PD1") (class "Default")
      (node (ref "U1") (pin "77") (pinfunction "77_77") (pintype "passive"))
    )
    (net (code "246") (name "/PD2") (class "Default")
      (node (ref "U1") (pin "57") (pinfunction "57_57") (pintype "passive"))
    )
    (net (code "247") (name "/PD3") (class "Default")
      (node (ref "U1") (pin "76") (pinfunction "76_76") (pintype "passive"))
    )
    (net (code "248") (name "/RS485_A+") (class "Default")
      (node (ref "HD28") (pin "1") (pinfunction "1_1") (pintype "passive"))
      (node (ref "IC9") (pin "7") (pinfunction "A+_7") (pintype "passive"))
    )
    (net (code "249") (name "/RS485_B-") (class "Default")
      (node (ref "HD28") (pin "2") (pinfunction "2_2") (pintype "passive"))
      (node (ref "IC9") (pin "6") (pinfunction "B-_6") (pintype "passive"))
    )
    (net (code "250") (name "/RS485_G") (class "Default")
      (node (ref "HD28") (pin "3") (pinfunction "3_3") (pintype "passive"))
      (node (ref "IC9") (pin "5") (pinfunction "GE_5") (pintype "passive"))
    )
    (net (code "251") (name "3V3") (class "Default")
      (node (ref "C17") (pin "1") (pinfunction "1_1") (pintype "passive"))
      (node (ref "C18") (pin "1") (pinfunction "1_1") (pintype "passive"))
      (node (ref "C45") (pin "2") (pinfunction "2_2") (pintype "passive"))
      (node (ref "C56") (pin "2") (pinfunction "2_2") (pintype "passive"))
      (node (ref "C67") (pin "2") (pinfunction "2_2") (pintype "passive"))
      (node (ref "C69") (pin "2") (pinfunction "2_2") (pintype "passive"))
      (node (ref "C75") (pin "1") (pinfunction "1_1") (pintype "passive"))
      (node (ref "C76") (pin "1") (pinfunction "1_1") (pintype "passive"))
      (node (ref "C82") (pin "2") (pinfunction "2_2") (pintype "passive"))
      (node (ref "IC2") (pin "2") (pinfunction "OUT_2") (pintype "passive"))
      (node (ref "IC2") (pin "4") (pinfunction "PAD_4") (pintype "passive"))
      (node (ref "IC7") (pin "8") (pinfunction "VCC_8") (pintype "power_in"))
      (node (ref "R13") (pin "1") (pinfunction "1_1") (pintype "passive"))
      (node (ref "R26") (pin "1") (pinfunction "1_1") (pintype "passive"))
      (node (ref "R38") (pin "2") (pinfunction "2_2") (pintype "passive"))
      (node (ref "R39") (pin "1") (pinfunction "1_1") (pintype "passive"))
      (node (ref "U1") (pin "44") (pinfunction "44_44") (pintype "passive"))
      (node (ref "U1") (pin "7") (pinfunction "7_7") (pintype "passive"))
      (node (ref "U11") (pin "23") (pinfunction "VCCB_23") (pintype "passive"))
      (node (ref "U11") (pin "24") (pinfunction "VCC(B)_24") (pintype "passive"))
      (node (ref "U7") (pin "23") (pinfunction "VCCB_23") (pintype "passive"))
      (node (ref "U7") (pin "24") (pinfunction "VCC(B)_24") (pintype "passive"))
      (node (ref "U8") (pin "23") (pinfunction "VCCB_23") (pintype "passive"))
      (node (ref "U8") (pin "24") (pinfunction "VCC(B)_24") (pintype "passive"))
      (node (ref "U9") (pin "23") (pinfunction "VCCB_23") (pintype "passive"))
      (node (ref "U9") (pin "24") (pinfunction "VCC(B)_24") (pintype "passive"))
    )
    (net (code "252") (name "5V") (class "Default")
      (node (ref "C10") (pin "1") (pinfunction "1_1") (pintype "passive"))
      (node (ref "C15") (pin "1") (pinfunction "1_1") (pintype "passive"))
      (node (ref "C16") (pin "1") (pinfunction "1_1") (pintype "passive"))
      (node (ref "C19") (pin "1") (pinfunction "1_1") (pintype "passive"))
      (node (ref "C25") (pin "2") (pinfunction "2_2") (pintype "passive"))
      (node (ref "C28") (pin "1") (pinfunction "1_1") (pintype "passive"))
      (node (ref "C29") (pin "2") (pinfunction "2_2") (pintype "passive"))
      (node (ref "C38") (pin "1") (pinfunction "1_1") (pintype "passive"))
      (node (ref "C41") (pin "2") (pinfunction "2_2") (pintype "passive"))
      (node (ref "C47") (pin "1") (pinfunction "1_1") (pintype "passive"))
      (node (ref "C53") (pin "1") (pinfunction "1_1") (pintype "passive"))
      (node (ref "C57") (pin "2") (pinfunction "2_2") (pintype "passive"))
      (node (ref "C60") (pin "1") (pinfunction "1_1") (pintype "passive"))
      (node (ref "C62") (pin "1") (pinfunction "1_1") (pintype "passive"))
      (node (ref "C66") (pin "1") (pinfunction "1_1") (pintype "passive"))
      (node (ref "C68") (pin "2") (pinfunction "2_2") (pintype "passive"))
      (node (ref "C70") (pin "2") (pinfunction "2_2") (pintype "passive"))
      (node (ref "C72") (pin "2") (pinfunction "2_2") (pintype "passive"))
      (node (ref "C74") (pin "1") (pinfunction "1_1") (pintype "passive"))
      (node (ref "C79") (pin "1") (pinfunction "1_1") (pintype "passive"))
      (node (ref "C8") (pin "1") (pinfunction "1_1") (pintype "passive"))
      (node (ref "C80") (pin "1") (pinfunction "1_1") (pintype "passive"))
      (node (ref "C83") (pin "2") (pinfunction "2_2") (pintype "passive"))
      (node (ref "C86") (pin "1") (pinfunction "1_1") (pintype "passive"))
      (node (ref "C88") (pin "2") (pinfunction "2_2") (pintype "passive"))
      (node (ref "C9") (pin "2") (pinfunction "2_2") (pintype "passive"))
      (node (ref "C91") (pin "1") (pinfunction "1_1") (pintype "passive"))
      (node (ref "C95") (pin "1") (pinfunction "1_1") (pintype "passive"))
      (node (ref "C99") (pin "1") (pinfunction "1_1") (pintype "passive"))
      (node (ref "H1") (pin "1") (pinfunction "1_1") (pintype "passive"))
      (node (ref "H2") (pin "1") (pinfunction "1_1") (pintype "passive"))
      (node (ref "H3") (pin "1") (pinfunction "1_1") (pintype "passive"))
      (node (ref "HD32") (pin "4") (pinfunction "4_4") (pintype "passive"))
      (node (ref "IC1") (pin "8") (pinfunction "VCC_8") (pintype "passive"))
      (node (ref "IC10") (pin "8") (pinfunction "VCC_8") (pintype "passive"))
      (node (ref "IC11") (pin "8") (pinfunction "+V_8") (pintype "passive"))
      (node (ref "IC12") (pin "8") (pinfunction "VCC_8") (pintype "passive"))
      (node (ref "IC13") (pin "8") (pinfunction "VCC_8") (pintype "passive"))
      (node (ref "IC14") (pin "8") (pinfunction "VCC_8") (pintype "passive"))
      (node (ref "IC15") (pin "8") (pinfunction "VCC_8") (pintype "passive"))
      (node (ref "IC16") (pin "8") (pinfunction "VCC_8") (pintype "passive"))
      (node (ref "IC2") (pin "3") (pinfunction "IN_3") (pintype "passive"))
      (node (ref "IC3") (pin "8") (pinfunction "VCC_8") (pintype "passive"))
      (node (ref "IC4") (pin "8") (pinfunction "VCC_8") (pintype "passive"))
      (node (ref "IC5") (pin "8") (pinfunction "VCC_8") (pintype "passive"))
      (node (ref "IC6") (pin "8") (pinfunction "VCC_8") (pintype "passive"))
      (node (ref "IC8") (pin "8") (pinfunction "VCC_8") (pintype "passive"))
      (node (ref "IC9") (pin "1") (pinfunction "VCC_1") (pintype "passive"))
      (node (ref "L1") (pin "2") (pinfunction "2_2") (pintype "passive"))
      (node (ref "OP13") (pin "1") (pinfunction "A1_1") (pintype "passive"))
      (node (ref "OP13") (pin "4") (pinfunction "A2_4") (pintype "passive"))
      (node (ref "OP18") (pin "1") (pinfunction "A1_1") (pintype "passive"))
      (node (ref "OP18") (pin "4") (pinfunction "A2_4") (pintype "passive"))
      (node (ref "OP21") (pin "1") (pinfunction "A1_1") (pintype "passive"))
      (node (ref "OP21") (pin "4") (pinfunction "A2_4") (pintype "passive"))
      (node (ref "OP22") (pin "1") (pinfunction "A1_1") (pintype "passive"))
      (node (ref "OP22") (pin "4") (pinfunction "A2_4") (pintype "passive"))
      (node (ref "OP3") (pin "1") (pinfunction "A1_1") (pintype "passive"))
      (node (ref "OP3") (pin "4") (pinfunction "A2_4") (pintype "passive"))
      (node (ref "OP8") (pin "1") (pinfunction "A1_1") (pintype "passive"))
      (node (ref "OP8") (pin "4") (pinfunction "A2_4") (pintype "passive"))
      (node (ref "R11") (pin "1") (pinfunction "1_1") (pintype "passive"))
      (node (ref "R14") (pin "1") (pinfunction "1_1") (pintype "passive"))
      (node (ref "R20") (pin "1") (pinfunction "1_1") (pintype "passive"))
      (node (ref "R29") (pin "1") (pinfunction "1_1") (pintype "passive"))
      (node (ref "R3") (pin "1") (pinfunction "1_1") (pintype "passive"))
      (node (ref "R37") (pin "1") (pinfunction "1_1") (pintype "passive"))
      (node (ref "R43") (pin "1") (pinfunction "1_1") (pintype "passive"))
      (node (ref "R51") (pin "1") (pinfunction "1_1") (pintype "passive"))
      (node (ref "R55") (pin "1") (pinfunction "1_1") (pintype "passive"))
      (node (ref "R59") (pin "1") (pinfunction "1_1") (pintype "passive"))
      (node (ref "R69") (pin "1") (pinfunction "1_1") (pintype "passive"))
      (node (ref "R78") (pin "1") (pinfunction "1_1") (pintype "passive"))
      (node (ref "R85") (pin "1") (pinfunction "1_1") (pintype "passive"))
      (node (ref "RN3") (pin "1") (pinfunction "1_1") (pintype "passive"))
      (node (ref "RN4") (pin "1") (pinfunction "1_1") (pintype "passive"))
      (node (ref "U1") (pin "88") (pinfunction "88_88") (pintype "passive"))
      (node (ref "U10") (pin "1") (pinfunction "DIR_1") (pintype "passive"))
      (node (ref "U10") (pin "20") (pinfunction "VCC_20") (pintype "power_in"))
      (node (ref "U11") (pin "1") (pinfunction "VCC(A)_1") (pintype "passive"))
      (node (ref "U11") (pin "2") (pinfunction "DIR_2") (pintype "passive"))
      (node (ref "U2") (pin "4") (pinfunction "FB_4") (pintype "input"))
      (node (ref "U3") (pin "1") (pinfunction "DIR_1") (pintype "passive"))
      (node (ref "U3") (pin "20") (pinfunction "VCC_20") (pintype "power_in"))
      (node (ref "U4") (pin "14") (pinfunction "VCC_14") (pintype "passive"))
      (node (ref "U5") (pin "14") (pinfunction "VCC_14") (pintype "passive"))
      (node (ref "U6") (pin "1") (pinfunction "DIR_1") (pintype "passive"))
      (node (ref "U6") (pin "20") (pinfunction "VCC_20") (pintype "power_in"))
      (node (ref "U7") (pin "1") (pinfunction "VCC(A)_1") (pintype "passive"))
      (node (ref "U7") (pin "2") (pinfunction "DIR_2") (pintype "passive"))
      (node (ref "U8") (pin "1") (pinfunction "VCC(A)_1") (pintype "passive"))
      (node (ref "U8") (pin "2") (pinfunction "DIR_2") (pintype "passive"))
      (node (ref "U9") (pin "1") (pinfunction "VCC(A)_1") (pintype "passive"))
      (node (ref "U9") (pin "2") (pinfunction "DIR_2") (pintype "passive"))
    )
    (net (code "253") (name "24V") (class "Default")
      (node (ref "C5") (pin "1") (pinfunction "1_1") (pintype "passive"))
      (node (ref "C6") (pin "1") (pinfunction "1_1") (pintype "passive"))
      (node (ref "D1") (pin "2") (pintype "passive"))
      (node (ref "R12") (pin "1") (pinfunction "1_1") (pintype "passive"))
      (node (ref "U2") (pin "1") (pinfunction "VIN_1") (pintype "power_in"))
    )
    (net (code "254") (name "AGND") (class "Default")
      (node (ref "C10") (pin "2") (pinfunction "2_2") (pintype "passive"))
      (node (ref "C100") (pin "2") (pinfunction "2_2") (pintype "passive"))
      (node (ref "C101") (pin "2") (pinfunction "2_2") (pintype "passive"))
      (node (ref "C11") (pin "2") (pinfunction "2_2") (pintype "passive"))
      (node (ref "C12") (pin "1") (pinfunction "1_1") (pintype "passive"))
      (node (ref "C13") (pin "1") (pinfunction "1_1") (pintype "passive"))
      (node (ref "C14") (pin "1") (pinfunction "1_1") (pintype "passive"))
      (node (ref "C15") (pin "2") (pinfunction "2_2") (pintype "passive"))
      (node (ref "C16") (pin "2") (pinfunction "2_2") (pintype "passive"))
      (node (ref "C17") (pin "2") (pinfunction "2_2") (pintype "passive"))
      (node (ref "C18") (pin "2") (pinfunction "2_2") (pintype "passive"))
      (node (ref "C19") (pin "2") (pinfunction "2_2") (pintype "passive"))
      (node (ref "C2") (pin "1") (pinfunction "1_1") (pintype "passive"))
      (node (ref "C20") (pin "2") (pinfunction "2_2") (pintype "passive"))
      (node (ref "C21") (pin "2") (pinfunction "2_2") (pintype "passive"))
      (node (ref "C23") (pin "1") (pinfunction "1_1") (pintype "passive"))
      (node (ref "C24") (pin "1") (pinfunction "1_1") (pintype "passive"))
      (node (ref "C25") (pin "1") (pinfunction "1_1") (pintype "passive"))
      (node (ref "C26") (pin "1") (pinfunction "1_1") (pintype "passive"))
      (node (ref "C27") (pin "2") (pinfunction "2_2") (pintype "passive"))
      (node (ref "C28") (pin "2") (pinfunction "2_2") (pintype "passive"))
      (node (ref "C29") (pin "1") (pinfunction "1_1") (pintype "passive"))
      (node (ref "C3") (pin "1") (pinfunction "1_1") (pintype "passive"))
      (node (ref "C30") (pin "1") (pinfunction "1_1") (pintype "passive"))
      (node (ref "C31") (pin "1") (pinfunction "1_1") (pintype "passive"))
      (node (ref "C32") (pin "2") (pinfunction "2_2") (pintype "passive"))
      (node (ref "C33") (pin "2") (pinfunction "2_2") (pintype "passive"))
      (node (ref "C35") (pin "1") (pinfunction "1_1") (pintype "passive"))
      (node (ref "C36") (pin "1") (pinfunction "1_1") (pintype "passive"))
      (node (ref "C37") (pin "1") (pinfunction "1_1") (pintype "passive"))
      (node (ref "C38") (pin "2") (pinfunction "2_2") (pintype "passive"))
      (node (ref "C39") (pin "2") (pinfunction "2_2") (pintype "passive"))
      (node (ref "C4") (pin "1") (pinfunction "1_1") (pintype "passive"))
      (node (ref "C40") (pin "2") (pinfunction "2_2") (pintype "passive"))
      (node (ref "C41") (pin "1") (pinfunction "1_1") (pintype "passive"))
      (node (ref "C42") (pin "1") (pinfunction "1_1") (pintype "passive"))
      (node (ref "C43") (pin "1") (pinfunction "1_1") (pintype "passive"))
      (node (ref "C44") (pin "1") (pinfunction "1_1") (pintype "passive"))
      (node (ref "C45") (pin "1") (pinfunction "1_1") (pintype "passive"))
      (node (ref "C46") (pin "2") (pinfunction "2_2") (pintype "passive"))
      (node (ref "C47") (pin "2") (pinfunction "2_2") (pintype "passive"))
      (node (ref "C48") (pin "2") (pinfunction "2_2") (pintype "passive"))
      (node (ref "C49") (pin "1") (pinfunction "1_1") (pintype "passive"))
      (node (ref "C5") (pin "2") (pinfunction "2_2") (pintype "passive"))
      (node (ref "C51") (pin "1") (pinfunction "1_1") (pintype "passive"))
      (node (ref "C52") (pin "1") (pinfunction "1_1") (pintype "passive"))
      (node (ref "C53") (pin "2") (pinfunction "2_2") (pintype "passive"))
      (node (ref "C54") (pin "2") (pinfunction "2_2") (pintype "passive"))
      (node (ref "C55") (pin "2") (pinfunction "2_2") (pintype "passive"))
      (node (ref "C56") (pin "1") (pinfunction "1_1") (pintype "passive"))
      (node (ref "C57") (pin "1") (pinfunction "1_1") (pintype "passive"))
      (node (ref "C58") (pin "1") (pinfunction "1_1") (pintype "passive"))
      (node (ref "C59") (pin "1") (pinfunction "1_1") (pintype "passive"))
      (node (ref "C6") (pin "2") (pinfunction "2_2") (pintype "passive"))
      (node (ref "C60") (pin "2") (pinfunction "2_2") (pintype "passive"))
      (node (ref "C61") (pin "1") (pinfunction "1_1") (pintype "passive"))
      (node (ref "C62") (pin "2") (pinfunction "2_2") (pintype "passive"))
      (node (ref "C63") (pin "2") (pinfunction "2_2") (pintype "passive"))
      (node (ref "C64") (pin "2") (pinfunction "2_2") (pintype "passive"))
      (node (ref "C66") (pin "2") (pinfunction "2_2") (pintype "passive"))
      (node (ref "C67") (pin "1") (pinfunction "1_1") (pintype "passive"))
      (node (ref "C68") (pin "1") (pinfunction "1_1") (pintype "passive"))
      (node (ref "C69") (pin "1") (pinfunction "1_1") (pintype "passive"))
      (node (ref "C7") (pin "2") (pinfunction "2_2") (pintype "passive"))
      (node (ref "C70") (pin "1") (pinfunction "1_1") (pintype "passive"))
      (node (ref "C71") (pin "1") (pinfunction "1_1") (pintype "passive"))
      (node (ref "C72") (pin "1") (pinfunction "1_1") (pintype "passive"))
      (node (ref "C73") (pin "1") (pinfunction "1_1") (pintype "passive"))
      (node (ref "C74") (pin "2") (pinfunction "2_2") (pintype "passive"))
      (node (ref "C75") (pin "2") (pinfunction "2_2") (pintype "passive"))
      (node (ref "C76") (pin "2") (pinfunction "2_2") (pintype "passive"))
      (node (ref "C77") (pin "2") (pinfunction "2_2") (pintype "passive"))
      (node (ref "C78") (pin "2") (pinfunction "2_2") (pintype "passive"))
      (node (ref "C79") (pin "2") (pinfunction "2_2") (pintype "passive"))
      (node (ref "C8") (pin "2") (pinfunction "2_2") (pintype "passive"))
      (node (ref "C80") (pin "2") (pinfunction "2_2") (pintype "passive"))
      (node (ref "C81") (pin "1") (pinfunction "1_1") (pintype "passive"))
      (node (ref "C82") (pin "1") (pinfunction "1_1") (pintype "passive"))
      (node (ref "C83") (pin "1") (pinfunction "1_1") (pintype "passive"))
      (node (ref "C85") (pin "1") (pinfunction "1_1") (pintype "passive"))
      (node (ref "C86") (pin "2") (pinfunction "2_2") (pintype "passive"))
      (node (ref "C87") (pin "2") (pinfunction "2_2") (pintype "passive"))
      (node (ref "C88") (pin "1") (pinfunction "1_1") (pintype "passive"))
      (node (ref "C89") (pin "2") (pinfunction "2_2") (pintype "passive"))
      (node (ref "C9") (pin "1") (pinfunction "1_1") (pintype "passive"))
      (node (ref "C90") (pin "1") (pinfunction "1_1") (pintype "passive"))
      (node (ref "C91") (pin "2") (pinfunction "2_2") (pintype "passive"))
      (node (ref "C92") (pin "2") (pinfunction "2_2") (pintype "passive"))
      (node (ref "C93") (pin "2") (pinfunction "2_2") (pintype "passive"))
      (node (ref "C94") (pin "1") (pinfunction "1_1") (pintype "passive"))
      (node (ref "C95") (pin "2") (pinfunction "2_2") (pintype "passive"))
      (node (ref "C96") (pin "2") (pinfunction "2_2") (pintype "passive"))
      (node (ref "C97") (pin "2") (pinfunction "2_2") (pintype "passive"))
      (node (ref "C98") (pin "1") (pinfunction "1_1") (pintype "passive"))
      (node (ref "C99") (pin "2") (pinfunction "2_2") (pintype "passive"))
      (node (ref "D22") (pin "1") (pinfunction "A_1") (pintype "passive"))
      (node (ref "D23") (pin "1") (pinfunction "A_1") (pintype "passive"))
      (node (ref "D4") (pin "2") (pinfunction "B_2") (pintype "passive"))
      (node (ref "D7") (pin "2") (pinfunction "K_2") (pintype "passive"))
      (node (ref "D8") (pin "2") (pinfunction "K_2") (pintype "passive"))
      (node (ref "D9") (pin "2") (pinfunction "K_2") (pintype "passive"))
      (node (ref "H1") (pin "4") (pinfunction "4_4") (pintype "passive"))
      (node (ref "H2") (pin "4") (pinfunction "4_4") (pintype "passive"))
      (node (ref "H3") (pin "4") (pinfunction "4_4") (pintype "passive"))
      (node (ref "HD3") (pin "1") (pinfunction "1_1") (pintype "passive"))
      (node (ref "HD32") (pin "1") (pinfunction "1_1") (pintype "passive"))
      (node (ref "IC1") (pin "2") (pinfunction "~{RE}_2") (pintype "passive"))
      (node (ref "IC1") (pin "3") (pinfunction "DE_3") (pintype "passive"))
      (node (ref "IC1") (pin "5") (pinfunction "GND_5") (pintype "passive"))
      (node (ref "IC10") (pin "2") (pinfunction "~{RE}_2") (pintype "passive"))
      (node (ref "IC10") (pin "3") (pinfunction "DE_3") (pintype "passive"))
      (node (ref "IC10") (pin "5") (pinfunction "GND_5") (pintype "passive"))
      (node (ref "IC11") (pin "4") (pinfunction "-V_4") (pintype "passive"))
      (node (ref "IC12") (pin "2") (pinfunction "~{RE}_2") (pintype "passive"))
      (node (ref "IC12") (pin "3") (pinfunction "DE_3") (pintype "passive"))
      (node (ref "IC12") (pin "5") (pinfunction "GND_5") (pintype "passive"))
      (node (ref "IC13") (pin "2") (pinfunction "~{RE}_2") (pintype "passive"))
      (node (ref "IC13") (pin "3") (pinfunction "DE_3") (pintype "passive"))
      (node (ref "IC13") (pin "5") (pinfunction "GND_5") (pintype "passive"))
      (node (ref "IC14") (pin "2") (pinfunction "~{RE}_2") (pintype "passive"))
      (node (ref "IC14") (pin "3") (pinfunction "DE_3") (pintype "passive"))
      (node (ref "IC14") (pin "5") (pinfunction "GND_5") (pintype "passive"))
      (node (ref "IC15") (pin "2") (pinfunction "~{RE}_2") (pintype "passive"))
      (node (ref "IC15") (pin "3") (pinfunction "DE_3") (pintype "passive"))
      (node (ref "IC15") (pin "5") (pinfunction "GND_5") (pintype "passive"))
      (node (ref "IC16") (pin "2") (pinfunction "~{RE}_2") (pintype "passive"))
      (node (ref "IC16") (pin "3") (pinfunction "DE_3") (pintype "passive"))
      (node (ref "IC16") (pin "5") (pinfunction "GND_5") (pintype "passive"))
      (node (ref "IC2") (pin "1") (pinfunction "ADJ/G_1") (pintype "passive"))
      (node (ref "IC3") (pin "2") (pinfunction "~{RE}_2") (pintype "passive"))
      (node (ref "IC3") (pin "3") (pinfunction "DE_3") (pintype "passive"))
      (node (ref "IC3") (pin "5") (pinfunction "GND_5") (pintype "passive"))
      (node (ref "IC4") (pin "2") (pinfunction "~{RE}_2") (pintype "passive"))
      (node (ref "IC4") (pin "3") (pinfunction "DE_3") (pintype "passive"))
      (node (ref "IC4") (pin "5") (pinfunction "GND_5") (pintype "passive"))
      (node (ref "IC5") (pin "2") (pinfunction "~{RE}_2") (pintype "passive"))
      (node (ref "IC5") (pin "3") (pinfunction "DE_3") (pintype "passive"))
      (node (ref "IC5") (pin "5") (pinfunction "GND_5") (pintype "passive"))
      (node (ref "IC6") (pin "2") (pinfunction "~{RE}_2") (pintype "passive"))
      (node (ref "IC6") (pin "3") (pinfunction "DE_3") (pintype "passive"))
      (node (ref "IC6") (pin "5") (pinfunction "GND_5") (pintype "passive"))
      (node (ref "IC7") (pin "1") (pinfunction "A0_1") (pintype "passive"))
      (node (ref "IC7") (pin "2") (pinfunction "A1_2") (pintype "passive"))
      (node (ref "IC7") (pin "3") (pinfunction "A2_3") (pintype "passive"))
      (node (ref "IC7") (pin "4") (pinfunction "GND_4") (pintype "power_in"))
      (node (ref "IC7") (pin "7") (pinfunction "WP_7") (pintype "passive"))
      (node (ref "IC8") (pin "2") (pinfunction "~{RE}_2") (pintype "passive"))
      (node (ref "IC8") (pin "3") (pinfunction "DE_3") (pintype "passive"))
      (node (ref "IC8") (pin "5") (pinfunction "GND_5") (pintype "passive"))
      (node (ref "IC9") (pin "4") (pinfunction "GND_4") (pintype "passive"))
      (node (ref "OP1") (pin "3") (pinfunction "C_3") (pintype "passive"))
      (node (ref "OP10") (pin "3") (pinfunction "C_3") (pintype "passive"))
      (node (ref "OP11") (pin "3") (pinfunction "C_3") (pintype "passive"))
      (node (ref "OP12") (pin "3") (pinfunction "C_3") (pintype "passive"))
      (node (ref "OP14") (pin "3") (pinfunction "C_3") (pintype "passive"))
      (node (ref "OP15") (pin "3") (pinfunction "C_3") (pintype "passive"))
      (node (ref "OP16") (pin "3") (pinfunction "C_3") (pintype "passive"))
      (node (ref "OP17") (pin "3") (pinfunction "C_3") (pintype "passive"))
      (node (ref "OP19") (pin "3") (pinfunction "C_3") (pintype "passive"))
      (node (ref "OP2") (pin "3") (pinfunction "C_3") (pintype "passive"))
      (node (ref "OP20") (pin "3") (pinfunction "C_3") (pintype "passive"))
      (node (ref "OP23") (pin "2") (pinfunction "C_2") (pintype "passive"))
      (node (ref "OP24") (pin "2") (pinfunction "C_2") (pintype "passive"))
      (node (ref "OP25") (pin "2") (pinfunction "C_2") (pintype "passive"))
      (node (ref "OP26") (pin "2") (pinfunction "C_2") (pintype "passive"))
      (node (ref "OP27") (pin "2") (pinfunction "C_2") (pintype "passive"))
      (node (ref "OP28") (pin "2") (pinfunction "C_2") (pintype "passive"))
      (node (ref "OP29") (pin "2") (pinfunction "C_2") (pintype "passive"))
      (node (ref "OP30") (pin "2") (pinfunction "C_2") (pintype "passive"))
      (node (ref "OP31") (pin "2") (pinfunction "C_2") (pintype "passive"))
      (node (ref "OP32") (pin "2") (pinfunction "C_2") (pintype "passive"))
      (node (ref "OP33") (pin "2") (pinfunction "C_2") (pintype "passive"))
      (node (ref "OP34") (pin "2") (pinfunction "C_2") (pintype "passive"))
      (node (ref "OP4") (pin "3") (pinfunction "C_3") (pintype "passive"))
      (node (ref "OP5") (pin "3") (pinfunction "C_3") (pintype "passive"))
      (node (ref "OP6") (pin "3") (pinfunction "C_3") (pintype "passive"))
      (node (ref "OP7") (pin "3") (pinfunction "C_3") (pintype "passive"))
      (node (ref "OP9") (pin "3") (pinfunction "C_3") (pintype "passive"))
      (node (ref "RN1") (pin "1") (pinfunction "1_1") (pintype "passive"))
      (node (ref "RN2") (pin "1") (pinfunction "1_1") (pintype "passive"))
      (node (ref "RN5") (pin "1") (pinfunction "1_1") (pintype "passive"))
      (node (ref "S1") (pin "1") (pinfunction "1_1") (pintype "passive"))
      (node (ref "U1") (pin "1") (pinfunction "1_1") (pintype "passive"))
      (node (ref "U1") (pin "14") (pinfunction "14_14") (pintype "passive"))
      (node (ref "U1") (pin "31") (pinfunction "31_31") (pintype "passive"))
      (node (ref "U1") (pin "45") (pinfunction "45_45") (pintype "passive"))
      (node (ref "U1") (pin "58") (pinfunction "58_58") (pintype "passive"))
      (node (ref "U1") (pin "75") (pinfunction "75_75") (pintype "passive"))
      (node (ref "U10") (pin "10") (pinfunction "GND_10") (pintype "power_in"))
      (node (ref "U10") (pin "19") (pinfunction "OE_19") (pintype "passive"))
      (node (ref "U11") (pin "11") (pinfunction "GND_11") (pintype "passive"))
      (node (ref "U11") (pin "12") (pinfunction "GND_12") (pintype "passive"))
      (node (ref "U11") (pin "13") (pinfunction "GND_13") (pintype "passive"))
      (node (ref "U11") (pin "22") (pinfunction "~{OE}_22") (pintype "passive"))
      (node (ref "U2") (pin "0") (pinfunction "PAD_0") (pintype "passive"))
      (node (ref "U2") (pin "3") (pinfunction "GND_3") (pintype "power_in"))
      (node (ref "U2") (pin "5") (pinfunction "~{ON}/OFF_5") (pintype "input"))
      (node (ref "U3") (pin "10") (pinfunction "GND_10") (pintype "power_in"))
      (node (ref "U3") (pin "19") (pinfunction "OE_19") (pintype "passive"))
      (node (ref "U4") (pin "7") (pinfunction "GND_7") (pintype "passive"))
      (node (ref "U5") (pin "7") (pinfunction "GND_7") (pintype "passive"))
      (node (ref "U6") (pin "10") (pinfunction "GND_10") (pintype "power_in"))
      (node (ref "U6") (pin "19") (pinfunction "OE_19") (pintype "passive"))
      (node (ref "U7") (pin "11") (pinfunction "GND_11") (pintype "passive"))
      (node (ref "U7") (pin "12") (pinfunction "GND_12") (pintype "passive"))
      (node (ref "U7") (pin "13") (pinfunction "GND_13") (pintype "passive"))
      (node (ref "U7") (pin "22") (pinfunction "~{OE}_22") (pintype "passive"))
      (node (ref "U8") (pin "11") (pinfunction "GND_11") (pintype "passive"))
      (node (ref "U8") (pin "12") (pinfunction "GND_12") (pintype "passive"))
      (node (ref "U8") (pin "13") (pinfunction "GND_13") (pintype "passive"))
      (node (ref "U8") (pin "22") (pinfunction "~{OE}_22") (pintype "passive"))
      (node (ref "U9") (pin "11") (pinfunction "GND_11") (pintype "passive"))
      (node (ref "U9") (pin "12") (pinfunction "GND_12") (pintype "passive"))
      (node (ref "U9") (pin "13") (pinfunction "GND_13") (pintype "passive"))
      (node (ref "U9") (pin "22") (pinfunction "~{OE}_22") (pintype "passive"))
      (node (ref "VR1") (pin "3") (pinfunction "3_3") (pintype "passive"))
      (node (ref "VR2") (pin "3") (pinfunction "3_3") (pintype "passive"))
    )
    (net (code "255") (name "G_Drive") (class "Default")
      (node (ref "C1") (pin "1") (pinfunction "1_1") (pintype "passive"))
      (node (ref "C22") (pin "1") (pinfunction "1_1") (pintype "passive"))
      (node (ref "C34") (pin "1") (pinfunction "1_1") (pintype "passive"))
      (node (ref "C50") (pin "1") (pinfunction "1_1") (pintype "passive"))
      (node (ref "C65") (pin "1") (pinfunction "1_1") (pintype "passive"))
      (node (ref "C84") (pin "1") (pinfunction "1_1") (pintype "passive"))
      (node (ref "HD11") (pin "4") (pinfunction "4_4") (pintype "passive"))
      (node (ref "HD18") (pin "4") (pinfunction "4_4") (pintype "passive"))
      (node (ref "HD24") (pin "4") (pinfunction "4_4") (pintype "passive"))
      (node (ref "HD30") (pin "4") (pinfunction "4_4") (pintype "passive"))
      (node (ref "HD34") (pin "4") (pinfunction "4_4") (pintype "passive"))
      (node (ref "HD4") (pin "4") (pinfunction "4_4") (pintype "passive"))
      (node (ref "OP13") (pin "5") (pinfunction "GND_5") (pintype "passive"))
      (node (ref "OP18") (pin "5") (pinfunction "GND_5") (pintype "passive"))
      (node (ref "OP21") (pin "5") (pinfunction "GND_5") (pintype "passive"))
      (node (ref "OP22") (pin "5") (pinfunction "GND_5") (pintype "passive"))
      (node (ref "OP3") (pin "5") (pinfunction "GND_5") (pintype "passive"))
      (node (ref "OP8") (pin "5") (pinfunction "GND_5") (pintype "passive"))
    )
    (net (code "256") (name "G_Relay") (class "Default")
      (node (ref "HD40") (pin "1") (pinfunction "1_1") (pintype "passive"))
      (node (ref "Q1") (pin "1") (pinfunction "E_1") (pintype "passive"))
      (node (ref "Q2") (pin "1") (pinfunction "E_1") (pintype "passive"))
      (node (ref "Q3") (pin "1") (pinfunction "E_1") (pintype "passive"))
      (node (ref "Q4") (pin "1") (pinfunction "E_1") (pintype "passive"))
      (node (ref "Q5") (pin "1") (pinfunction "E_1") (pintype "passive"))
      (node (ref "Q6") (pin "1") (pinfunction "E_1") (pintype "passive"))
    )
    (net (code "257") (name "Net-(D1-Pad1)") (class "Default")
      (node (ref "D1") (pin "1") (pintype "passive"))
      (node (ref "F1") (pin "2") (pinfunction "2_2") (pintype "passive"))
    )
    (net (code "258") (name "Net-(D2-K)") (class "Default")
      (node (ref "D2") (pin "2") (pinfunction "K_2") (pintype "passive"))
      (node (ref "OP1") (pin "1") (pinfunction "A_1") (pintype "passive"))
      (node (ref "R1") (pin "1") (pinfunction "1_1") (pintype "passive"))
    )
    (net (code "259") (name "Net-(D3-K)") (class "Default")
      (node (ref "D3") (pin "2") (pinfunction "K_2") (pintype "passive"))
      (node (ref "OP2") (pin "1") (pinfunction "A_1") (pintype "passive"))
      (node (ref "R2") (pin "1") (pinfunction "1_1") (pintype "passive"))
    )
    (net (code "260") (name "Net-(D4-a)") (class "Default")
      (node (ref "D4") (pin "1") (pinfunction "a_1") (pintype "passive"))
      (node (ref "L1") (pin "1") (pinfunction "1_1") (pintype "passive"))
      (node (ref "U2") (pin "2") (pinfunction "OUT_2") (pintype "power_in"))
    )
    (net (code "261") (name "Net-(D5-K)") (class "Default")
      (node (ref "D5") (pin "2") (pinfunction "K_2") (pintype "passive"))
      (node (ref "OP4") (pin "1") (pinfunction "A_1") (pintype "passive"))
      (node (ref "R9") (pin "1") (pinfunction "1_1") (pintype "passive"))
    )
    (net (code "262") (name "Net-(D6-K)") (class "Default")
      (node (ref "D6") (pin "2") (pinfunction "K_2") (pintype "passive"))
      (node (ref "OP5") (pin "1") (pinfunction "A_1") (pintype "passive"))
      (node (ref "R10") (pin "1") (pinfunction "1_1") (pintype "passive"))
    )
    (net (code "263") (name "Net-(D7-A)") (class "Default")
      (node (ref "D7") (pin "1") (pinfunction "A_1") (pintype "passive"))
      (node (ref "R11") (pin "2") (pinfunction "2_2") (pintype "passive"))
    )
    (net (code "264") (name "Net-(D8-A)") (class "Default")
      (node (ref "D8") (pin "1") (pinfunction "A_1") (pintype "passive"))
      (node (ref "R12") (pin "2") (pinfunction "2_2") (pintype "passive"))
    )
    (net (code "265") (name "Net-(D9-A)") (class "Default")
      (node (ref "D9") (pin "1") (pinfunction "A_1") (pintype "passive"))
      (node (ref "R13") (pin "2") (pinfunction "2_2") (pintype "passive"))
    )
    (net (code "266") (name "Net-(D10-K)") (class "Default")
      (node (ref "D10") (pin "2") (pinfunction "K_2") (pintype "passive"))
      (node (ref "OP6") (pin "1") (pinfunction "A_1") (pintype "passive"))
      (node (ref "R15") (pin "1") (pinfunction "1_1") (pintype "passive"))
    )
    (net (code "267") (name "Net-(D11-K)") (class "Default")
      (node (ref "D11") (pin "2") (pinfunction "K_2") (pintype "passive"))
      (node (ref "OP7") (pin "1") (pinfunction "A_1") (pintype "passive"))
      (node (ref "R16") (pin "1") (pinfunction "1_1") (pintype "passive"))
    )
    (net (code "268") (name "Net-(D12-K)") (class "Default")
      (node (ref "D12") (pin "2") (pinfunction "K_2") (pintype "passive"))
      (node (ref "OP9") (pin "1") (pinfunction "A_1") (pintype "passive"))
      (node (ref "R23") (pin "1") (pinfunction "1_1") (pintype "passive"))
    )
    (net (code "269") (name "Net-(D13-K)") (class "Default")
      (node (ref "D13") (pin "2") (pinfunction "K_2") (pintype "passive"))
      (node (ref "OP10") (pin "1") (pinfunction "A_1") (pintype "passive"))
      (node (ref "R24") (pin "1") (pinfunction "1_1") (pintype "passive"))
    )
    (net (code "270") (name "Net-(D14-K)") (class "Default")
      (node (ref "D14") (pin "2") (pinfunction "K_2") (pintype "passive"))
      (node (ref "OP11") (pin "1") (pinfunction "A_1") (pintype "passive"))
      (node (ref "R27") (pin "1") (pinfunction "1_1") (pintype "passive"))
    )
    (net (code "271") (name "Net-(D15-K)") (class "Default")
      (node (ref "D15") (pin "2") (pinfunction "K_2") (pintype "passive"))
      (node (ref "OP12") (pin "1") (pinfunction "A_1") (pintype "passive"))
      (node (ref "R28") (pin "1") (pinfunction "1_1") (pintype "passive"))
    )
    (net (code "272") (name "Net-(D16-K)") (class "Default")
      (node (ref "D16") (pin "2") (pinfunction "K_2") (pintype "passive"))
      (node (ref "OP14") (pin "1") (pinfunction "A_1") (pintype "passive"))
      (node (ref "R33") (pin "1") (pinfunction "1_1") (pintype "passive"))
    )
    (net (code "273") (name "Net-(D17-K)") (class "Default")
      (node (ref "D17") (pin "2") (pinfunction "K_2") (pintype "passive"))
      (node (ref "OP15") (pin "1") (pinfunction "A_1") (pintype "passive"))
      (node (ref "R35") (pin "1") (pinfunction "1_1") (pintype "passive"))
    )
    (net (code "274") (name "Net-(D18-K)") (class "Default")
      (node (ref "D18") (pin "2") (pinfunction "K_2") (pintype "passive"))
      (node (ref "OP16") (pin "1") (pinfunction "A_1") (pintype "passive"))
      (node (ref "R41") (pin "1") (pinfunction "1_1") (pintype "passive"))
    )
    (net (code "275") (name "Net-(D19-K)") (class "Default")
      (node (ref "D19") (pin "2") (pinfunction "K_2") (pintype "passive"))
      (node (ref "OP17") (pin "1") (pinfunction "A_1") (pintype "passive"))
      (node (ref "R42") (pin "1") (pinfunction "1_1") (pintype "passive"))
    )
    (net (code "276") (name "Net-(D20-K)") (class "Default")
      (node (ref "D20") (pin "2") (pinfunction "K_2") (pintype "passive"))
      (node (ref "OP19") (pin "1") (pinfunction "A_1") (pintype "passive"))
      (node (ref "R47") (pin "1") (pinfunction "1_1") (pintype "passive"))
    )
    (net (code "277") (name "Net-(D21-K)") (class "Default")
      (node (ref "D21") (pin "2") (pinfunction "K_2") (pintype "passive"))
      (node (ref "OP20") (pin "1") (pinfunction "A_1") (pintype "passive"))
      (node (ref "R48") (pin "1") (pinfunction "1_1") (pintype "passive"))
    )
    (net (code "278") (name "Net-(D24-K)") (class "Default")
      (node (ref "D24") (pin "2") (pinfunction "K_2") (pintype "passive"))
      (node (ref "R64") (pin "2") (pinfunction "2_2") (pintype "passive"))
    )
    (net (code "279") (name "Net-(D25-K)") (class "Default")
      (node (ref "D25") (pin "2") (pinfunction "K_2") (pintype "passive"))
      (node (ref "OP24") (pin "4") (pinfunction "E_4") (pintype "passive"))
      (node (ref "R67") (pin "1") (pinfunction "1_1") (pintype "passive"))
    )
    (net (code "280") (name "Net-(D26-K)") (class "Default")
      (node (ref "D26") (pin "2") (pinfunction "K_2") (pintype "passive"))
      (node (ref "R70") (pin "2") (pinfunction "2_2") (pintype "passive"))
    )
    (net (code "281") (name "Net-(D27-K)") (class "Default")
      (node (ref "D27") (pin "2") (pinfunction "K_2") (pintype "passive"))
      (node (ref "OP26") (pin "4") (pinfunction "E_4") (pintype "passive"))
      (node (ref "R72") (pin "1") (pinfunction "1_1") (pintype "passive"))
    )
    (net (code "282") (name "Net-(D28-K)") (class "Default")
      (node (ref "D28") (pin "2") (pinfunction "K_2") (pintype "passive"))
      (node (ref "R75") (pin "2") (pinfunction "2_2") (pintype "passive"))
    )
    (net (code "283") (name "Net-(D29-K)") (class "Default")
      (node (ref "D29") (pin "2") (pinfunction "K_2") (pintype "passive"))
      (node (ref "OP28") (pin "4") (pinfunction "E_4") (pintype "passive"))
      (node (ref "R77") (pin "1") (pinfunction "1_1") (pintype "passive"))
    )
    (net (code "284") (name "Net-(D30-K)") (class "Default")
      (node (ref "D30") (pin "2") (pinfunction "K_2") (pintype "passive"))
      (node (ref "R83") (pin "2") (pinfunction "2_2") (pintype "passive"))
    )
    (net (code "285") (name "Net-(D31-K)") (class "Default")
      (node (ref "D31") (pin "2") (pinfunction "K_2") (pintype "passive"))
      (node (ref "OP29") (pin "4") (pinfunction "E_4") (pintype "passive"))
      (node (ref "R82") (pin "1") (pinfunction "1_1") (pintype "passive"))
    )
    (net (code "286") (name "Net-(D32-K)") (class "Default")
      (node (ref "D32") (pin "2") (pinfunction "K_2") (pintype "passive"))
      (node (ref "R88") (pin "2") (pinfunction "2_2") (pintype "passive"))
    )
    (net (code "287") (name "Net-(D33-K)") (class "Default")
      (node (ref "D33") (pin "2") (pinfunction "K_2") (pintype "passive"))
      (node (ref "OP31") (pin "4") (pinfunction "E_4") (pintype "passive"))
      (node (ref "R87") (pin "1") (pinfunction "1_1") (pintype "passive"))
    )
    (net (code "288") (name "Net-(D34-K)") (class "Default")
      (node (ref "D34") (pin "2") (pinfunction "K_2") (pintype "passive"))
      (node (ref "R93") (pin "2") (pinfunction "2_2") (pintype "passive"))
    )
    (net (code "289") (name "Net-(D35-K)") (class "Default")
      (node (ref "D35") (pin "2") (pinfunction "K_2") (pintype "passive"))
      (node (ref "OP33") (pin "4") (pinfunction "E_4") (pintype "passive"))
      (node (ref "R92") (pin "1") (pinfunction "1_1") (pintype "passive"))
    )
    (net (code "290") (name "Net-(F1-Pad1)") (class "Default")
      (node (ref "F1") (pin "1") (pinfunction "1_1") (pintype "passive"))
      (node (ref "HD3") (pin "2") (pinfunction "2_2") (pintype "passive"))
    )
    (net (code "291") (name "Net-(IC11A-IN+)") (class "Default")
      (node (ref "C71") (pin "2") (pinfunction "2_2") (pintype "passive"))
      (node (ref "IC11") (pin "3") (pinfunction "IN+_3") (pintype "input"))
      (node (ref "VR1") (pin "2") (pinfunction "2_2") (pintype "passive"))
    )
    (net (code "292") (name "Net-(IC11B-IN+)") (class "Default")
      (node (ref "C81") (pin "2") (pinfunction "2_2") (pintype "passive"))
      (node (ref "IC11") (pin "5") (pinfunction "IN+_5") (pintype "input"))
      (node (ref "VR2") (pin "2") (pinfunction "2_2") (pintype "passive"))
    )
    (net (code "293") (name "Net-(OP3-C1)") (class "Default")
      (node (ref "OP3") (pin "2") (pinfunction "C1_2") (pintype "passive"))
      (node (ref "R5") (pin "2") (pinfunction "2_2") (pintype "passive"))
    )
    (net (code "294") (name "Net-(OP3-C2)") (class "Default")
      (node (ref "OP3") (pin "3") (pinfunction "C2_3") (pintype "passive"))
      (node (ref "R6") (pin "2") (pinfunction "2_2") (pintype "passive"))
    )
    (net (code "295") (name "Net-(OP8-C1)") (class "Default")
      (node (ref "OP8") (pin "2") (pinfunction "C1_2") (pintype "passive"))
      (node (ref "R19") (pin "2") (pinfunction "2_2") (pintype "passive"))
    )
    (net (code "296") (name "Net-(OP8-C2)") (class "Default")
      (node (ref "OP8") (pin "3") (pinfunction "C2_3") (pintype "passive"))
      (node (ref "R21") (pin "2") (pinfunction "2_2") (pintype "passive"))
    )
    (net (code "297") (name "Net-(OP13-C1)") (class "Default")
      (node (ref "OP13") (pin "2") (pinfunction "C1_2") (pintype "passive"))
      (node (ref "R32") (pin "2") (pinfunction "2_2") (pintype "passive"))
    )
    (net (code "298") (name "Net-(OP13-C2)") (class "Default")
      (node (ref "OP13") (pin "3") (pinfunction "C2_3") (pintype "passive"))
      (node (ref "R34") (pin "2") (pinfunction "2_2") (pintype "passive"))
    )
    (net (code "299") (name "Net-(OP18-C1)") (class "Default")
      (node (ref "OP18") (pin "2") (pinfunction "C1_2") (pintype "passive"))
      (node (ref "R45") (pin "2") (pinfunction "2_2") (pintype "passive"))
    )
    (net (code "300") (name "Net-(OP18-C2)") (class "Default")
      (node (ref "OP18") (pin "3") (pinfunction "C2_3") (pintype "passive"))
      (node (ref "R46") (pin "2") (pinfunction "2_2") (pintype "passive"))
    )
    (net (code "301") (name "Net-(OP21-C1)") (class "Default")
      (node (ref "OP21") (pin "2") (pinfunction "C1_2") (pintype "passive"))
      (node (ref "R54") (pin "2") (pinfunction "2_2") (pintype "passive"))
    )
    (net (code "302") (name "Net-(OP21-C2)") (class "Default")
      (node (ref "OP21") (pin "3") (pinfunction "C2_3") (pintype "passive"))
      (node (ref "R56") (pin "2") (pinfunction "2_2") (pintype "passive"))
    )
    (net (code "303") (name "Net-(OP22-C1)") (class "Default")
      (node (ref "OP22") (pin "2") (pinfunction "C1_2") (pintype "passive"))
      (node (ref "R61") (pin "2") (pinfunction "2_2") (pintype "passive"))
    )
    (net (code "304") (name "Net-(OP22-C2)") (class "Default")
      (node (ref "OP22") (pin "3") (pinfunction "C2_3") (pintype "passive"))
      (node (ref "R63") (pin "2") (pinfunction "2_2") (pintype "passive"))
    )
    (net (code "305") (name "Net-(OP23-A)") (class "Default")
      (node (ref "OP23") (pin "1") (pinfunction "A_1") (pintype "passive"))
      (node (ref "R64") (pin "1") (pinfunction "1_1") (pintype "passive"))
    )
    (net (code "306") (name "Net-(OP23-C-Pad3)") (class "Default")
      (node (ref "OP23") (pin "3") (pinfunction "C_3") (pintype "passive"))
      (node (ref "R68") (pin "1") (pinfunction "1_1") (pintype "passive"))
    )
    (net (code "307") (name "Net-(OP24-A)") (class "Default")
      (node (ref "OP24") (pin "1") (pinfunction "A_1") (pintype "passive"))
      (node (ref "R66") (pin "1") (pinfunction "1_1") (pintype "passive"))
    )
    (net (code "308") (name "Net-(OP25-A)") (class "Default")
      (node (ref "OP25") (pin "1") (pinfunction "A_1") (pintype "passive"))
      (node (ref "R70") (pin "1") (pinfunction "1_1") (pintype "passive"))
    )
    (net (code "309") (name "Net-(OP25-C-Pad3)") (class "Default")
      (node (ref "OP25") (pin "3") (pinfunction "C_3") (pintype "passive"))
      (node (ref "R74") (pin "1") (pinfunction "1_1") (pintype "passive"))
    )
    (net (code "310") (name "Net-(OP26-A)") (class "Default")
      (node (ref "OP26") (pin "1") (pinfunction "A_1") (pintype "passive"))
      (node (ref "R71") (pin "1") (pinfunction "1_1") (pintype "passive"))
    )
    (net (code "311") (name "Net-(OP27-A)") (class "Default")
      (node (ref "OP27") (pin "1") (pinfunction "A_1") (pintype "passive"))
      (node (ref "R75") (pin "1") (pinfunction "1_1") (pintype "passive"))
    )
    (net (code "312") (name "Net-(OP27-C-Pad3)") (class "Default")
      (node (ref "OP27") (pin "3") (pinfunction "C_3") (pintype "passive"))
      (node (ref "R79") (pin "1") (pinfunction "1_1") (pintype "passive"))
    )
    (net (code "313") (name "Net-(OP28-A)") (class "Default")
      (node (ref "OP28") (pin "1") (pinfunction "A_1") (pintype "passive"))
      (node (ref "R76") (pin "1") (pinfunction "1_1") (pintype "passive"))
    )
    (net (code "314") (name "Net-(OP29-A)") (class "Default")
      (node (ref "OP29") (pin "1") (pinfunction "A_1") (pintype "passive"))
      (node (ref "R81") (pin "1") (pinfunction "1_1") (pintype "passive"))
    )
    (net (code "315") (name "Net-(OP30-A)") (class "Default")
      (node (ref "OP30") (pin "1") (pinfunction "A_1") (pintype "passive"))
      (node (ref "R83") (pin "1") (pinfunction "1_1") (pintype "passive"))
    )
    (net (code "316") (name "Net-(OP30-C-Pad3)") (class "Default")
      (node (ref "OP30") (pin "3") (pinfunction "C_3") (pintype "passive"))
      (node (ref "R84") (pin "1") (pinfunction "1_1") (pintype "passive"))
    )
    (net (code "317") (name "Net-(OP31-A)") (class "Default")
      (node (ref "OP31") (pin "1") (pinfunction "A_1") (pintype "passive"))
      (node (ref "R86") (pin "1") (pinfunction "1_1") (pintype "passive"))
    )
    (net (code "318") (name "Net-(OP32-A)") (class "Default")
      (node (ref "OP32") (pin "1") (pinfunction "A_1") (pintype "passive"))
      (node (ref "R88") (pin "1") (pinfunction "1_1") (pintype "passive"))
    )
    (net (code "319") (name "Net-(OP32-C-Pad3)") (class "Default")
      (node (ref "OP32") (pin "3") (pinfunction "C_3") (pintype "passive"))
      (node (ref "R89") (pin "1") (pinfunction "1_1") (pintype "passive"))
    )
    (net (code "320") (name "Net-(OP33-A)") (class "Default")
      (node (ref "OP33") (pin "1") (pinfunction "A_1") (pintype "passive"))
      (node (ref "R91") (pin "1") (pinfunction "1_1") (pintype "passive"))
    )
    (net (code "321") (name "Net-(OP34-A)") (class "Default")
      (node (ref "OP34") (pin "1") (pinfunction "A_1") (pintype "passive"))
      (node (ref "R93") (pin "1") (pinfunction "1_1") (pintype "passive"))
    )
    (net (code "322") (name "Net-(OP34-C-Pad3)") (class "Default")
      (node (ref "OP34") (pin "3") (pinfunction "C_3") (pintype "passive"))
      (node (ref "R94") (pin "1") (pinfunction "1_1") (pintype "passive"))
    )
    (net (code "323") (name "Net-(Q1-E-Pad3)") (class "Default")
      (node (ref "Q1") (pin "3") (pinfunction "E_3") (pintype "passive"))
      (node (ref "R68") (pin "2") (pinfunction "2_2") (pintype "passive"))
    )
    (net (code "324") (name "Net-(Q2-E-Pad3)") (class "Default")
      (node (ref "Q2") (pin "3") (pinfunction "E_3") (pintype "passive"))
      (node (ref "R74") (pin "2") (pinfunction "2_2") (pintype "passive"))
    )
    (net (code "325") (name "Net-(Q3-E-Pad3)") (class "Default")
      (node (ref "Q3") (pin "3") (pinfunction "E_3") (pintype "passive"))
      (node (ref "R79") (pin "2") (pinfunction "2_2") (pintype "passive"))
    )
    (net (code "326") (name "Net-(Q4-E-Pad3)") (class "Default")
      (node (ref "Q4") (pin "3") (pinfunction "E_3") (pintype "passive"))
      (node (ref "R84") (pin "2") (pinfunction "2_2") (pintype "passive"))
    )
    (net (code "327") (name "Net-(Q5-E-Pad3)") (class "Default")
      (node (ref "Q5") (pin "3") (pinfunction "E_3") (pintype "passive"))
      (node (ref "R89") (pin "2") (pinfunction "2_2") (pintype "passive"))
    )
    (net (code "328") (name "Net-(Q6-E-Pad3)") (class "Default")
      (node (ref "Q6") (pin "3") (pinfunction "E_3") (pintype "passive"))
      (node (ref "R94") (pin "2") (pinfunction "2_2") (pintype "passive"))
    )
    (net (code "329") (name "VDrive") (class "Default")
      (node (ref "C1") (pin "2") (pinfunction "2_2") (pintype "passive"))
      (node (ref "C22") (pin "2") (pinfunction "2_2") (pintype "passive"))
      (node (ref "C34") (pin "2") (pinfunction "2_2") (pintype "passive"))
      (node (ref "C50") (pin "2") (pinfunction "2_2") (pintype "passive"))
      (node (ref "C65") (pin "2") (pinfunction "2_2") (pintype "passive"))
      (node (ref "C84") (pin "2") (pinfunction "2_2") (pintype "passive"))
      (node (ref "HD11") (pin "1") (pinfunction "1_1") (pintype "passive"))
      (node (ref "HD18") (pin "1") (pinfunction "1_1") (pintype "passive"))
      (node (ref "HD24") (pin "1") (pinfunction "1_1") (pintype "passive"))
      (node (ref "HD30") (pin "1") (pinfunction "1_1") (pintype "passive"))
      (node (ref "HD34") (pin "1") (pinfunction "1_1") (pintype "passive"))
      (node (ref "HD4") (pin "1") (pinfunction "1_1") (pintype "passive"))
      (node (ref "OP13") (pin "8") (pinfunction "VCC_8") (pintype "passive"))
      (node (ref "OP18") (pin "8") (pinfunction "VCC_8") (pintype "passive"))
      (node (ref "OP21") (pin "8") (pinfunction "VCC_8") (pintype "passive"))
      (node (ref "OP22") (pin "8") (pinfunction "VCC_8") (pintype "passive"))
      (node (ref "OP3") (pin "8") (pinfunction "VCC_8") (pintype "passive"))
      (node (ref "OP8") (pin "8") (pinfunction "VCC_8") (pintype "passive"))
      (node (ref "R18") (pin "1") (pinfunction "1_1") (pintype "passive"))
      (node (ref "R22") (pin "1") (pinfunction "1_1") (pintype "passive"))
      (node (ref "R30") (pin "1") (pinfunction "1_1") (pintype "passive"))
      (node (ref "R36") (pin "1") (pinfunction "1_1") (pintype "passive"))
      (node (ref "R4") (pin "1") (pinfunction "1_1") (pintype "passive"))
      (node (ref "R44") (pin "1") (pinfunction "1_1") (pintype "passive"))
      (node (ref "R49") (pin "1") (pinfunction "1_1") (pintype "passive"))
      (node (ref "R53") (pin "1") (pinfunction "1_1") (pintype "passive"))
      (node (ref "R57") (pin "1") (pinfunction "1_1") (pintype "passive"))
      (node (ref "R60") (pin "1") (pinfunction "1_1") (pintype "passive"))
      (node (ref "R65") (pin "1") (pinfunction "1_1") (pintype "passive"))
      (node (ref "R7") (pin "1") (pinfunction "1_1") (pintype "passive"))
    )
    (net (code "330") (name "VRelay") (class "Default")
      (node (ref "HD40") (pin "8") (pinfunction "8_8") (pintype "passive"))
      (node (ref "OP23") (pin "4") (pinfunction "E_4") (pintype "passive"))
      (node (ref "OP25") (pin "4") (pinfunction "E_4") (pintype "passive"))
      (node (ref "OP27") (pin "4") (pinfunction "E_4") (pintype "passive"))
      (node (ref "OP30") (pin "4") (pinfunction "E_4") (pintype "passive"))
      (node (ref "OP32") (pin "4") (pinfunction "E_4") (pintype "passive"))
      (node (ref "OP34") (pin "4") (pinfunction "E_4") (pintype "passive"))
    )
    (net (code "331") (name "unconnected-(IC1-DI-Pad4)") (class "Default")
      (node (ref "IC1") (pin "4") (pinfunction "DI_4") (pintype "passive+no_connect"))
    )
    (net (code "332") (name "unconnected-(IC3-DI-Pad4)") (class "Default")
      (node (ref "IC3") (pin "4") (pinfunction "DI_4") (pintype "passive+no_connect"))
    )
    (net (code "333") (name "unconnected-(IC4-DI-Pad4)") (class "Default")
      (node (ref "IC4") (pin "4") (pinfunction "DI_4") (pintype "passive+no_connect"))
    )
    (net (code "334") (name "unconnected-(IC5-DI-Pad4)") (class "Default")
      (node (ref "IC5") (pin "4") (pinfunction "DI_4") (pintype "passive+no_connect"))
    )
    (net (code "335") (name "unconnected-(IC6-DI-Pad4)") (class "Default")
      (node (ref "IC6") (pin "4") (pinfunction "DI_4") (pintype "passive+no_connect"))
    )
    (net (code "336") (name "unconnected-(IC8-DI-Pad4)") (class "Default")
      (node (ref "IC8") (pin "4") (pinfunction "DI_4") (pintype "passive+no_connect"))
    )
    (net (code "337") (name "unconnected-(IC10-DI-Pad4)") (class "Default")
      (node (ref "IC10") (pin "4") (pinfunction "DI_4") (pintype "passive+no_connect"))
    )
    (net (code "338") (name "unconnected-(IC12-DI-Pad4)") (class "Default")
      (node (ref "IC12") (pin "4") (pinfunction "DI_4") (pintype "passive+no_connect"))
    )
    (net (code "339") (name "unconnected-(IC13-DI-Pad4)") (class "Default")
      (node (ref "IC13") (pin "4") (pinfunction "DI_4") (pintype "passive+no_connect"))
    )
    (net (code "340") (name "unconnected-(IC14-DI-Pad4)") (class "Default")
      (node (ref "IC14") (pin "4") (pinfunction "DI_4") (pintype "passive+no_connect"))
    )
    (net (code "341") (name "unconnected-(IC15-DI-Pad4)") (class "Default")
      (node (ref "IC15") (pin "4") (pinfunction "DI_4") (pintype "passive+no_connect"))
    )
    (net (code "342") (name "unconnected-(IC16-DI-Pad4)") (class "Default")
      (node (ref "IC16") (pin "4") (pinfunction "DI_4") (pintype "passive+no_connect"))
    )
    (net (code "343") (name "unconnected-(U1-Pad12)") (class "Default")
      (node (ref "U1") (pin "12") (pinfunction "12_12") (pintype "passive"))
    )
    (net (code "344") (name "unconnected-(U1-Pad52)") (class "Default")
      (node (ref "U1") (pin "52") (pinfunction "52_52") (pintype "passive+no_connect"))
    )
    (net (code "345") (name "unconnected-(U7-A2-Pad5)") (class "Default")
      (node (ref "U7") (pin "5") (pinfunction "A2_5") (pintype "passive"))
    )
    (net (code "346") (name "unconnected-(U7-A5-Pad8)") (class "Default")
      (node (ref "U7") (pin "8") (pinfunction "A5_8") (pintype "passive"))
    )
    (net (code "347") (name "unconnected-(U7-B2-Pad19)") (class "Default")
      (node (ref "U7") (pin "19") (pinfunction "B2_19") (pintype "passive"))
    )
    (net (code "348") (name "unconnected-(U7-B5-Pad16)") (class "Default")
      (node (ref "U7") (pin "16") (pinfunction "B5_16") (pintype "passive"))
    )
    (net (code "349") (name "unconnected-(U11-A2-Pad5)") (class "Default")
      (node (ref "U11") (pin "5") (pinfunction "A2_5") (pintype "passive"))
    )
    (net (code "350") (name "unconnected-(U11-A5-Pad8)") (class "Default")
      (node (ref "U11") (pin "8") (pinfunction "A5_8") (pintype "passive"))
    )
    (net (code "351") (name "unconnected-(U11-B2-Pad19)") (class "Default")
      (node (ref "U11") (pin "19") (pinfunction "B2_19") (pintype "passive"))
    )
    (net (code "352") (name "unconnected-(U11-B5-Pad16)") (class "Default")
      (node (ref "U11") (pin "16") (pinfunction "B5_16") (pintype "passive"))
    )
  )
)
